# EEZ_DIB_MIO168_r1B2.net
KiCad netlist of a schematic drawn in EAGLE
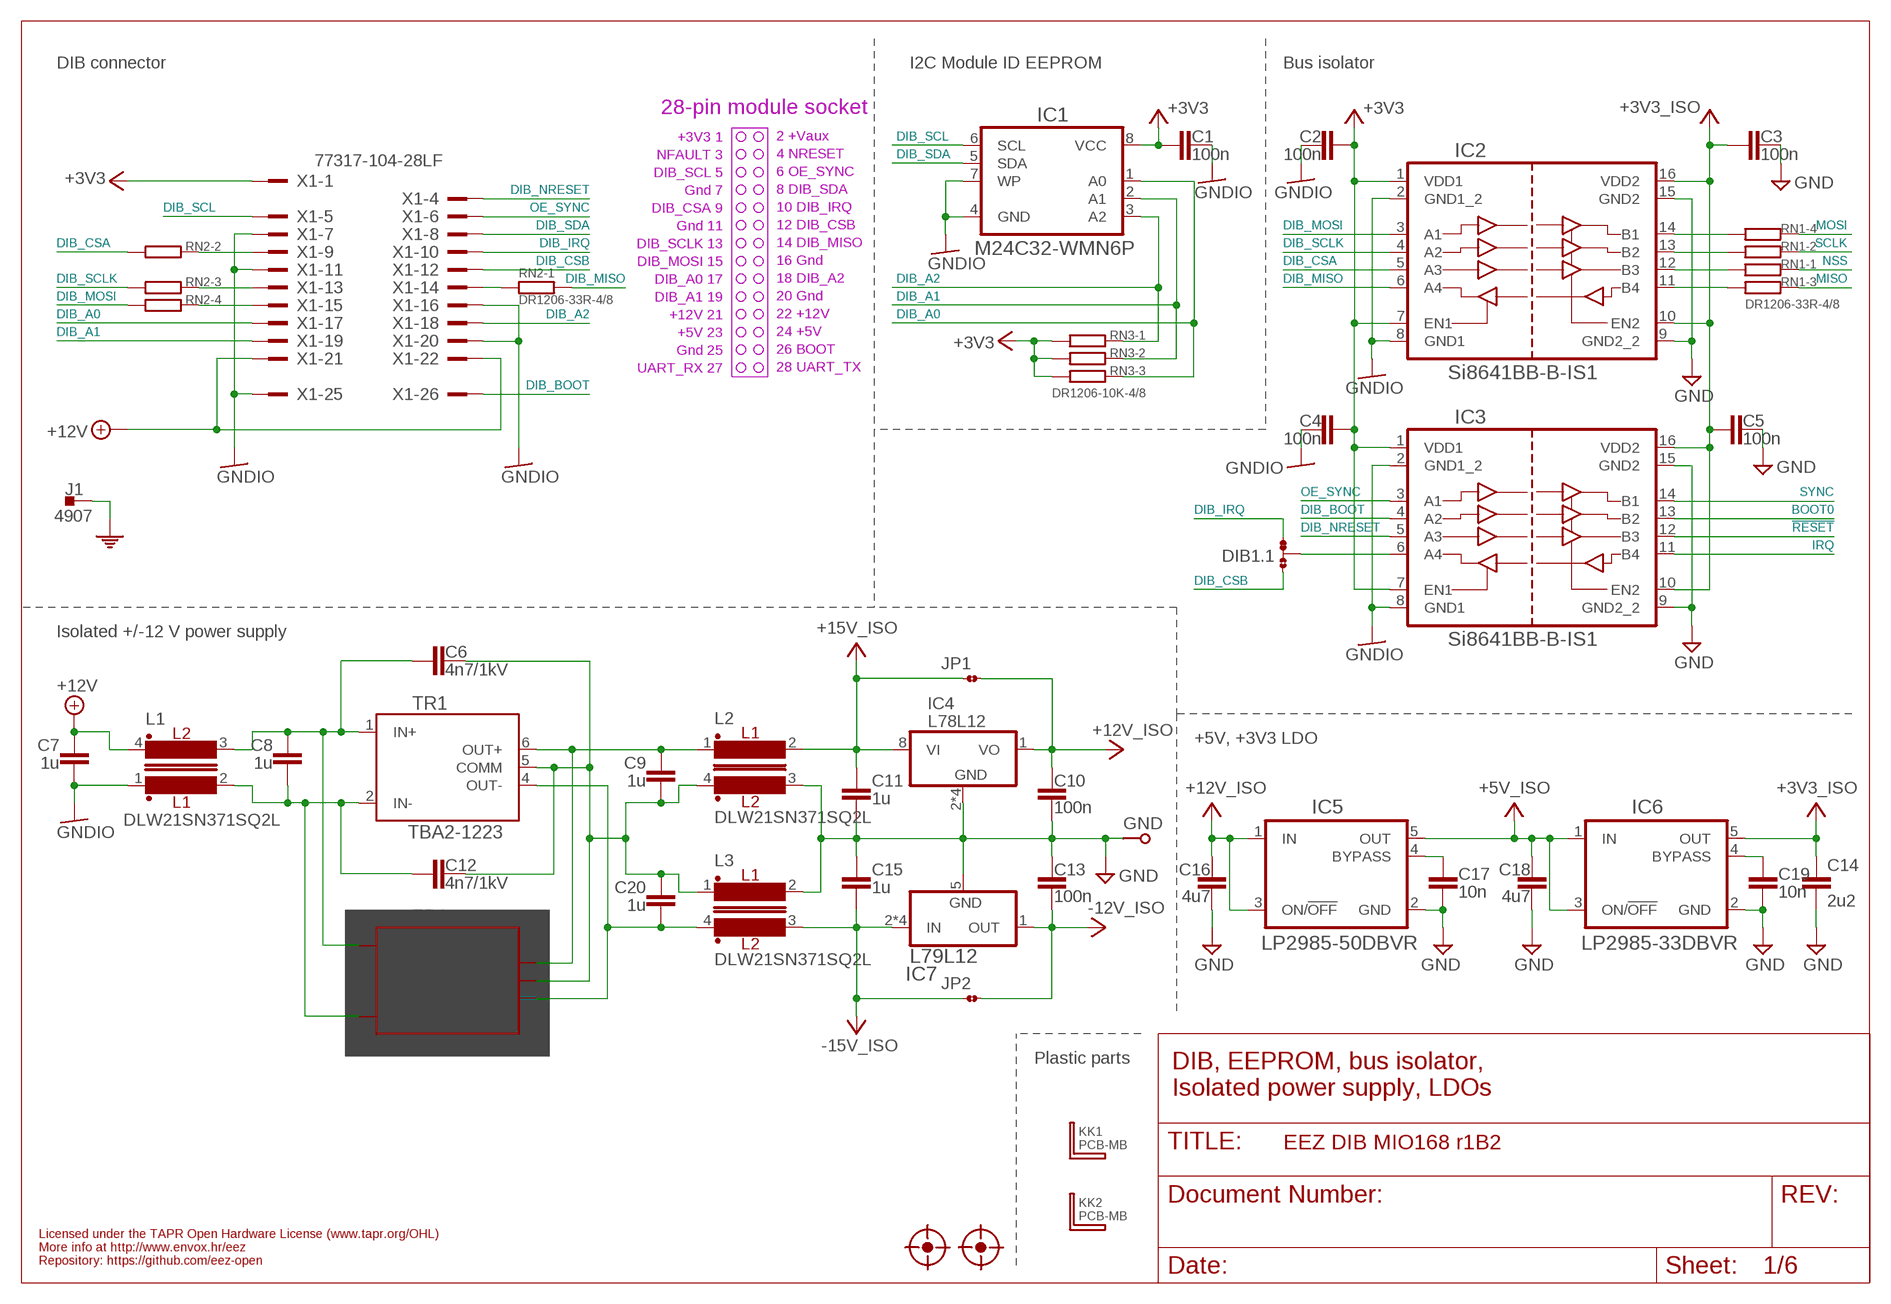
[diagram p0: schematic, sheet 1]
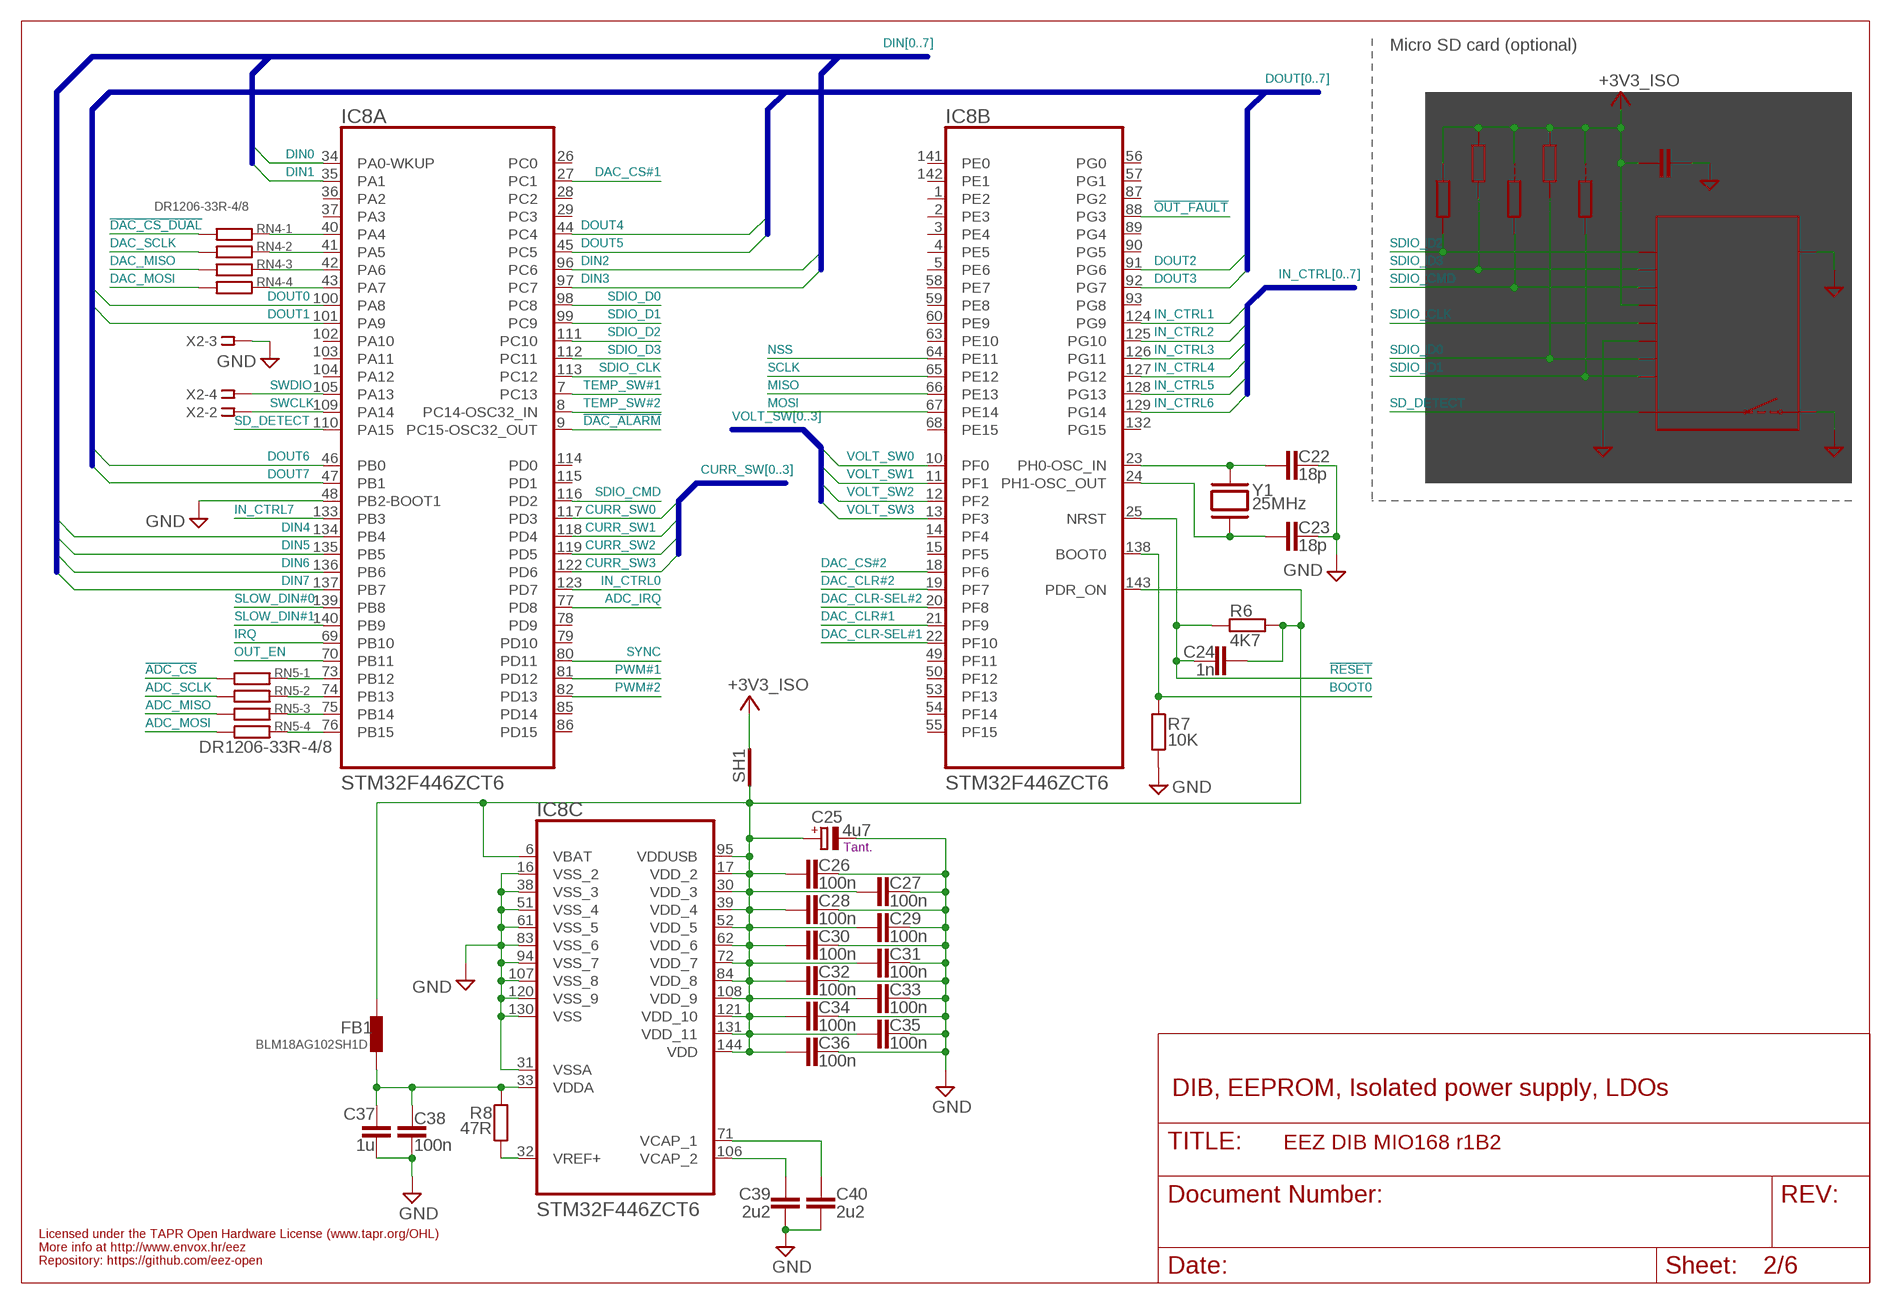
[diagram p1: schematic, sheet 2]
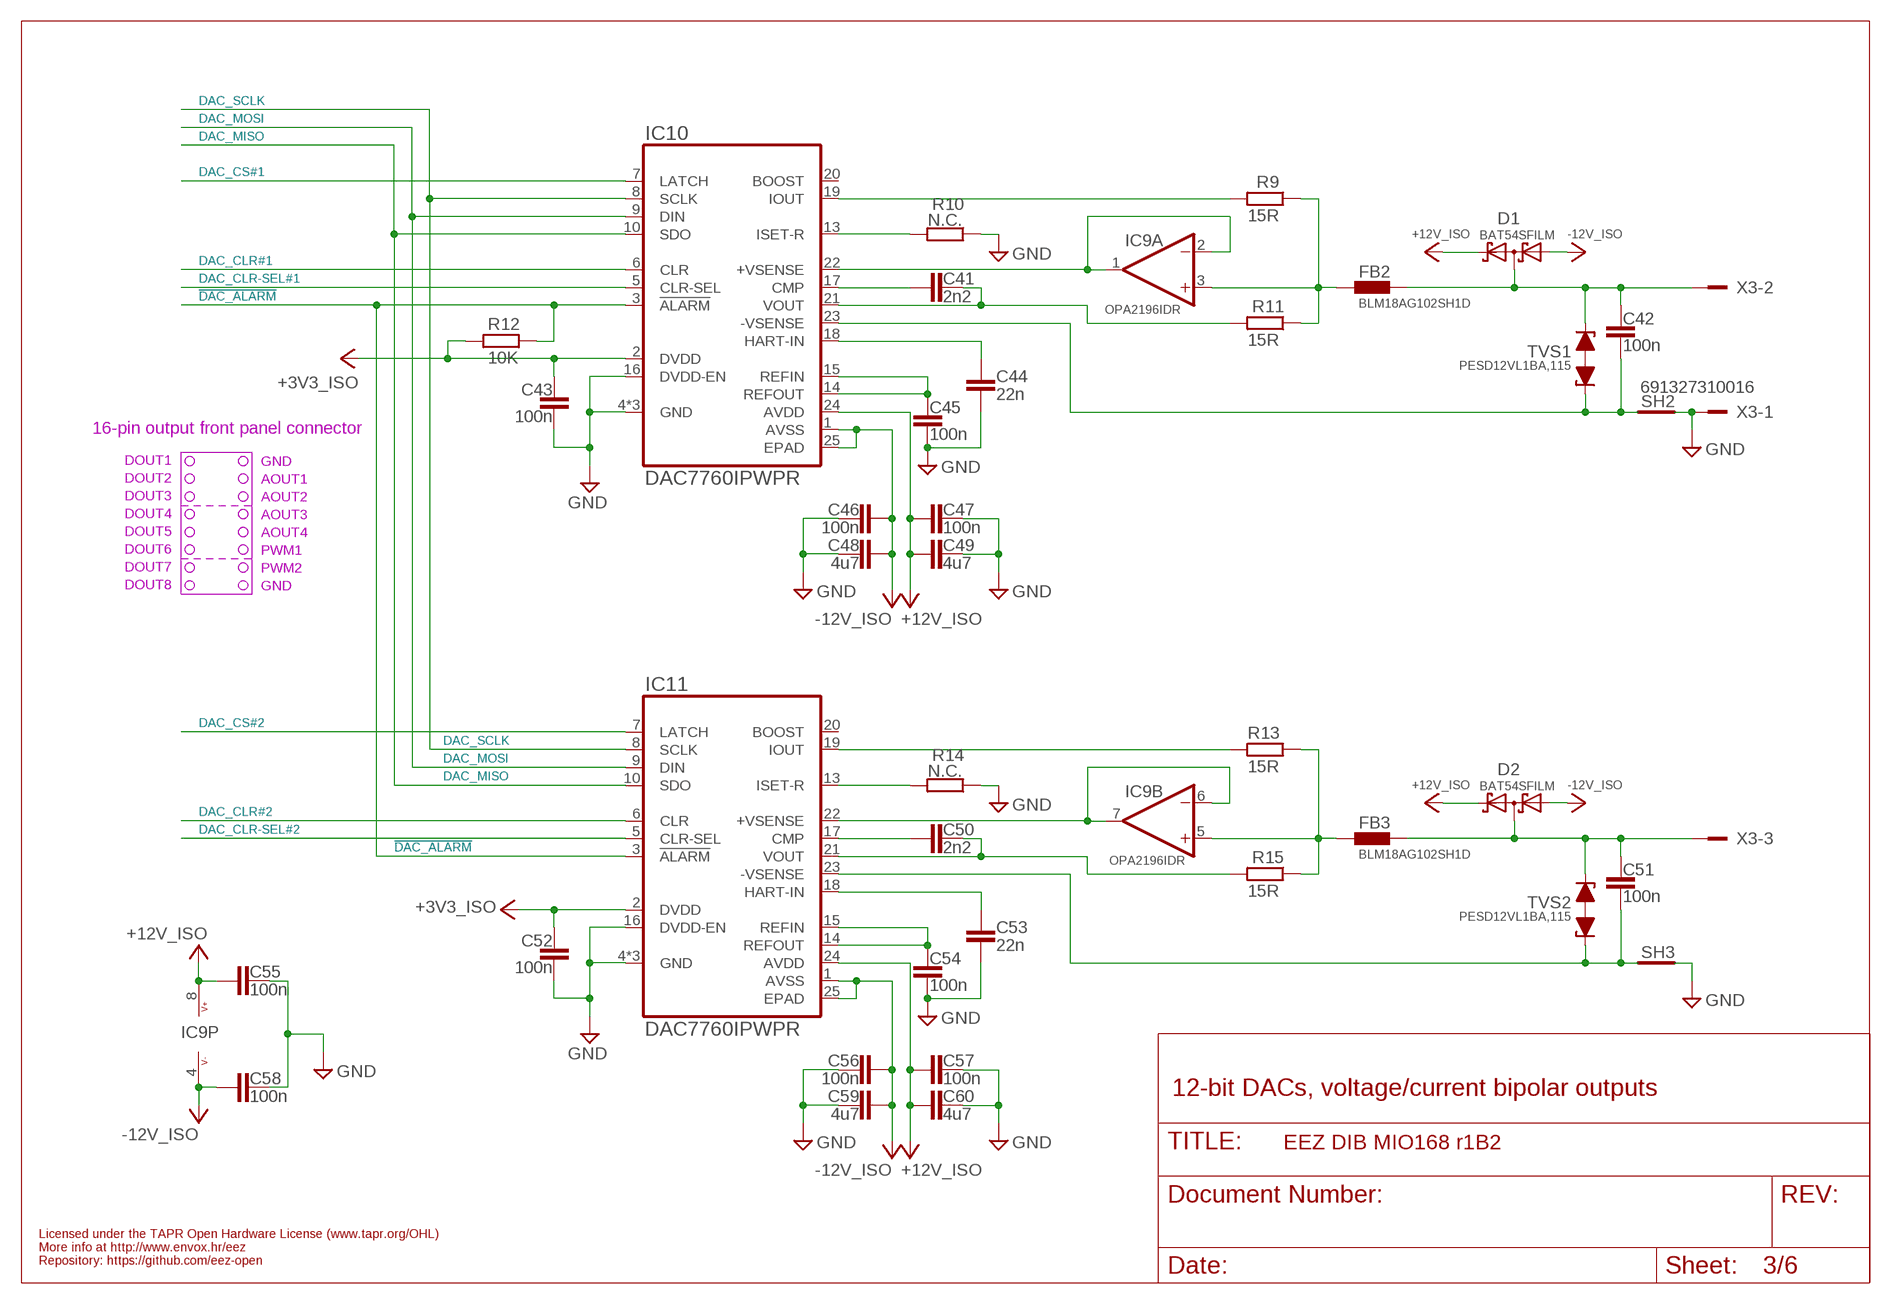
[diagram p2: schematic, sheet 3]
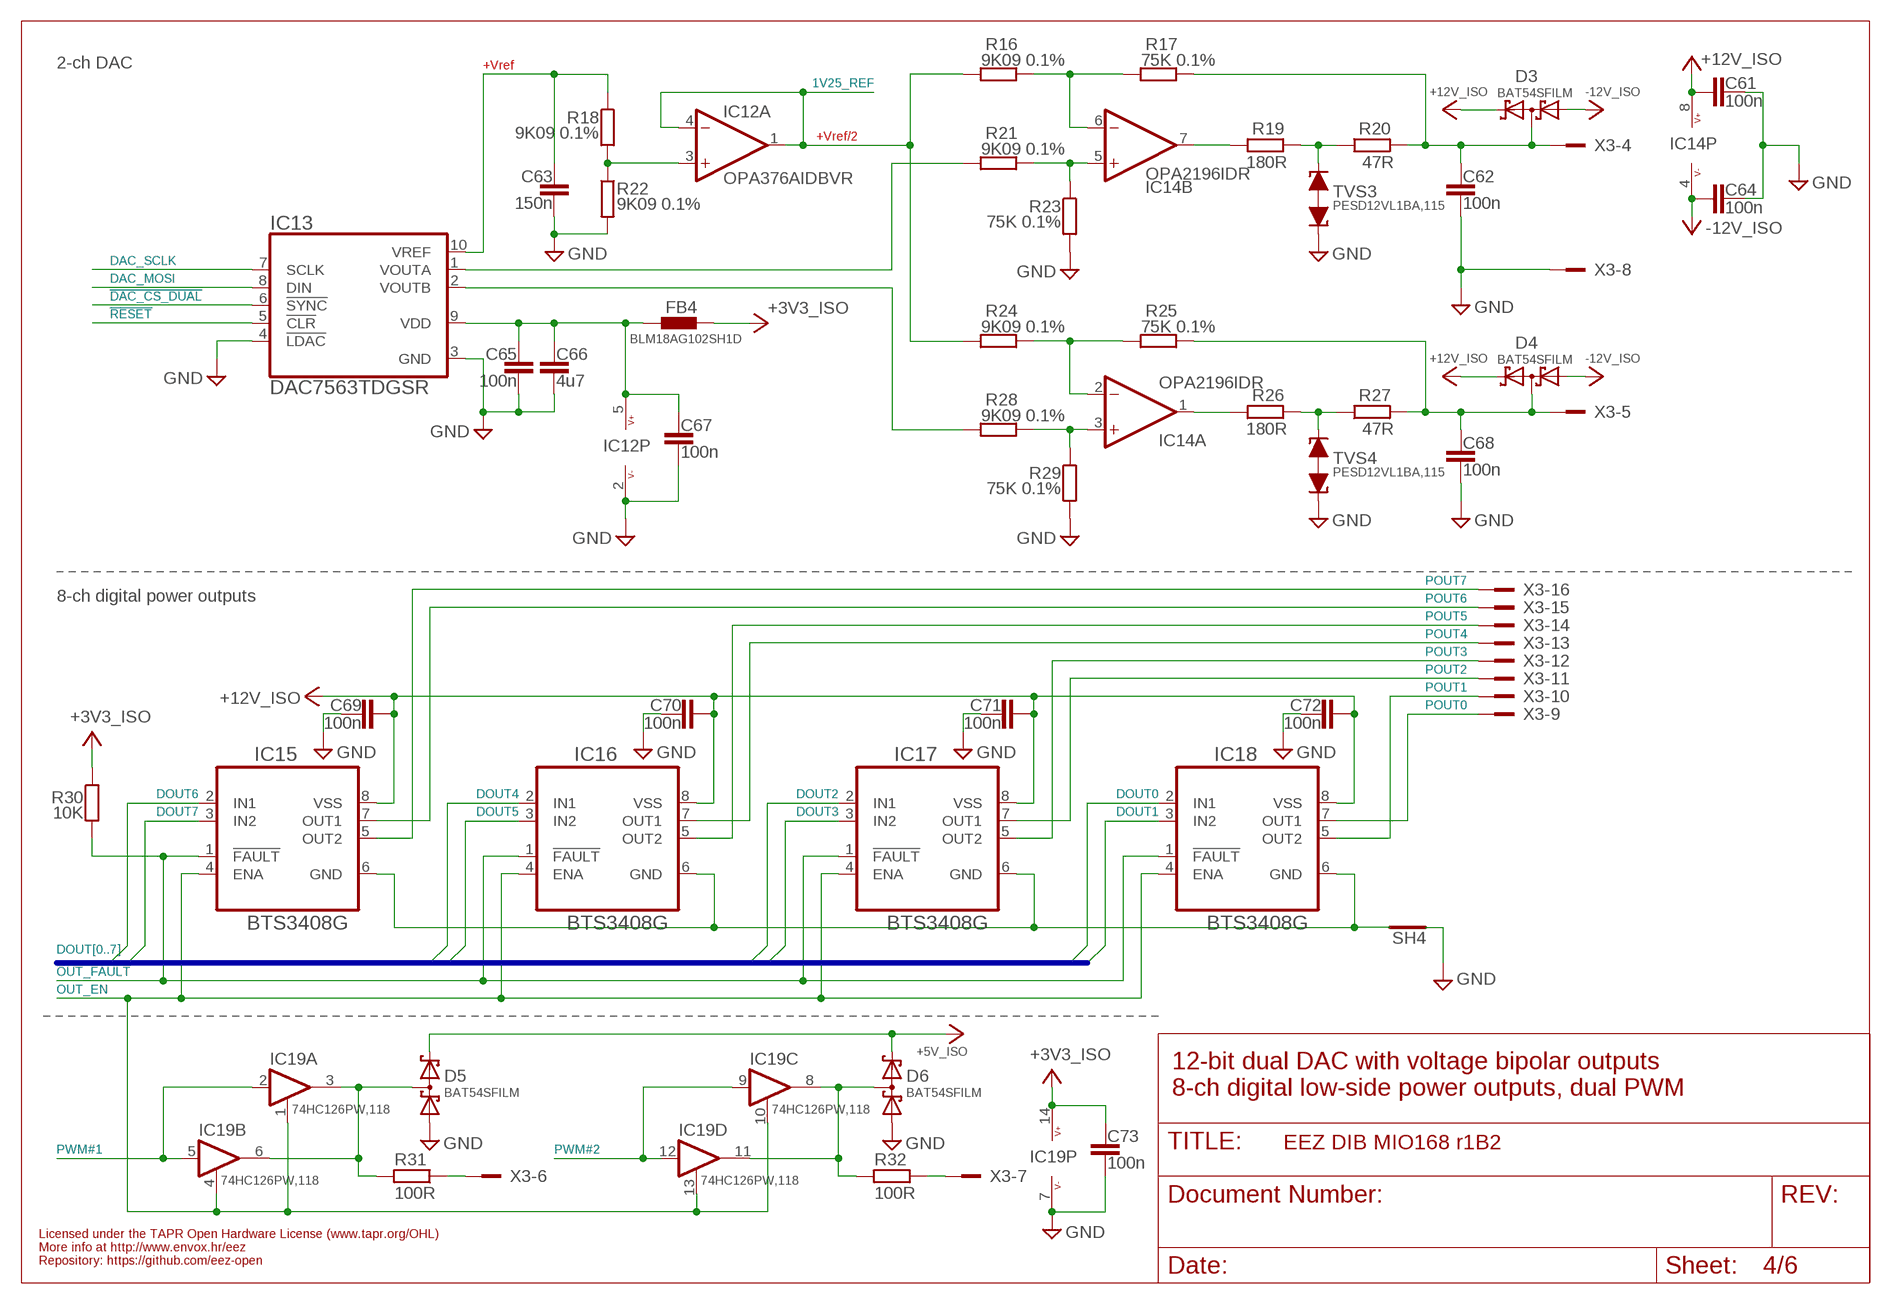
[diagram p3: schematic, sheet 4]
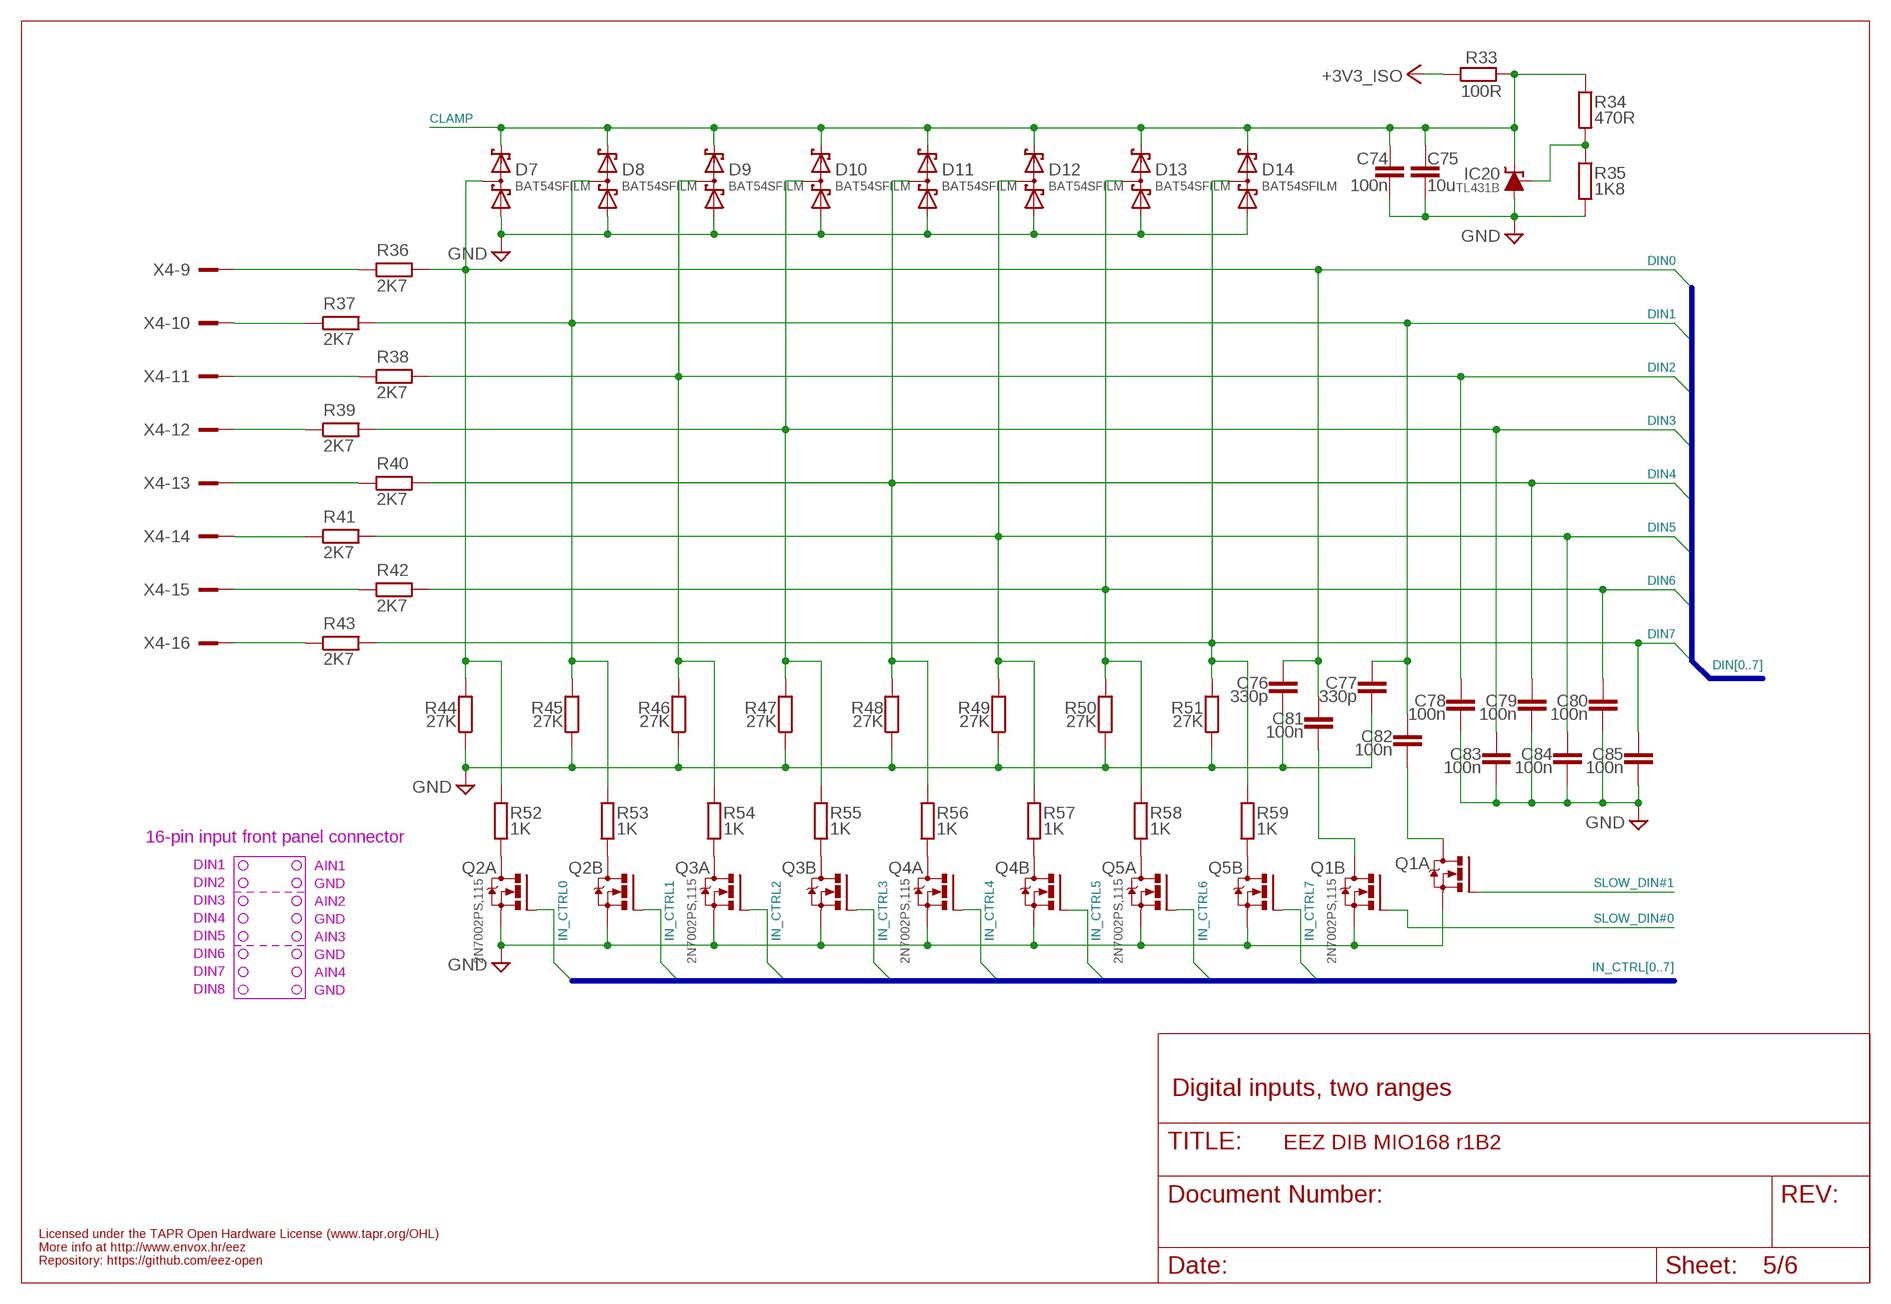
[diagram p4: schematic, sheet 5]
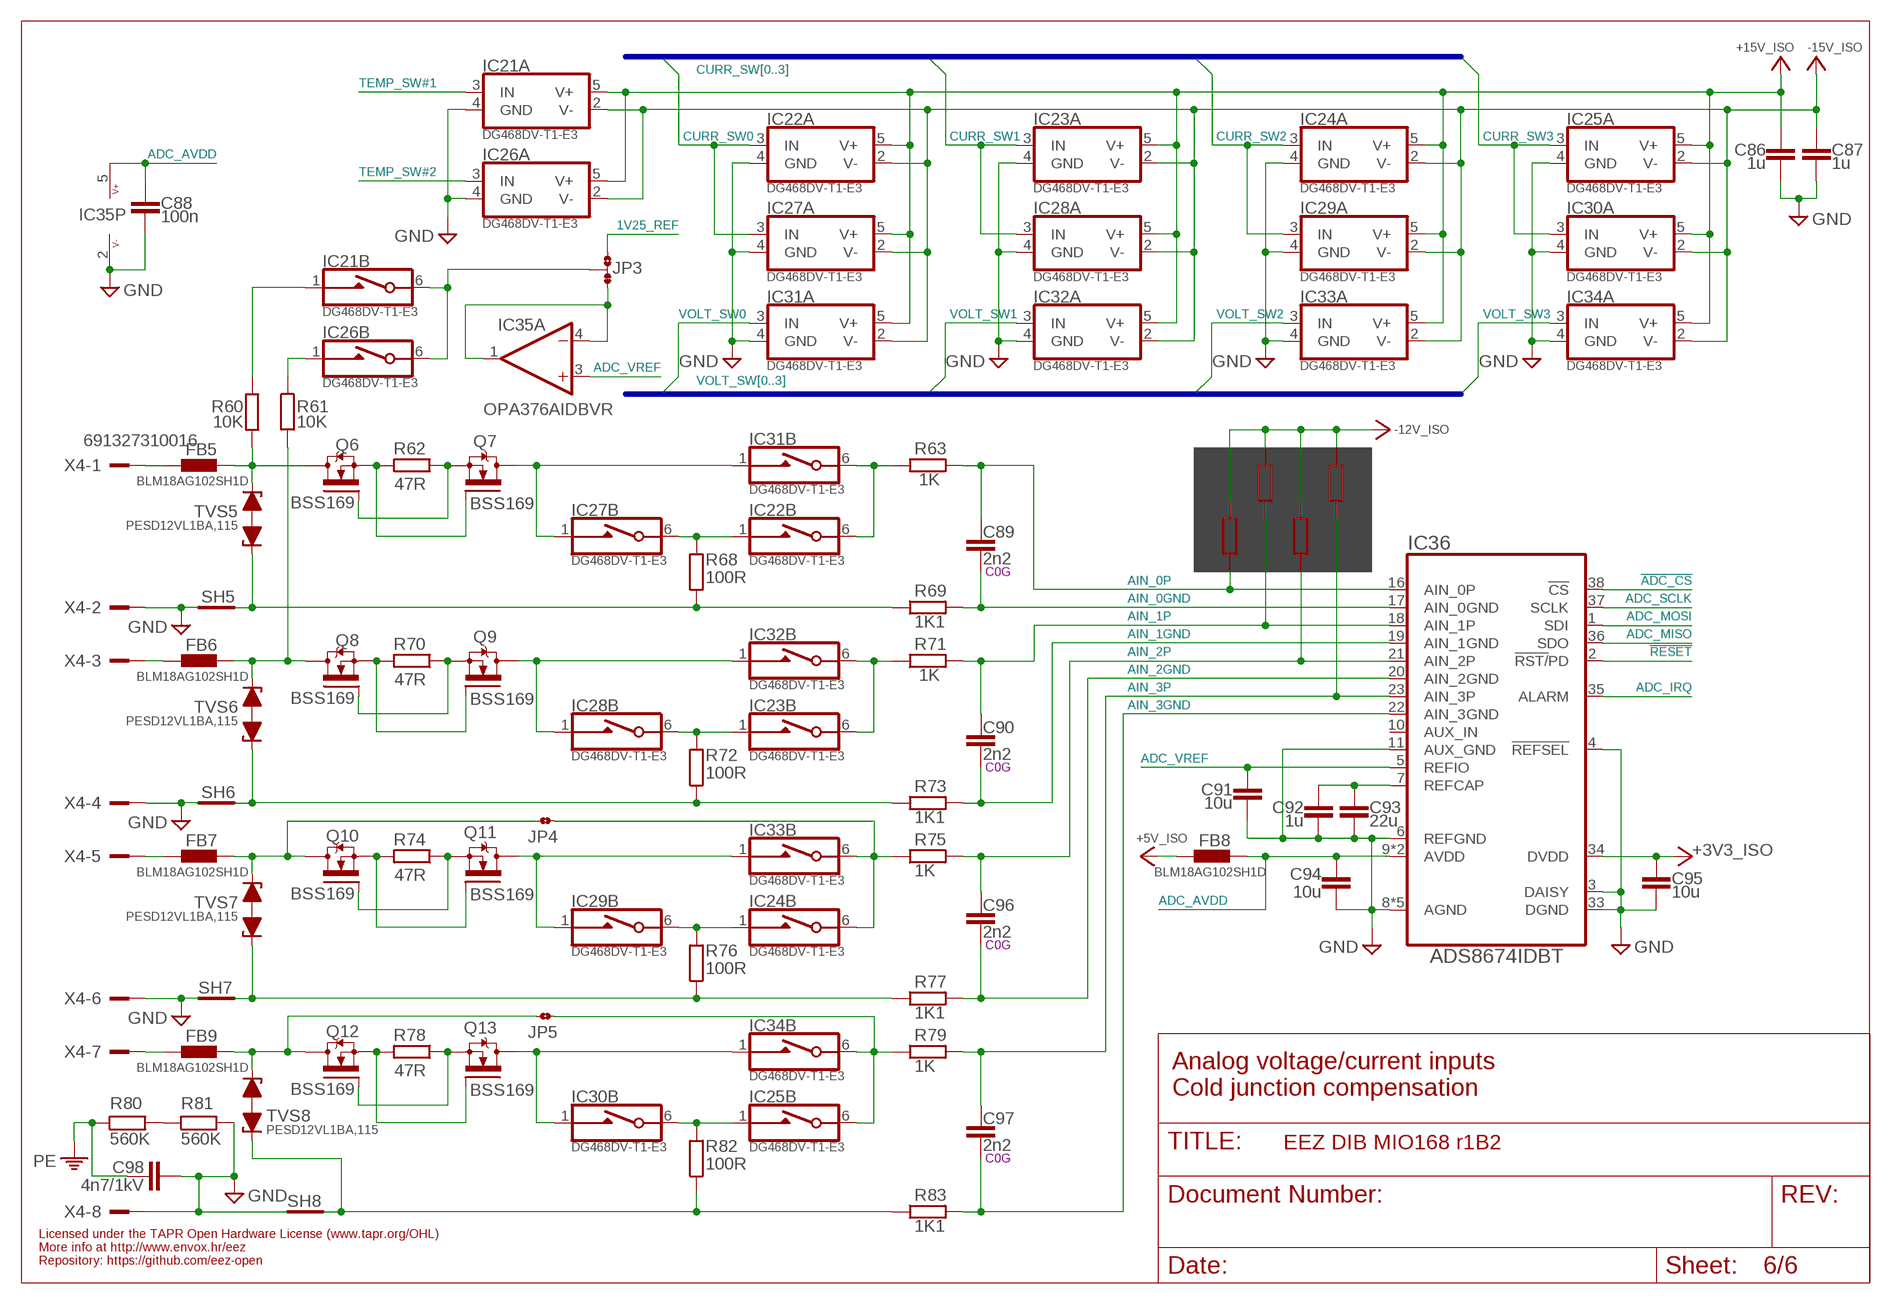
[diagram p5: schematic, sheet 6]

(export (version "E")
  (design (tool "Eeschema 10.0.6"))
  (components
    (comp (ref "C86")
      (value "1u")
      (footprint "eagle-import:C0805")
      (libsource (lib "eagle-import") (part "C-EUC0805"))
    )
    (comp (ref "C87")
      (value "1u")
      (footprint "eagle-import:C0805")
      (libsource (lib "eagle-import") (part "C-EUC0805"))
    )
    (comp (ref "C88")
      (value "100n")
      (footprint "eagle-import:C0603")
      (libsource (lib "eagle-import") (part "C-EUC0603"))
    )
    (comp (ref "C89")
      (value "2n2")
      (footprint "eagle-import:C0805")
      (libsource (lib "eagle-import") (part "C-EUC0805"))
    )
    (comp (ref "C90")
      (value "2n2")
      (footprint "eagle-import:C0805")
      (libsource (lib "eagle-import") (part "C-EUC0805"))
    )
    (comp (ref "C91")
      (value "10u")
      (footprint "eagle-import:C1206")
      (libsource (lib "eagle-import") (part "C-EUC1206"))
    )
    (comp (ref "C92")
      (value "1u")
      (footprint "eagle-import:C0805")
      (libsource (lib "eagle-import") (part "C-EUC0805"))
    )
    (comp (ref "C93")
      (value "22u")
      (footprint "eagle-import:C1206")
      (libsource (lib "eagle-import") (part "C-EUC1206"))
    )
    (comp (ref "C94")
      (value "10u")
      (footprint "eagle-import:C1206")
      (libsource (lib "eagle-import") (part "C-EUC1206"))
    )
    (comp (ref "C95")
      (value "10u")
      (footprint "eagle-import:C1206")
      (libsource (lib "eagle-import") (part "C-EUC1206"))
    )
    (comp (ref "C96")
      (value "2n2")
      (footprint "eagle-import:C0805")
      (libsource (lib "eagle-import") (part "C-EUC0805"))
    )
    (comp (ref "C97")
      (value "2n2")
      (footprint "eagle-import:C0805")
      (libsource (lib "eagle-import") (part "C-EUC0805"))
    )
    (comp (ref "C98")
      (value "4n7/1kV")
      (footprint "eagle-import:C1812")
      (libsource (lib "eagle-import") (part "C-EUC1812"))
    )
    (comp (ref "FB5")
      (value "BLM18AG102SH1D")
      (footprint "eagle-import:BEAD0603")
      (libsource (lib "eagle-import") (part "FERRITE_BEAD0603"))
    )
    (comp (ref "FB6")
      (value "BLM18AG102SH1D")
      (footprint "eagle-import:BEAD0603")
      (libsource (lib "eagle-import") (part "FERRITE_BEAD0603"))
    )
    (comp (ref "FB7")
      (value "BLM18AG102SH1D")
      (footprint "eagle-import:BEAD0603")
      (libsource (lib "eagle-import") (part "FERRITE_BEAD0603"))
    )
    (comp (ref "FB8")
      (value "BLM18AG102SH1D")
      (footprint "eagle-import:BEAD0603")
      (libsource (lib "eagle-import") (part "FERRITE_BEAD0603"))
    )
    (comp (ref "FB9")
      (value "BLM18AG102SH1D")
      (footprint "eagle-import:BEAD0603")
      (libsource (lib "eagle-import") (part "FERRITE_BEAD0603"))
    )
    (comp (ref "IC21")
      (value "DG468DV-T1-E3")
      (footprint "eagle-import:DG6_TSOP6")
      (libsource (lib "eagle-import") (part "DG468DV-T1-E3"))
    )
    (comp (ref "IC22")
      (value "DG468DV-T1-E3")
      (footprint "eagle-import:DG6_TSOP6")
      (libsource (lib "eagle-import") (part "DG468DV-T1-E3"))
    )
    (comp (ref "IC23")
      (value "DG468DV-T1-E3")
      (footprint "eagle-import:DG6_TSOP6")
      (libsource (lib "eagle-import") (part "DG468DV-T1-E3"))
    )
    (comp (ref "IC24")
      (value "DG468DV-T1-E3")
      (footprint "eagle-import:DG6_TSOP6")
      (libsource (lib "eagle-import") (part "DG468DV-T1-E3"))
    )
    (comp (ref "IC25")
      (value "DG468DV-T1-E3")
      (footprint "eagle-import:DG6_TSOP6")
      (libsource (lib "eagle-import") (part "DG468DV-T1-E3"))
    )
    (comp (ref "IC26")
      (value "DG468DV-T1-E3")
      (footprint "eagle-import:DG6_TSOP6")
      (libsource (lib "eagle-import") (part "DG468DV-T1-E3"))
    )
    (comp (ref "IC27")
      (value "DG468DV-T1-E3")
      (footprint "eagle-import:DG6_TSOP6")
      (libsource (lib "eagle-import") (part "DG468DV-T1-E3"))
    )
    (comp (ref "IC28")
      (value "DG468DV-T1-E3")
      (footprint "eagle-import:DG6_TSOP6")
      (libsource (lib "eagle-import") (part "DG468DV-T1-E3"))
    )
    (comp (ref "IC29")
      (value "DG468DV-T1-E3")
      (footprint "eagle-import:DG6_TSOP6")
      (libsource (lib "eagle-import") (part "DG468DV-T1-E3"))
    )
    (comp (ref "IC30")
      (value "DG468DV-T1-E3")
      (footprint "eagle-import:DG6_TSOP6")
      (libsource (lib "eagle-import") (part "DG468DV-T1-E3"))
    )
    (comp (ref "IC31")
      (value "DG468DV-T1-E3")
      (footprint "eagle-import:DG6_TSOP6")
      (libsource (lib "eagle-import") (part "DG468DV-T1-E3"))
    )
    (comp (ref "IC32")
      (value "DG468DV-T1-E3")
      (footprint "eagle-import:DG6_TSOP6")
      (libsource (lib "eagle-import") (part "DG468DV-T1-E3"))
    )
    (comp (ref "IC33")
      (value "DG468DV-T1-E3")
      (footprint "eagle-import:DG6_TSOP6")
      (libsource (lib "eagle-import") (part "DG468DV-T1-E3"))
    )
    (comp (ref "IC34")
      (value "DG468DV-T1-E3")
      (footprint "eagle-import:DG6_TSOP6")
      (libsource (lib "eagle-import") (part "DG468DV-T1-E3"))
    )
    (comp (ref "IC35")
      (value "OPA376AIDBVR")
      (footprint "eagle-import:DBV5")
      (libsource (lib "eagle-import") (part "OPA376AIDBVR"))
    )
    (comp (ref "IC36")
      (value "ADS8674IDBT")
      (footprint "eagle-import:DBT38")
      (libsource (lib "eagle-import") (part "ADS8674IDBT"))
    )
    (comp (ref "JP3")
      (value "JP3-CUT")
      (footprint "eagle-import:JP3-CUT")
      (libsource (lib "eagle-import") (part "JP3-CUT"))
    )
    (comp (ref "JP4")
      (value "JP2-CUT-0805")
      (footprint "eagle-import:R_0805")
      (libsource (lib "eagle-import") (part "JP2-CUT-0805"))
    )
    (comp (ref "JP5")
      (value "JP2-CUT-0805")
      (footprint "eagle-import:R_0805")
      (libsource (lib "eagle-import") (part "JP2-CUT-0805"))
    )
    (comp (ref "Q6")
      (value "BSS169")
      (footprint "eagle-import:SOT103P240X110-3N")
      (libsource (lib "eagle-import") (part "BSS169"))
    )
    (comp (ref "Q7")
      (value "BSS169")
      (footprint "eagle-import:SOT103P240X110-3N")
      (libsource (lib "eagle-import") (part "BSS169"))
    )
    (comp (ref "Q8")
      (value "BSS169")
      (footprint "eagle-import:SOT103P240X110-3N")
      (libsource (lib "eagle-import") (part "BSS169"))
    )
    (comp (ref "Q9")
      (value "BSS169")
      (footprint "eagle-import:SOT103P240X110-3N")
      (libsource (lib "eagle-import") (part "BSS169"))
    )
    (comp (ref "Q10")
      (value "BSS169")
      (footprint "eagle-import:SOT103P240X110-3N")
      (libsource (lib "eagle-import") (part "BSS169"))
    )
    (comp (ref "Q11")
      (value "BSS169")
      (footprint "eagle-import:SOT103P240X110-3N")
      (libsource (lib "eagle-import") (part "BSS169"))
    )
    (comp (ref "Q12")
      (value "BSS169")
      (footprint "eagle-import:SOT103P240X110-3N")
      (libsource (lib "eagle-import") (part "BSS169"))
    )
    (comp (ref "Q13")
      (value "BSS169")
      (footprint "eagle-import:SOT103P240X110-3N")
      (libsource (lib "eagle-import") (part "BSS169"))
    )
    (comp (ref "R60")
      (value "10K")
      (footprint "eagle-import:R0805")
      (libsource (lib "eagle-import") (part "R-EU_R0805"))
    )
    (comp (ref "R61")
      (value "10K")
      (footprint "eagle-import:R0805")
      (libsource (lib "eagle-import") (part "R-EU_R0805"))
    )
    (comp (ref "R62")
      (value "47R")
      (footprint "eagle-import:R0805")
      (libsource (lib "eagle-import") (part "R-EU_R0805"))
    )
    (comp (ref "R63")
      (value "1K")
      (footprint "eagle-import:R0805")
      (libsource (lib "eagle-import") (part "R-EU_R0805"))
    )
    (comp (ref "R64")
      (value "N.C.")
      (footprint "eagle-import:R0805")
      (libsource (lib "eagle-import") (part "R-EU_R0805"))
    )
    (comp (ref "R65")
      (value "N.C.")
      (footprint "eagle-import:R0805")
      (libsource (lib "eagle-import") (part "R-EU_R0805"))
    )
    (comp (ref "R66")
      (value "N.C.")
      (footprint "eagle-import:R0805")
      (libsource (lib "eagle-import") (part "R-EU_R0805"))
    )
    (comp (ref "R67")
      (value "N.C.")
      (footprint "eagle-import:R0805")
      (libsource (lib "eagle-import") (part "R-EU_R0805"))
    )
    (comp (ref "R68")
      (value "100R")
      (footprint "eagle-import:R0805")
      (libsource (lib "eagle-import") (part "R-EU_R0805"))
    )
    (comp (ref "R69")
      (value "1K1")
      (footprint "eagle-import:R0805")
      (libsource (lib "eagle-import") (part "R-EU_R0805"))
    )
    (comp (ref "R70")
      (value "47R")
      (footprint "eagle-import:R0805")
      (libsource (lib "eagle-import") (part "R-EU_R0805"))
    )
    (comp (ref "R71")
      (value "1K")
      (footprint "eagle-import:R0805")
      (libsource (lib "eagle-import") (part "R-EU_R0805"))
    )
    (comp (ref "R72")
      (value "100R")
      (footprint "eagle-import:R0805")
      (libsource (lib "eagle-import") (part "R-EU_R0805"))
    )
    (comp (ref "R73")
      (value "1K1")
      (footprint "eagle-import:R0805")
      (libsource (lib "eagle-import") (part "R-EU_R0805"))
    )
    (comp (ref "R74")
      (value "47R")
      (footprint "eagle-import:R0805")
      (libsource (lib "eagle-import") (part "R-EU_R0805"))
    )
    (comp (ref "R75")
      (value "1K")
      (footprint "eagle-import:R0805")
      (libsource (lib "eagle-import") (part "R-EU_R0805"))
    )
    (comp (ref "R76")
      (value "100R")
      (footprint "eagle-import:R0805")
      (libsource (lib "eagle-import") (part "R-EU_R0805"))
    )
    (comp (ref "R77")
      (value "1K1")
      (footprint "eagle-import:R0805")
      (libsource (lib "eagle-import") (part "R-EU_R0805"))
    )
    (comp (ref "R78")
      (value "47R")
      (footprint "eagle-import:R0805")
      (libsource (lib "eagle-import") (part "R-EU_R0805"))
    )
    (comp (ref "R79")
      (value "1K")
      (footprint "eagle-import:R0805")
      (libsource (lib "eagle-import") (part "R-EU_R0805"))
    )
    (comp (ref "R80")
      (value "560K")
      (footprint "eagle-import:R1206")
      (libsource (lib "eagle-import") (part "R-EU_R1206"))
    )
    (comp (ref "R81")
      (value "560K")
      (footprint "eagle-import:R1206")
      (libsource (lib "eagle-import") (part "R-EU_R1206"))
    )
    (comp (ref "R82")
      (value "100R")
      (footprint "eagle-import:R0805")
      (libsource (lib "eagle-import") (part "R-EU_R0805"))
    )
    (comp (ref "R83")
      (value "1K1")
      (footprint "eagle-import:R0805")
      (libsource (lib "eagle-import") (part "R-EU_R0805"))
    )
    (comp (ref "SH5")
      (value "SHORTNOHOLE")
      (footprint "eagle-import:SHORT_NOHOLE")
      (libsource (lib "eagle-import") (part "SHORTNOHOLE"))
    )
    (comp (ref "SH6")
      (value "SHORTNOHOLE")
      (footprint "eagle-import:SHORT_NOHOLE")
      (libsource (lib "eagle-import") (part "SHORTNOHOLE"))
    )
    (comp (ref "SH7")
      (value "SHORTNOHOLE")
      (footprint "eagle-import:SHORT_NOHOLE")
      (libsource (lib "eagle-import") (part "SHORTNOHOLE"))
    )
    (comp (ref "SH8")
      (value "SHORTNOHOLE")
      (footprint "eagle-import:SHORT_NOHOLE")
      (libsource (lib "eagle-import") (part "SHORTNOHOLE"))
    )
    (comp (ref "TVS5")
      (value "PESD12VL1BA,115")
      (footprint "eagle-import:SOD323-BIDIR")
      (libsource (lib "eagle-import") (part "PESDXL1BA"))
    )
    (comp (ref "TVS6")
      (value "PESD12VL1BA,115")
      (footprint "eagle-import:SOD323-BIDIR")
      (libsource (lib "eagle-import") (part "PESDXL1BA"))
    )
    (comp (ref "TVS7")
      (value "PESD12VL1BA,115")
      (footprint "eagle-import:SOD323-BIDIR")
      (libsource (lib "eagle-import") (part "PESDXL1BA"))
    )
    (comp (ref "TVS8")
      (value "PESD12VL1BA,115")
      (footprint "eagle-import:SOD323-BIDIR")
      (libsource (lib "eagle-import") (part "PESDXL1BA"))
    )
    (comp (ref "X4")
      (value "691327310016")
      (footprint "eagle-import:691327310016")
      (libsource (lib "eagle-import") (part "691327310016"))
    )
    (comp (ref "C21")
      (value "N.C.")
      (footprint "eagle-import:C0805")
      (libsource (lib "eagle-import") (part "C-EUC0805"))
    )
    (comp (ref "C22")
      (value "18p")
      (footprint "eagle-import:C0603")
      (libsource (lib "eagle-import") (part "C-EUC0603"))
    )
    (comp (ref "C23")
      (value "18p")
      (footprint "eagle-import:C0603")
      (libsource (lib "eagle-import") (part "C-EUC0603"))
    )
    (comp (ref "C24")
      (value "1n")
      (footprint "eagle-import:C0805")
      (libsource (lib "eagle-import") (part "C-EUC0805"))
    )
    (comp (ref "C25")
      (value "4u7")
      (footprint "eagle-import:EC1206")
      (libsource (lib "eagle-import") (part "ECAP1206"))
    )
    (comp (ref "C26")
      (value "100n")
      (footprint "eagle-import:C0603")
      (libsource (lib "eagle-import") (part "C-EUC0603"))
    )
    (comp (ref "C27")
      (value "100n")
      (footprint "eagle-import:C0603")
      (libsource (lib "eagle-import") (part "C-EUC0603"))
    )
    (comp (ref "C28")
      (value "100n")
      (footprint "eagle-import:C0603")
      (libsource (lib "eagle-import") (part "C-EUC0603"))
    )
    (comp (ref "C29")
      (value "100n")
      (footprint "eagle-import:C0603")
      (libsource (lib "eagle-import") (part "C-EUC0603"))
    )
    (comp (ref "C30")
      (value "100n")
      (footprint "eagle-import:C0603")
      (libsource (lib "eagle-import") (part "C-EUC0603"))
    )
    (comp (ref "C31")
      (value "100n")
      (footprint "eagle-import:C0603")
      (libsource (lib "eagle-import") (part "C-EUC0603"))
    )
    (comp (ref "C32")
      (value "100n")
      (footprint "eagle-import:C0603")
      (libsource (lib "eagle-import") (part "C-EUC0603"))
    )
    (comp (ref "C33")
      (value "100n")
      (footprint "eagle-import:C0603")
      (libsource (lib "eagle-import") (part "C-EUC0603"))
    )
    (comp (ref "C34")
      (value "100n")
      (footprint "eagle-import:C0603")
      (libsource (lib "eagle-import") (part "C-EUC0603"))
    )
    (comp (ref "C35")
      (value "100n")
      (footprint "eagle-import:C0603")
      (libsource (lib "eagle-import") (part "C-EUC0603"))
    )
    (comp (ref "C36")
      (value "100n")
      (footprint "eagle-import:C0603")
      (libsource (lib "eagle-import") (part "C-EUC0603"))
    )
    (comp (ref "C37")
      (value "1u")
      (footprint "eagle-import:C0805")
      (libsource (lib "eagle-import") (part "C-EUC0805"))
    )
    (comp (ref "C38")
      (value "100n")
      (footprint "eagle-import:C0603")
      (libsource (lib "eagle-import") (part "C-EUC0603"))
    )
    (comp (ref "C39")
      (value "2u2")
      (footprint "eagle-import:C0805")
      (libsource (lib "eagle-import") (part "C-EUC0805"))
    )
    (comp (ref "C40")
      (value "2u2")
      (footprint "eagle-import:C0805")
      (libsource (lib "eagle-import") (part "C-EUC0805"))
    )
    (comp (ref "FB1")
      (value "BLM18AG102SH1D")
      (footprint "eagle-import:BEAD0603")
      (libsource (lib "eagle-import") (part "FERRITE_BEAD0603"))
    )
    (comp (ref "IC8")
      (value "STM32F446ZCT6")
      (footprint "eagle-import:LQFP-144")
      (libsource (lib "eagle-import") (part "STM32F446ZCT6"))
    )
    (comp (ref "J2")
      (value "N.C.")
      (footprint "eagle-import:5033981892")
      (libsource (lib "eagle-import") (part "5033981892"))
    )
    (comp (ref "R1")
      (value "N.C.")
      (footprint "eagle-import:R0805")
      (libsource (lib "eagle-import") (part "R-EU_R0805"))
    )
    (comp (ref "R2")
      (value "N.C.")
      (footprint "eagle-import:R0805")
      (libsource (lib "eagle-import") (part "R-EU_R0805"))
    )
    (comp (ref "R3")
      (value "N.C.")
      (footprint "eagle-import:R0805")
      (libsource (lib "eagle-import") (part "R-EU_R0805"))
    )
    (comp (ref "R4")
      (value "N.C.")
      (footprint "eagle-import:R0805")
      (libsource (lib "eagle-import") (part "R-EU_R0805"))
    )
    (comp (ref "R5")
      (value "N.C.")
      (footprint "eagle-import:R0805")
      (libsource (lib "eagle-import") (part "R-EU_R0805"))
    )
    (comp (ref "R6")
      (value "4K7")
      (footprint "eagle-import:R0805")
      (libsource (lib "eagle-import") (part "R-EU_R0805"))
    )
    (comp (ref "R7")
      (value "10K")
      (footprint "eagle-import:R0805")
      (libsource (lib "eagle-import") (part "R-EU_R0805"))
    )
    (comp (ref "R8")
      (value "47R")
      (footprint "eagle-import:R0805")
      (libsource (lib "eagle-import") (part "R-EU_R0805"))
    )
    (comp (ref "RN4")
      (value "DR1206-33R-4/8")
      (footprint "eagle-import:CAY16")
      (libsource (lib "eagle-import") (part "R_ARRAY4"))
    )
    (comp (ref "RN5")
      (value "DR1206-33R-4/8")
      (footprint "eagle-import:CAY16")
      (libsource (lib "eagle-import") (part "R_ARRAY4"))
    )
    (comp (ref "SH1")
      (value "SHORTNOHOLE")
      (footprint "eagle-import:SHORT_NOHOLE")
      (libsource (lib "eagle-import") (part "SHORTNOHOLE"))
    )
    (comp (ref "X2")
      (value "SSW-106-02-S-S")
      (footprint "eagle-import:SSW-106-02-S-S")
      (libsource (lib "eagle-import") (part "SSW-106-02-S-S"))
    )
    (comp (ref "Y1")
      (value "25MHz")
      (footprint "eagle-import:HC-49_4H")
      (libsource (lib "eagle-import") (part "XTALSMD"))
    )
    (comp (ref "C1")
      (value "100n")
      (footprint "eagle-import:C0603")
      (libsource (lib "eagle-import") (part "C-EUC0603"))
    )
    (comp (ref "C2")
      (value "100n")
      (footprint "eagle-import:C0603")
      (libsource (lib "eagle-import") (part "C-EUC0603"))
    )
    (comp (ref "C3")
      (value "100n")
      (footprint "eagle-import:C0603")
      (libsource (lib "eagle-import") (part "C-EUC0603"))
    )
    (comp (ref "C4")
      (value "100n")
      (footprint "eagle-import:C0603")
      (libsource (lib "eagle-import") (part "C-EUC0603"))
    )
    (comp (ref "C5")
      (value "100n")
      (footprint "eagle-import:C0603")
      (libsource (lib "eagle-import") (part "C-EUC0603"))
    )
    (comp (ref "C6")
      (value "4n7/1kV")
      (footprint "eagle-import:C1812")
      (libsource (lib "eagle-import") (part "C-EUC1812"))
    )
    (comp (ref "C7")
      (value "1u")
      (footprint "eagle-import:C0805")
      (libsource (lib "eagle-import") (part "C-EUC0805"))
    )
    (comp (ref "C8")
      (value "1u")
      (footprint "eagle-import:C0805")
      (libsource (lib "eagle-import") (part "C-EUC0805"))
    )
    (comp (ref "C9")
      (value "1u")
      (footprint "eagle-import:C0805")
      (libsource (lib "eagle-import") (part "C-EUC0805"))
    )
    (comp (ref "C10")
      (value "100n")
      (footprint "eagle-import:C0603")
      (libsource (lib "eagle-import") (part "C-EUC0603"))
    )
    (comp (ref "C11")
      (value "1u")
      (footprint "eagle-import:C0805")
      (libsource (lib "eagle-import") (part "C-EUC0805"))
    )
    (comp (ref "C12")
      (value "4n7/1kV")
      (footprint "eagle-import:C1812")
      (libsource (lib "eagle-import") (part "C-EUC1812"))
    )
    (comp (ref "C13")
      (value "100n")
      (footprint "eagle-import:C0603")
      (libsource (lib "eagle-import") (part "C-EUC0603"))
    )
    (comp (ref "C14")
      (value "2u2")
      (footprint "eagle-import:C0805")
      (libsource (lib "eagle-import") (part "C-EUC0805"))
    )
    (comp (ref "C15")
      (value "1u")
      (footprint "eagle-import:C0805")
      (libsource (lib "eagle-import") (part "C-EUC0805"))
    )
    (comp (ref "C16")
      (value "4u7")
      (footprint "eagle-import:C0805")
      (libsource (lib "eagle-import") (part "C-EUC0805"))
    )
    (comp (ref "C17")
      (value "10n")
      (footprint "eagle-import:C0805")
      (libsource (lib "eagle-import") (part "C-EUC0805"))
    )
    (comp (ref "C18")
      (value "4u7")
      (footprint "eagle-import:C0805")
      (libsource (lib "eagle-import") (part "C-EUC0805"))
    )
    (comp (ref "C19")
      (value "10n")
      (footprint "eagle-import:C0805")
      (libsource (lib "eagle-import") (part "C-EUC0805"))
    )
    (comp (ref "C20")
      (value "1u")
      (footprint "eagle-import:C0805")
      (libsource (lib "eagle-import") (part "C-EUC0805"))
    )
    (comp (ref "DIB1.1")
      (value "JP3-CUT-0805-ROTATED")
      (footprint "eagle-import:JP3-0805-CUT2")
      (libsource (lib "eagle-import") (part "JP3-CUT-0805-ROTATED"))
    )
    (comp (ref "FM1")
      (value "FIDUCIAL_2")
      (footprint "eagle-import:FIDUCIAL_DUAL")
      (libsource (lib "eagle-import") (part "FIDUCIAL_2"))
    )
    (comp (ref "FM2")
      (value "FIDUCIAL_2")
      (footprint "eagle-import:FIDUCIAL_DUAL")
      (libsource (lib "eagle-import") (part "FIDUCIAL_2"))
    )
    (comp (ref "GND")
      (value "PCB_TEST_TABSHIELD")
      (footprint "eagle-import:PCB_SHIELD_TAB")
      (libsource (lib "eagle-import") (part "PCB_TEST_TABSHIELD"))
    )
    (comp (ref "IC1")
      (value "M24C32-WMN6P")
      (footprint "eagle-import:SOIC127P600X173-8N")
      (libsource (lib "eagle-import") (part "AT24CXXSOIC8"))
    )
    (comp (ref "IC2")
      (value "Si8641BB-B-IS1")
      (footprint "eagle-import:SOIC-16")
      (libsource (lib "eagle-import") (part "SI8641NSOIC-16"))
    )
    (comp (ref "IC3")
      (value "Si8641BB-B-IS1")
      (footprint "eagle-import:SOIC-16")
      (libsource (lib "eagle-import") (part "SI8641NSOIC-16"))
    )
    (comp (ref "IC4")
      (value "L78L12")
      (footprint "eagle-import:SOIC127P600X173-8N")
      (libsource (lib "eagle-import") (part "MC78LXXSOIC8"))
    )
    (comp (ref "IC5")
      (value "LP2985-50DBVR")
      (footprint "eagle-import:SOT95P270X145-5N")
      (libsource (lib "eagle-import") (part "LP2985"))
    )
    (comp (ref "IC6")
      (value "LP2985-33DBVR")
      (footprint "eagle-import:SOT95P270X145-5N")
      (libsource (lib "eagle-import") (part "LP2985"))
    )
    (comp (ref "IC7")
      (value "L79L12")
      (footprint "eagle-import:SOIC127P600X173-8N")
      (libsource (lib "eagle-import") (part "MC79LXXSOIC"))
    )
    (comp (ref "J1")
      (value "4907")
      (footprint "eagle-import:PCB_TAB-4907")
      (libsource (lib "eagle-import") (part "PCB_TAB-4907"))
    )
    (comp (ref "JP1")
      (value "JP2-CUT-0805")
      (footprint "eagle-import:R_0805")
      (libsource (lib "eagle-import") (part "JP2-CUT-0805"))
    )
    (comp (ref "JP2")
      (value "JP2-CUT-0805")
      (footprint "eagle-import:R_0805")
      (libsource (lib "eagle-import") (part "JP2-CUT-0805"))
    )
    (comp (ref "KK1")
      (value "PCB-MB")
      (footprint "eagle-import:PCB-MB")
      (libsource (lib "eagle-import") (part "PCB-MB"))
    )
    (comp (ref "KK2")
      (value "PCB-MB")
      (footprint "eagle-import:PCB-MB")
      (libsource (lib "eagle-import") (part "PCB-MB"))
    )
    (comp (ref "L1")
      (value "DLW21SN371SQ2L")
      (footprint "eagle-import:MURATA_DLW21S")
      (libsource (lib "eagle-import") (part "DLW21S"))
    )
    (comp (ref "L2")
      (value "DLW21SN371SQ2L")
      (footprint "eagle-import:MURATA_DLW21S")
      (libsource (lib "eagle-import") (part "DLW21S"))
    )
    (comp (ref "L3")
      (value "DLW21SN371SQ2L")
      (footprint "eagle-import:MURATA_DLW21S")
      (libsource (lib "eagle-import") (part "DLW21S"))
    )
    (comp (ref "RN1")
      (value "DR1206-33R-4/8")
      (footprint "eagle-import:CAY16")
      (libsource (lib "eagle-import") (part "R_ARRAY4"))
    )
    (comp (ref "RN2")
      (value "DR1206-33R-4/8")
      (footprint "eagle-import:CAY16")
      (libsource (lib "eagle-import") (part "R_ARRAY4"))
    )
    (comp (ref "RN3")
      (value "DR1206-10K-4/8")
      (footprint "eagle-import:CAY16")
      (libsource (lib "eagle-import") (part "R_ARRAY4"))
    )
    (comp (ref "TR1")
      (value "TBA2-1223")
      (footprint "eagle-import:TBA2")
      (libsource (lib "eagle-import") (part "TBA-DUAL-2W"))
    )
    (comp (ref "TR2")
      (value "MDD02M-15")
      (footprint "eagle-import:MDD02")
      (libsource (lib "eagle-import") (part "MDD02"))
    )
    (comp (ref "X1")
      (value "77317-104-28LF")
      (footprint "eagle-import:77317-104-28LF")
      (libsource (lib "eagle-import") (part "77317-104-28LF"))
    )
    (comp (ref "C74")
      (value "100n")
      (footprint "eagle-import:C0603")
      (libsource (lib "eagle-import") (part "C-EUC0603"))
    )
    (comp (ref "C75")
      (value "10u")
      (footprint "eagle-import:C1206")
      (libsource (lib "eagle-import") (part "C-EUC1206"))
    )
    (comp (ref "C76")
      (value "330p")
      (footprint "eagle-import:C0805")
      (libsource (lib "eagle-import") (part "C-EUC0805"))
    )
    (comp (ref "C77")
      (value "330p")
      (footprint "eagle-import:C0805")
      (libsource (lib "eagle-import") (part "C-EUC0805"))
    )
    (comp (ref "C78")
      (value "100n")
      (footprint "eagle-import:C0603")
      (libsource (lib "eagle-import") (part "C-EUC0603"))
    )
    (comp (ref "C79")
      (value "100n")
      (footprint "eagle-import:C0603")
      (libsource (lib "eagle-import") (part "C-EUC0603"))
    )
    (comp (ref "C80")
      (value "100n")
      (footprint "eagle-import:C0603")
      (libsource (lib "eagle-import") (part "C-EUC0603"))
    )
    (comp (ref "C81")
      (value "100n")
      (footprint "eagle-import:C0603")
      (libsource (lib "eagle-import") (part "C-EUC0603"))
    )
    (comp (ref "C82")
      (value "100n")
      (footprint "eagle-import:C0603")
      (libsource (lib "eagle-import") (part "C-EUC0603"))
    )
    (comp (ref "C83")
      (value "100n")
      (footprint "eagle-import:C0603")
      (libsource (lib "eagle-import") (part "C-EUC0603"))
    )
    (comp (ref "C84")
      (value "100n")
      (footprint "eagle-import:C0603")
      (libsource (lib "eagle-import") (part "C-EUC0603"))
    )
    (comp (ref "C85")
      (value "100n")
      (footprint "eagle-import:C0603")
      (libsource (lib "eagle-import") (part "C-EUC0603"))
    )
    (comp (ref "D7")
      (value "BAT54SFILM")
      (footprint "eagle-import:SOT23")
      (libsource (lib "eagle-import") (part "BAT54S"))
    )
    (comp (ref "D8")
      (value "BAT54SFILM")
      (footprint "eagle-import:SOT23")
      (libsource (lib "eagle-import") (part "BAT54S"))
    )
    (comp (ref "D9")
      (value "BAT54SFILM")
      (footprint "eagle-import:SOT23")
      (libsource (lib "eagle-import") (part "BAT54S"))
    )
    (comp (ref "D10")
      (value "BAT54SFILM")
      (footprint "eagle-import:SOT23")
      (libsource (lib "eagle-import") (part "BAT54S"))
    )
    (comp (ref "D11")
      (value "BAT54SFILM")
      (footprint "eagle-import:SOT23")
      (libsource (lib "eagle-import") (part "BAT54S"))
    )
    (comp (ref "D12")
      (value "BAT54SFILM")
      (footprint "eagle-import:SOT23")
      (libsource (lib "eagle-import") (part "BAT54S"))
    )
    (comp (ref "D13")
      (value "BAT54SFILM")
      (footprint "eagle-import:SOT23")
      (libsource (lib "eagle-import") (part "BAT54S"))
    )
    (comp (ref "D14")
      (value "BAT54SFILM")
      (footprint "eagle-import:SOT23")
      (libsource (lib "eagle-import") (part "BAT54S"))
    )
    (comp (ref "IC20")
      (value "TL431B")
      (footprint "eagle-import:SOT103P240X110-3N")
      (libsource (lib "eagle-import") (part "TL431"))
    )
    (comp (ref "Q1")
      (value "2N7002PS,115")
      (footprint "eagle-import:SC88")
      (libsource (lib "eagle-import") (part "2N7002PS,115"))
    )
    (comp (ref "Q2")
      (value "2N7002PS,115")
      (footprint "eagle-import:SC88")
      (libsource (lib "eagle-import") (part "2N7002PS,115"))
    )
    (comp (ref "Q3")
      (value "2N7002PS,115")
      (footprint "eagle-import:SC88")
      (libsource (lib "eagle-import") (part "2N7002PS,115"))
    )
    (comp (ref "Q4")
      (value "2N7002PS,115")
      (footprint "eagle-import:SC88")
      (libsource (lib "eagle-import") (part "2N7002PS,115"))
    )
    (comp (ref "Q5")
      (value "2N7002PS,115")
      (footprint "eagle-import:SC88")
      (libsource (lib "eagle-import") (part "2N7002PS,115"))
    )
    (comp (ref "R33")
      (value "100R")
      (footprint "eagle-import:R0805")
      (libsource (lib "eagle-import") (part "R-EU_R0805"))
    )
    (comp (ref "R34")
      (value "470R")
      (footprint "eagle-import:R0805")
      (libsource (lib "eagle-import") (part "R-EU_R0805"))
    )
    (comp (ref "R35")
      (value "1K8")
      (footprint "eagle-import:R0805")
      (libsource (lib "eagle-import") (part "R-EU_R0805"))
    )
    (comp (ref "R36")
      (value "2K7")
      (footprint "eagle-import:R1206")
      (libsource (lib "eagle-import") (part "R-EU_R1206"))
    )
    (comp (ref "R37")
      (value "2K7")
      (footprint "eagle-import:R1206")
      (libsource (lib "eagle-import") (part "R-EU_R1206"))
    )
    (comp (ref "R38")
      (value "2K7")
      (footprint "eagle-import:R1206")
      (libsource (lib "eagle-import") (part "R-EU_R1206"))
    )
    (comp (ref "R39")
      (value "2K7")
      (footprint "eagle-import:R1206")
      (libsource (lib "eagle-import") (part "R-EU_R1206"))
    )
    (comp (ref "R40")
      (value "2K7")
      (footprint "eagle-import:R1206")
      (libsource (lib "eagle-import") (part "R-EU_R1206"))
    )
    (comp (ref "R41")
      (value "2K7")
      (footprint "eagle-import:R1206")
      (libsource (lib "eagle-import") (part "R-EU_R1206"))
    )
    (comp (ref "R42")
      (value "2K7")
      (footprint "eagle-import:R1206")
      (libsource (lib "eagle-import") (part "R-EU_R1206"))
    )
    (comp (ref "R43")
      (value "2K7")
      (footprint "eagle-import:R1206")
      (libsource (lib "eagle-import") (part "R-EU_R1206"))
    )
    (comp (ref "R44")
      (value "27K")
      (footprint "eagle-import:R0805")
      (libsource (lib "eagle-import") (part "R-EU_R0805"))
    )
    (comp (ref "R45")
      (value "27K")
      (footprint "eagle-import:R0805")
      (libsource (lib "eagle-import") (part "R-EU_R0805"))
    )
    (comp (ref "R46")
      (value "27K")
      (footprint "eagle-import:R0805")
      (libsource (lib "eagle-import") (part "R-EU_R0805"))
    )
    (comp (ref "R47")
      (value "27K")
      (footprint "eagle-import:R0805")
      (libsource (lib "eagle-import") (part "R-EU_R0805"))
    )
    (comp (ref "R48")
      (value "27K")
      (footprint "eagle-import:R0805")
      (libsource (lib "eagle-import") (part "R-EU_R0805"))
    )
    (comp (ref "R49")
      (value "27K")
      (footprint "eagle-import:R0805")
      (libsource (lib "eagle-import") (part "R-EU_R0805"))
    )
    (comp (ref "R50")
      (value "27K")
      (footprint "eagle-import:R0805")
      (libsource (lib "eagle-import") (part "R-EU_R0805"))
    )
    (comp (ref "R51")
      (value "27K")
      (footprint "eagle-import:R0805")
      (libsource (lib "eagle-import") (part "R-EU_R0805"))
    )
    (comp (ref "R52")
      (value "1K")
      (footprint "eagle-import:R0805")
      (libsource (lib "eagle-import") (part "R-EU_R0805"))
    )
    (comp (ref "R53")
      (value "1K")
      (footprint "eagle-import:R0805")
      (libsource (lib "eagle-import") (part "R-EU_R0805"))
    )
    (comp (ref "R54")
      (value "1K")
      (footprint "eagle-import:R0805")
      (libsource (lib "eagle-import") (part "R-EU_R0805"))
    )
    (comp (ref "R55")
      (value "1K")
      (footprint "eagle-import:R0805")
      (libsource (lib "eagle-import") (part "R-EU_R0805"))
    )
    (comp (ref "R56")
      (value "1K")
      (footprint "eagle-import:R0805")
      (libsource (lib "eagle-import") (part "R-EU_R0805"))
    )
    (comp (ref "R57")
      (value "1K")
      (footprint "eagle-import:R0805")
      (libsource (lib "eagle-import") (part "R-EU_R0805"))
    )
    (comp (ref "R58")
      (value "1K")
      (footprint "eagle-import:R0805")
      (libsource (lib "eagle-import") (part "R-EU_R0805"))
    )
    (comp (ref "R59")
      (value "1K")
      (footprint "eagle-import:R0805")
      (libsource (lib "eagle-import") (part "R-EU_R0805"))
    )
    (comp (ref "C61")
      (value "100n")
      (footprint "eagle-import:C0603")
      (libsource (lib "eagle-import") (part "C-EUC0603"))
    )
    (comp (ref "C62")
      (value "100n")
      (footprint "eagle-import:C0603")
      (libsource (lib "eagle-import") (part "C-EUC0603"))
    )
    (comp (ref "C63")
      (value "150n")
      (footprint "eagle-import:C0805")
      (libsource (lib "eagle-import") (part "C-EUC0805"))
    )
    (comp (ref "C64")
      (value "100n")
      (footprint "eagle-import:C0603")
      (libsource (lib "eagle-import") (part "C-EUC0603"))
    )
    (comp (ref "C65")
      (value "100n")
      (footprint "eagle-import:C0603")
      (libsource (lib "eagle-import") (part "C-EUC0603"))
    )
    (comp (ref "C66")
      (value "4u7")
      (footprint "eagle-import:C0805")
      (libsource (lib "eagle-import") (part "C-EUC0805"))
    )
    (comp (ref "C67")
      (value "100n")
      (footprint "eagle-import:C0603")
      (libsource (lib "eagle-import") (part "C-EUC0603"))
    )
    (comp (ref "C68")
      (value "100n")
      (footprint "eagle-import:C0603")
      (libsource (lib "eagle-import") (part "C-EUC0603"))
    )
    (comp (ref "C69")
      (value "100n")
      (footprint "eagle-import:C0603")
      (libsource (lib "eagle-import") (part "C-EUC0603"))
    )
    (comp (ref "C70")
      (value "100n")
      (footprint "eagle-import:C0603")
      (libsource (lib "eagle-import") (part "C-EUC0603"))
    )
    (comp (ref "C71")
      (value "100n")
      (footprint "eagle-import:C0603")
      (libsource (lib "eagle-import") (part "C-EUC0603"))
    )
    (comp (ref "C72")
      (value "100n")
      (footprint "eagle-import:C0603")
      (libsource (lib "eagle-import") (part "C-EUC0603"))
    )
    (comp (ref "C73")
      (value "100n")
      (footprint "eagle-import:C0603")
      (libsource (lib "eagle-import") (part "C-EUC0603"))
    )
    (comp (ref "D3")
      (value "BAT54SFILM")
      (footprint "eagle-import:SOT23")
      (libsource (lib "eagle-import") (part "BAT54S"))
    )
    (comp (ref "D4")
      (value "BAT54SFILM")
      (footprint "eagle-import:SOT23")
      (libsource (lib "eagle-import") (part "BAT54S"))
    )
    (comp (ref "D5")
      (value "BAT54SFILM")
      (footprint "eagle-import:SOT23")
      (libsource (lib "eagle-import") (part "BAT54S"))
    )
    (comp (ref "D6")
      (value "BAT54SFILM")
      (footprint "eagle-import:SOT23")
      (libsource (lib "eagle-import") (part "BAT54S"))
    )
    (comp (ref "FB4")
      (value "BLM18AG102SH1D")
      (footprint "eagle-import:BEAD0603")
      (libsource (lib "eagle-import") (part "FERRITE_BEAD0603"))
    )
    (comp (ref "IC12")
      (value "OPA376AIDBVR")
      (footprint "eagle-import:DBV5")
      (libsource (lib "eagle-import") (part "OPA376AIDBVR"))
    )
    (comp (ref "IC13")
      (value "DAC7563TDGSR")
      (footprint "eagle-import:DGS10")
      (libsource (lib "eagle-import") (part "DAC7563TDGSR"))
    )
    (comp (ref "IC14")
      (value "OPA2196IDR")
      (footprint "eagle-import:SOIC127P600X173-8N")
      (libsource (lib "eagle-import") (part "TL072SOIC8"))
    )
    (comp (ref "IC15")
      (value "BTS3408G")
      (footprint "eagle-import:SOIC127P600X173-8N")
      (libsource (lib "eagle-import") (part "BTS3408G"))
    )
    (comp (ref "IC16")
      (value "BTS3408G")
      (footprint "eagle-import:SOIC127P600X173-8N")
      (libsource (lib "eagle-import") (part "BTS3408G"))
    )
    (comp (ref "IC17")
      (value "BTS3408G")
      (footprint "eagle-import:SOIC127P600X173-8N")
      (libsource (lib "eagle-import") (part "BTS3408G"))
    )
    (comp (ref "IC18")
      (value "BTS3408G")
      (footprint "eagle-import:SOIC127P600X173-8N")
      (libsource (lib "eagle-import") (part "BTS3408G"))
    )
    (comp (ref "IC19")
      (value "74HC126PW,118")
      (footprint "eagle-import:PW14")
      (libsource (lib "eagle-import") (part "74HC126PW,118"))
    )
    (comp (ref "R16")
      (value "9K09 0.1%")
      (footprint "eagle-import:R0805")
      (libsource (lib "eagle-import") (part "R-EU_R0805"))
    )
    (comp (ref "R17")
      (value "75K 0.1%")
      (footprint "eagle-import:R0805")
      (libsource (lib "eagle-import") (part "R-EU_R0805"))
    )
    (comp (ref "R18")
      (value "9K09 0.1%")
      (footprint "eagle-import:R0805")
      (libsource (lib "eagle-import") (part "R-EU_R0805"))
    )
    (comp (ref "R19")
      (value "180R")
      (footprint "eagle-import:R0805")
      (libsource (lib "eagle-import") (part "R-EU_R0805"))
    )
    (comp (ref "R20")
      (value "47R")
      (footprint "eagle-import:R0805")
      (libsource (lib "eagle-import") (part "R-EU_R0805"))
    )
    (comp (ref "R21")
      (value "9K09 0.1%")
      (footprint "eagle-import:R0805")
      (libsource (lib "eagle-import") (part "R-EU_R0805"))
    )
    (comp (ref "R22")
      (value "9K09 0.1%")
      (footprint "eagle-import:R0805")
      (libsource (lib "eagle-import") (part "R-EU_R0805"))
    )
    (comp (ref "R23")
      (value "75K 0.1%")
      (footprint "eagle-import:R0805")
      (libsource (lib "eagle-import") (part "R-EU_R0805"))
    )
    (comp (ref "R24")
      (value "9K09 0.1%")
      (footprint "eagle-import:R0805")
      (libsource (lib "eagle-import") (part "R-EU_R0805"))
    )
    (comp (ref "R25")
      (value "75K 0.1%")
      (footprint "eagle-import:R0805")
      (libsource (lib "eagle-import") (part "R-EU_R0805"))
    )
    (comp (ref "R26")
      (value "180R")
      (footprint "eagle-import:R0805")
      (libsource (lib "eagle-import") (part "R-EU_R0805"))
    )
    (comp (ref "R27")
      (value "47R")
      (footprint "eagle-import:R0805")
      (libsource (lib "eagle-import") (part "R-EU_R0805"))
    )
    (comp (ref "R28")
      (value "9K09 0.1%")
      (footprint "eagle-import:R0805")
      (libsource (lib "eagle-import") (part "R-EU_R0805"))
    )
    (comp (ref "R29")
      (value "75K 0.1%")
      (footprint "eagle-import:R0805")
      (libsource (lib "eagle-import") (part "R-EU_R0805"))
    )
    (comp (ref "R30")
      (value "10K")
      (footprint "eagle-import:R0805")
      (libsource (lib "eagle-import") (part "R-EU_R0805"))
    )
    (comp (ref "R31")
      (value "100R")
      (footprint "eagle-import:R0805")
      (libsource (lib "eagle-import") (part "R-EU_R0805"))
    )
    (comp (ref "R32")
      (value "100R")
      (footprint "eagle-import:R0805")
      (libsource (lib "eagle-import") (part "R-EU_R0805"))
    )
    (comp (ref "SH4")
      (value "SHORTNOHOLE")
      (footprint "eagle-import:SHORT_NOHOLE")
      (libsource (lib "eagle-import") (part "SHORTNOHOLE"))
    )
    (comp (ref "TVS3")
      (value "PESD12VL1BA,115")
      (footprint "eagle-import:SOD323-BIDIR")
      (libsource (lib "eagle-import") (part "PESDXL1BA"))
    )
    (comp (ref "TVS4")
      (value "PESD12VL1BA,115")
      (footprint "eagle-import:SOD323-BIDIR")
      (libsource (lib "eagle-import") (part "PESDXL1BA"))
    )
    (comp (ref "X3")
      (value "691327310016")
      (footprint "eagle-import:691327310016")
      (libsource (lib "eagle-import") (part "691327310016"))
    )
    (comp (ref "C41")
      (value "2n2")
      (footprint "eagle-import:C0805")
      (libsource (lib "eagle-import") (part "C-EUC0805"))
    )
    (comp (ref "C42")
      (value "100n")
      (footprint "eagle-import:C0603")
      (libsource (lib "eagle-import") (part "C-EUC0603"))
    )
    (comp (ref "C43")
      (value "100n")
      (footprint "eagle-import:C0603")
      (libsource (lib "eagle-import") (part "C-EUC0603"))
    )
    (comp (ref "C44")
      (value "22n")
      (footprint "eagle-import:C0805")
      (libsource (lib "eagle-import") (part "C-EUC0805"))
    )
    (comp (ref "C45")
      (value "100n")
      (footprint "eagle-import:C0603")
      (libsource (lib "eagle-import") (part "C-EUC0603"))
    )
    (comp (ref "C46")
      (value "100n")
      (footprint "eagle-import:C0603")
      (libsource (lib "eagle-import") (part "C-EUC0603"))
    )
    (comp (ref "C47")
      (value "100n")
      (footprint "eagle-import:C0603")
      (libsource (lib "eagle-import") (part "C-EUC0603"))
    )
    (comp (ref "C48")
      (value "4u7")
      (footprint "eagle-import:C0805")
      (libsource (lib "eagle-import") (part "C-EUC0805"))
    )
    (comp (ref "C49")
      (value "4u7")
      (footprint "eagle-import:C0805")
      (libsource (lib "eagle-import") (part "C-EUC0805"))
    )
    (comp (ref "C50")
      (value "2n2")
      (footprint "eagle-import:C0805")
      (libsource (lib "eagle-import") (part "C-EUC0805"))
    )
    (comp (ref "C51")
      (value "100n")
      (footprint "eagle-import:C0603")
      (libsource (lib "eagle-import") (part "C-EUC0603"))
    )
    (comp (ref "C52")
      (value "100n")
      (footprint "eagle-import:C0603")
      (libsource (lib "eagle-import") (part "C-EUC0603"))
    )
    (comp (ref "C53")
      (value "22n")
      (footprint "eagle-import:C0805")
      (libsource (lib "eagle-import") (part "C-EUC0805"))
    )
    (comp (ref "C54")
      (value "100n")
      (footprint "eagle-import:C0603")
      (libsource (lib "eagle-import") (part "C-EUC0603"))
    )
    (comp (ref "C55")
      (value "100n")
      (footprint "eagle-import:C0603")
      (libsource (lib "eagle-import") (part "C-EUC0603"))
    )
    (comp (ref "C56")
      (value "100n")
      (footprint "eagle-import:C0603")
      (libsource (lib "eagle-import") (part "C-EUC0603"))
    )
    (comp (ref "C57")
      (value "100n")
      (footprint "eagle-import:C0603")
      (libsource (lib "eagle-import") (part "C-EUC0603"))
    )
    (comp (ref "C58")
      (value "100n")
      (footprint "eagle-import:C0603")
      (libsource (lib "eagle-import") (part "C-EUC0603"))
    )
    (comp (ref "C59")
      (value "4u7")
      (footprint "eagle-import:C0805")
      (libsource (lib "eagle-import") (part "C-EUC0805"))
    )
    (comp (ref "C60")
      (value "4u7")
      (footprint "eagle-import:C0805")
      (libsource (lib "eagle-import") (part "C-EUC0805"))
    )
    (comp (ref "D1")
      (value "BAT54SFILM")
      (footprint "eagle-import:SOT23")
      (libsource (lib "eagle-import") (part "BAT54S"))
    )
    (comp (ref "D2")
      (value "BAT54SFILM")
      (footprint "eagle-import:SOT23")
      (libsource (lib "eagle-import") (part "BAT54S"))
    )
    (comp (ref "FB2")
      (value "BLM18AG102SH1D")
      (footprint "eagle-import:BEAD0603")
      (libsource (lib "eagle-import") (part "FERRITE_BEAD0603"))
    )
    (comp (ref "FB3")
      (value "BLM18AG102SH1D")
      (footprint "eagle-import:BEAD0603")
      (libsource (lib "eagle-import") (part "FERRITE_BEAD0603"))
    )
    (comp (ref "IC9")
      (value "OPA2196IDR")
      (footprint "eagle-import:SOIC127P600X173-8N")
      (libsource (lib "eagle-import") (part "TL072SOIC8"))
    )
    (comp (ref "IC10")
      (value "DAC7760IPWPR")
      (footprint "eagle-import:PWP24")
      (libsource (lib "eagle-import") (part "DAC7760IPWPR"))
    )
    (comp (ref "IC11")
      (value "DAC7760IPWPR")
      (footprint "eagle-import:PWP24")
      (libsource (lib "eagle-import") (part "DAC7760IPWPR"))
    )
    (comp (ref "R9")
      (value "15R")
      (footprint "eagle-import:R0805")
      (libsource (lib "eagle-import") (part "R-EU_R0805"))
    )
    (comp (ref "R10")
      (value "N.C.")
      (footprint "eagle-import:R0805")
      (libsource (lib "eagle-import") (part "R-EU_R0805"))
    )
    (comp (ref "R11")
      (value "15R")
      (footprint "eagle-import:R0805")
      (libsource (lib "eagle-import") (part "R-EU_R0805"))
    )
    (comp (ref "R12")
      (value "10K")
      (footprint "eagle-import:R0805")
      (libsource (lib "eagle-import") (part "R-EU_R0805"))
    )
    (comp (ref "R13")
      (value "15R")
      (footprint "eagle-import:R0805")
      (libsource (lib "eagle-import") (part "R-EU_R0805"))
    )
    (comp (ref "R14")
      (value "N.C.")
      (footprint "eagle-import:R0805")
      (libsource (lib "eagle-import") (part "R-EU_R0805"))
    )
    (comp (ref "R15")
      (value "15R")
      (footprint "eagle-import:R0805")
      (libsource (lib "eagle-import") (part "R-EU_R0805"))
    )
    (comp (ref "SH2")
      (value "SHORTNOHOLE")
      (footprint "eagle-import:SHORT_NOHOLE")
      (libsource (lib "eagle-import") (part "SHORTNOHOLE"))
    )
    (comp (ref "SH3")
      (value "SHORTNOHOLE")
      (footprint "eagle-import:SHORT_NOHOLE")
      (libsource (lib "eagle-import") (part "SHORTNOHOLE"))
    )
    (comp (ref "TVS1")
      (value "PESD12VL1BA,115")
      (footprint "eagle-import:SOD323-BIDIR")
      (libsource (lib "eagle-import") (part "PESDXL1BA"))
    )
    (comp (ref "TVS2")
      (value "PESD12VL1BA,115")
      (footprint "eagle-import:SOD323-BIDIR")
      (libsource (lib "eagle-import") (part "PESDXL1BA"))
    )
  )
  (nets
    (net (code "1") (name "+3V3") (class "Default")
      (node (ref "C1") (pin "2") (pinfunction "2_2") (pintype "passive"))
      (node (ref "C2") (pin "1") (pinfunction "1_1") (pintype "passive"))
      (node (ref "C4") (pin "1") (pinfunction "1_1") (pintype "passive"))
      (node (ref "IC1") (pin "8") (pinfunction "VCC_8") (pintype "power_in"))
      (node (ref "IC2") (pin "1") (pinfunction "VDD1_1") (pintype "passive"))
      (node (ref "IC2") (pin "7") (pinfunction "EN1_7") (pintype "input"))
      (node (ref "IC3") (pin "1") (pinfunction "VDD1_1") (pintype "passive"))
      (node (ref "IC3") (pin "7") (pinfunction "EN1_7") (pintype "input"))
      (node (ref "RN3") (pin "6") (pinfunction "2_6") (pintype "passive"))
      (node (ref "RN3") (pin "7") (pinfunction "2_7") (pintype "passive"))
      (node (ref "RN3") (pin "8") (pinfunction "2_8") (pintype "passive"))
      (node (ref "X1") (pin "1") (pinfunction "1_1") (pintype "passive"))
    )
    (net (code "2") (name "+3V3_ISO") (class "Default")
      (node (ref "C14") (pin "1") (pinfunction "1_1") (pintype "passive"))
      (node (ref "C21") (pin "1") (pinfunction "1_1") (pintype "passive"))
      (node (ref "C3") (pin "2") (pinfunction "2_2") (pintype "passive"))
      (node (ref "C43") (pin "1") (pinfunction "1_1") (pintype "passive"))
      (node (ref "C5") (pin "2") (pinfunction "2_2") (pintype "passive"))
      (node (ref "C52") (pin "1") (pinfunction "1_1") (pintype "passive"))
      (node (ref "C73") (pin "2") (pinfunction "2_2") (pintype "passive"))
      (node (ref "C95") (pin "2") (pinfunction "2_2") (pintype "passive"))
      (node (ref "FB4") (pin "P$2") (pinfunction "2_P$2") (pintype "passive"))
      (node (ref "IC10") (pin "2") (pinfunction "DVDD_2") (pintype "power_in"))
      (node (ref "IC11") (pin "2") (pinfunction "DVDD_2") (pintype "power_in"))
      (node (ref "IC19") (pin "14") (pinfunction "V+_14") (pintype "power_in"))
      (node (ref "IC2") (pin "10") (pinfunction "EN2_10") (pintype "input"))
      (node (ref "IC2") (pin "16") (pinfunction "VDD2_16") (pintype "passive"))
      (node (ref "IC3") (pin "10") (pinfunction "EN2_10") (pintype "input"))
      (node (ref "IC3") (pin "16") (pinfunction "VDD2_16") (pintype "passive"))
      (node (ref "IC36") (pin "34") (pinfunction "DVDD_34") (pintype "power_in"))
      (node (ref "IC6") (pin "5") (pinfunction "OUT_5") (pintype "passive"))
      (node (ref "J2") (pin "4") (pinfunction "VDD_4") (pintype "power_in"))
      (node (ref "R1") (pin "1") (pinfunction "1_1") (pintype "passive"))
      (node (ref "R12") (pin "1") (pinfunction "1_1") (pintype "passive"))
      (node (ref "R2") (pin "1") (pinfunction "1_1") (pintype "passive"))
      (node (ref "R3") (pin "1") (pinfunction "1_1") (pintype "passive"))
      (node (ref "R30") (pin "1") (pinfunction "1_1") (pintype "passive"))
      (node (ref "R33") (pin "1") (pinfunction "1_1") (pintype "passive"))
      (node (ref "R4") (pin "1") (pinfunction "1_1") (pintype "passive"))
      (node (ref "R5") (pin "1") (pinfunction "1_1") (pintype "passive"))
      (node (ref "SH1") (pin "2") (pinfunction "GND_B_2") (pintype "bidirectional"))
    )
    (net (code "3") (name "+5V_ISO") (class "Default")
      (node (ref "C18") (pin "2") (pinfunction "2_2") (pintype "passive"))
      (node (ref "D5") (pin "2") (pinfunction "C2_2") (pintype "passive"))
      (node (ref "D6") (pin "2") (pinfunction "C2_2") (pintype "passive"))
      (node (ref "FB8") (pin "P$1") (pinfunction "1_P$1") (pintype "passive"))
      (node (ref "IC5") (pin "5") (pinfunction "OUT_5") (pintype "passive"))
      (node (ref "IC6") (pin "1") (pinfunction "IN_1") (pintype "input"))
      (node (ref "IC6") (pin "3") (pinfunction "ON/~{OFF}_3") (pintype "input"))
    )
    (net (code "4") (name "+12V") (class "Default")
      (node (ref "C7") (pin "2") (pinfunction "2_2") (pintype "passive"))
      (node (ref "L1") (pin "4") (pinfunction "4_4") (pintype "passive"))
      (node (ref "X1") (pin "21") (pinfunction "1_21") (pintype "passive"))
      (node (ref "X1") (pin "22") (pinfunction "1_22") (pintype "passive"))
    )
    (net (code "5") (name "+12V_ISO") (class "Default")
      (node (ref "C10") (pin "1") (pinfunction "1_1") (pintype "passive"))
      (node (ref "C16") (pin "2") (pinfunction "2_2") (pintype "passive"))
      (node (ref "C47") (pin "1") (pinfunction "1_1") (pintype "passive"))
      (node (ref "C49") (pin "2") (pinfunction "2_2") (pintype "passive"))
      (node (ref "C55") (pin "1") (pinfunction "1_1") (pintype "passive"))
      (node (ref "C57") (pin "1") (pinfunction "1_1") (pintype "passive"))
      (node (ref "C60") (pin "2") (pinfunction "2_2") (pintype "passive"))
      (node (ref "C61") (pin "1") (pinfunction "1_1") (pintype "passive"))
      (node (ref "C69") (pin "2") (pinfunction "2_2") (pintype "passive"))
      (node (ref "C70") (pin "2") (pinfunction "2_2") (pintype "passive"))
      (node (ref "C71") (pin "2") (pinfunction "2_2") (pintype "passive"))
      (node (ref "C72") (pin "2") (pinfunction "2_2") (pintype "passive"))
      (node (ref "D1") (pin "2") (pinfunction "C2_2") (pintype "passive"))
      (node (ref "D2") (pin "2") (pinfunction "C2_2") (pintype "passive"))
      (node (ref "D3") (pin "2") (pinfunction "C2_2") (pintype "passive"))
      (node (ref "D4") (pin "2") (pinfunction "C2_2") (pintype "passive"))
      (node (ref "IC10") (pin "24") (pinfunction "AVDD_24") (pintype "power_in"))
      (node (ref "IC11") (pin "24") (pinfunction "AVDD_24") (pintype "power_in"))
      (node (ref "IC14") (pin "8") (pinfunction "V+_8") (pintype "power_in"))
      (node (ref "IC15") (pin "8") (pinfunction "VSS_8") (pintype "passive"))
      (node (ref "IC16") (pin "8") (pinfunction "VSS_8") (pintype "passive"))
      (node (ref "IC17") (pin "8") (pinfunction "VSS_8") (pintype "passive"))
      (node (ref "IC18") (pin "8") (pinfunction "VSS_8") (pintype "passive"))
      (node (ref "IC4") (pin "1") (pinfunction "VO_1") (pintype "passive"))
      (node (ref "IC5") (pin "1") (pinfunction "IN_1") (pintype "input"))
      (node (ref "IC5") (pin "3") (pinfunction "ON/~{OFF}_3") (pintype "input"))
      (node (ref "IC9") (pin "8") (pinfunction "V+_8") (pintype "power_in"))
      (node (ref "JP1") (pin "2") (pinfunction "2_2") (pintype "passive"))
    )
    (net (code "6") (name "+15V_ISO") (class "Default")
      (node (ref "C11") (pin "2") (pinfunction "2_2") (pintype "passive"))
      (node (ref "C86") (pin "1") (pinfunction "1_1") (pintype "passive"))
      (node (ref "IC21") (pin "5") (pinfunction "V+_5") (pintype "passive"))
      (node (ref "IC22") (pin "5") (pinfunction "V+_5") (pintype "passive"))
      (node (ref "IC23") (pin "5") (pinfunction "V+_5") (pintype "passive"))
      (node (ref "IC24") (pin "5") (pinfunction "V+_5") (pintype "passive"))
      (node (ref "IC25") (pin "5") (pinfunction "V+_5") (pintype "passive"))
      (node (ref "IC26") (pin "5") (pinfunction "V+_5") (pintype "passive"))
      (node (ref "IC27") (pin "5") (pinfunction "V+_5") (pintype "passive"))
      (node (ref "IC28") (pin "5") (pinfunction "V+_5") (pintype "passive"))
      (node (ref "IC29") (pin "5") (pinfunction "V+_5") (pintype "passive"))
      (node (ref "IC30") (pin "5") (pinfunction "V+_5") (pintype "passive"))
      (node (ref "IC31") (pin "5") (pinfunction "V+_5") (pintype "passive"))
      (node (ref "IC32") (pin "5") (pinfunction "V+_5") (pintype "passive"))
      (node (ref "IC33") (pin "5") (pinfunction "V+_5") (pintype "passive"))
      (node (ref "IC34") (pin "5") (pinfunction "V+_5") (pintype "passive"))
      (node (ref "IC4") (pin "8") (pinfunction "VI_8") (pintype "input"))
      (node (ref "JP1") (pin "1") (pinfunction "1_1") (pintype "passive"))
      (node (ref "L2") (pin "2") (pinfunction "2_2") (pintype "passive"))
    )
    (net (code "7") (name "-12V_ISO") (class "Default")
      (node (ref "C13") (pin "2") (pinfunction "2_2") (pintype "passive"))
      (node (ref "C46") (pin "1") (pinfunction "1_1") (pintype "passive"))
      (node (ref "C48") (pin "2") (pinfunction "2_2") (pintype "passive"))
      (node (ref "C56") (pin "1") (pinfunction "1_1") (pintype "passive"))
      (node (ref "C58") (pin "1") (pinfunction "1_1") (pintype "passive"))
      (node (ref "C59") (pin "2") (pinfunction "2_2") (pintype "passive"))
      (node (ref "C64") (pin "1") (pinfunction "1_1") (pintype "passive"))
      (node (ref "D1") (pin "1") (pinfunction "A1_1") (pintype "passive"))
      (node (ref "D2") (pin "1") (pinfunction "A1_1") (pintype "passive"))
      (node (ref "D3") (pin "1") (pinfunction "A1_1") (pintype "passive"))
      (node (ref "D4") (pin "1") (pinfunction "A1_1") (pintype "passive"))
      (node (ref "IC10") (pin "1") (pinfunction "AVSS_1") (pintype "power_in"))
      (node (ref "IC10") (pin "25") (pinfunction "EPAD_25") (pintype "passive"))
      (node (ref "IC11") (pin "1") (pinfunction "AVSS_1") (pintype "power_in"))
      (node (ref "IC11") (pin "25") (pinfunction "EPAD_25") (pintype "passive"))
      (node (ref "IC14") (pin "4") (pinfunction "V-_4") (pintype "power_in"))
      (node (ref "IC7") (pin "1") (pinfunction "OUT_1") (pintype "passive"))
      (node (ref "IC9") (pin "4") (pinfunction "V-_4") (pintype "power_in"))
      (node (ref "JP2") (pin "2") (pinfunction "2_2") (pintype "passive"))
      (node (ref "R64") (pin "1") (pinfunction "1_1") (pintype "passive"))
      (node (ref "R65") (pin "1") (pinfunction "1_1") (pintype "passive"))
      (node (ref "R66") (pin "1") (pinfunction "1_1") (pintype "passive"))
      (node (ref "R67") (pin "1") (pinfunction "1_1") (pintype "passive"))
    )
    (net (code "8") (name "-15V_ISO") (class "Default")
      (node (ref "C15") (pin "1") (pinfunction "1_1") (pintype "passive"))
      (node (ref "C87") (pin "1") (pinfunction "1_1") (pintype "passive"))
      (node (ref "IC21") (pin "2") (pinfunction "V-_2") (pintype "passive"))
      (node (ref "IC22") (pin "2") (pinfunction "V-_2") (pintype "passive"))
      (node (ref "IC23") (pin "2") (pinfunction "V-_2") (pintype "passive"))
      (node (ref "IC24") (pin "2") (pinfunction "V-_2") (pintype "passive"))
      (node (ref "IC25") (pin "2") (pinfunction "V-_2") (pintype "passive"))
      (node (ref "IC26") (pin "2") (pinfunction "V-_2") (pintype "passive"))
      (node (ref "IC27") (pin "2") (pinfunction "V-_2") (pintype "passive"))
      (node (ref "IC28") (pin "2") (pinfunction "V-_2") (pintype "passive"))
      (node (ref "IC29") (pin "2") (pinfunction "V-_2") (pintype "passive"))
      (node (ref "IC30") (pin "2") (pinfunction "V-_2") (pintype "passive"))
      (node (ref "IC31") (pin "2") (pinfunction "V-_2") (pintype "passive"))
      (node (ref "IC32") (pin "2") (pinfunction "V-_2") (pintype "passive"))
      (node (ref "IC33") (pin "2") (pinfunction "V-_2") (pintype "passive"))
      (node (ref "IC34") (pin "2") (pinfunction "V-_2") (pintype "passive"))
      (node (ref "IC7") (pin "2") (pinfunction "IN_2") (pintype "input"))
      (node (ref "IC7") (pin "3") (pinfunction "IN_3") (pintype "input"))
      (node (ref "IC7") (pin "6") (pinfunction "IN_6") (pintype "input"))
      (node (ref "IC7") (pin "7") (pinfunction "IN_7") (pintype "input"))
      (node (ref "JP2") (pin "1") (pinfunction "1_1") (pintype "passive"))
      (node (ref "L3") (pin "3") (pinfunction "3_3") (pintype "passive"))
    )
    (net (code "19") (name "1V25_REF") (class "Default")
      (node (ref "IC12") (pin "1") (pinfunction "OUT_1") (pintype "output"))
      (node (ref "IC12") (pin "4") (pinfunction "-IN_4") (pintype "input"))
      (node (ref "JP3") (pin "NO") (pinfunction "NO_NO") (pintype "passive"))
      (node (ref "R16") (pin "2") (pinfunction "2_2") (pintype "passive"))
      (node (ref "R24") (pin "2") (pinfunction "2_2") (pintype "passive"))
    )
    (net (code "20") (name "ADC_AVDD") (class "Default")
      (node (ref "C88") (pin "1") (pinfunction "1_1") (pintype "passive"))
      (node (ref "C94") (pin "2") (pinfunction "2_2") (pintype "passive"))
      (node (ref "FB8") (pin "P$2") (pinfunction "2_P$2") (pintype "passive"))
      (node (ref "IC35") (pin "5") (pinfunction "V+_5") (pintype "power_in"))
      (node (ref "IC36") (pin "30") (pinfunction "AVDD_30") (pintype "power_in"))
      (node (ref "IC36") (pin "9") (pinfunction "AVDD_9") (pintype "power_in"))
    )
    (net (code "21") (name "ADC_IRQ") (class "Default")
      (node (ref "IC36") (pin "35") (pinfunction "ALARM_35") (pintype "output"))
      (node (ref "IC8") (pin "77") (pinfunction "PD8_77") (pintype "bidirectional"))
    )
    (net (code "22") (name "ADC_MISO") (class "Default")
      (node (ref "IC36") (pin "36") (pinfunction "SDO_36") (pintype "output"))
      (node (ref "RN5") (pin "3") (pinfunction "1_3") (pintype "passive"))
    )
    (net (code "23") (name "ADC_MOSI") (class "Default")
      (node (ref "IC36") (pin "1") (pinfunction "SDI_1") (pintype "input"))
      (node (ref "RN5") (pin "4") (pinfunction "1_4") (pintype "passive"))
    )
    (net (code "24") (name "ADC_SCLK") (class "Default")
      (node (ref "IC36") (pin "37") (pinfunction "SCLK_37") (pintype "input"))
      (node (ref "RN5") (pin "2") (pinfunction "1_2") (pintype "passive"))
    )
    (net (code "25") (name "ADC_VREF") (class "Default")
      (node (ref "C91") (pin "2") (pinfunction "2_2") (pintype "passive"))
      (node (ref "IC35") (pin "3") (pinfunction "+IN_3") (pintype "input"))
      (node (ref "IC36") (pin "5") (pinfunction "REFIO_5") (pintype "bidirectional"))
    )
    (net (code "26") (name "AIN_0GND") (class "Default")
      (node (ref "C89") (pin "1") (pinfunction "1_1") (pintype "passive"))
      (node (ref "IC36") (pin "17") (pinfunction "AIN_0GND_17") (pintype "input"))
      (node (ref "R69") (pin "2") (pinfunction "2_2") (pintype "passive"))
    )
    (net (code "27") (name "AIN_0P") (class "Default")
      (node (ref "C89") (pin "2") (pinfunction "2_2") (pintype "passive"))
      (node (ref "IC36") (pin "16") (pinfunction "AIN_0P_16") (pintype "input"))
      (node (ref "R63") (pin "2") (pinfunction "2_2") (pintype "passive"))
      (node (ref "R66") (pin "2") (pinfunction "2_2") (pintype "passive"))
    )
    (net (code "28") (name "AIN_1GND") (class "Default")
      (node (ref "C90") (pin "1") (pinfunction "1_1") (pintype "passive"))
      (node (ref "IC36") (pin "19") (pinfunction "AIN_1GND_19") (pintype "input"))
      (node (ref "R73") (pin "2") (pinfunction "2_2") (pintype "passive"))
    )
    (net (code "29") (name "AIN_1P") (class "Default")
      (node (ref "C90") (pin "2") (pinfunction "2_2") (pintype "passive"))
      (node (ref "IC36") (pin "18") (pinfunction "AIN_1P_18") (pintype "input"))
      (node (ref "R64") (pin "2") (pinfunction "2_2") (pintype "passive"))
      (node (ref "R71") (pin "2") (pinfunction "2_2") (pintype "passive"))
    )
    (net (code "30") (name "AIN_2GND") (class "Default")
      (node (ref "C96") (pin "1") (pinfunction "1_1") (pintype "passive"))
      (node (ref "IC36") (pin "20") (pinfunction "AIN_2GND_20") (pintype "input"))
      (node (ref "R77") (pin "2") (pinfunction "2_2") (pintype "passive"))
    )
    (net (code "31") (name "AIN_2P") (class "Default")
      (node (ref "C96") (pin "2") (pinfunction "2_2") (pintype "passive"))
      (node (ref "IC36") (pin "21") (pinfunction "AIN_2P_21") (pintype "input"))
      (node (ref "R67") (pin "2") (pinfunction "2_2") (pintype "passive"))
      (node (ref "R75") (pin "2") (pinfunction "2_2") (pintype "passive"))
    )
    (net (code "32") (name "AIN_3GND") (class "Default")
      (node (ref "C97") (pin "1") (pinfunction "1_1") (pintype "passive"))
      (node (ref "IC36") (pin "22") (pinfunction "AIN_3GND_22") (pintype "input"))
      (node (ref "R83") (pin "2") (pinfunction "2_2") (pintype "passive"))
    )
    (net (code "33") (name "AIN_3P") (class "Default")
      (node (ref "C97") (pin "2") (pinfunction "2_2") (pintype "passive"))
      (node (ref "IC36") (pin "23") (pinfunction "AIN_3P_23") (pintype "input"))
      (node (ref "R65") (pin "2") (pinfunction "2_2") (pintype "passive"))
      (node (ref "R79") (pin "2") (pinfunction "2_2") (pintype "passive"))
    )
    (net (code "34") (name "BOOT0") (class "Default")
      (node (ref "IC3") (pin "13") (pinfunction "B2_13") (pintype "output"))
      (node (ref "IC8") (pin "138") (pinfunction "BOOT0_138") (pintype "input"))
      (node (ref "R7") (pin "2") (pinfunction "2_2") (pintype "passive"))
    )
    (net (code "35") (name "CLAMP") (class "Default")
      (node (ref "C74") (pin "1") (pinfunction "1_1") (pintype "passive"))
      (node (ref "C75") (pin "1") (pinfunction "1_1") (pintype "passive"))
      (node (ref "D10") (pin "2") (pinfunction "C2_2") (pintype "passive"))
      (node (ref "D11") (pin "2") (pinfunction "C2_2") (pintype "passive"))
      (node (ref "D12") (pin "2") (pinfunction "C2_2") (pintype "passive"))
      (node (ref "D13") (pin "2") (pinfunction "C2_2") (pintype "passive"))
      (node (ref "D14") (pin "2") (pinfunction "C2_2") (pintype "passive"))
      (node (ref "D7") (pin "2") (pinfunction "C2_2") (pintype "passive"))
      (node (ref "D8") (pin "2") (pinfunction "C2_2") (pintype "passive"))
      (node (ref "D9") (pin "2") (pinfunction "C2_2") (pintype "passive"))
      (node (ref "IC20") (pin "1") (pinfunction "C_1") (pintype "passive"))
      (node (ref "R33") (pin "2") (pinfunction "2_2") (pintype "passive"))
      (node (ref "R34") (pin "1") (pinfunction "1_1") (pintype "passive"))
    )
    (net (code "36") (name "CURR_SW0") (class "Default")
      (node (ref "IC22") (pin "3") (pinfunction "IN_3") (pintype "input"))
      (node (ref "IC27") (pin "3") (pinfunction "IN_3") (pintype "input"))
      (node (ref "IC8") (pin "117") (pinfunction "PD3_117") (pintype "bidirectional"))
    )
    (net (code "37") (name "CURR_SW1") (class "Default")
      (node (ref "IC23") (pin "3") (pinfunction "IN_3") (pintype "input"))
      (node (ref "IC28") (pin "3") (pinfunction "IN_3") (pintype "input"))
      (node (ref "IC8") (pin "118") (pinfunction "PD4_118") (pintype "bidirectional"))
    )
    (net (code "38") (name "CURR_SW2") (class "Default")
      (node (ref "IC24") (pin "3") (pinfunction "IN_3") (pintype "input"))
      (node (ref "IC29") (pin "3") (pinfunction "IN_3") (pintype "input"))
      (node (ref "IC8") (pin "119") (pinfunction "PD5_119") (pintype "bidirectional"))
    )
    (net (code "39") (name "CURR_SW3") (class "Default")
      (node (ref "IC25") (pin "3") (pinfunction "IN_3") (pintype "input"))
      (node (ref "IC30") (pin "3") (pinfunction "IN_3") (pintype "input"))
      (node (ref "IC8") (pin "122") (pinfunction "PD6_122") (pintype "bidirectional"))
    )
    (net (code "40") (name "DAC_CLR#1") (class "Default")
      (node (ref "IC10") (pin "6") (pinfunction "CLR_6") (pintype "input"))
      (node (ref "IC8") (pin "21") (pinfunction "PF9_21") (pintype "bidirectional"))
    )
    (net (code "41") (name "DAC_CLR#2") (class "Default")
      (node (ref "IC11") (pin "6") (pinfunction "CLR_6") (pintype "input"))
      (node (ref "IC8") (pin "19") (pinfunction "PF7_19") (pintype "bidirectional"))
    )
    (net (code "42") (name "DAC_CLR-SEL#1") (class "Default")
      (node (ref "IC10") (pin "5") (pinfunction "CLR-SEL_5") (pintype "input"))
      (node (ref "IC8") (pin "22") (pinfunction "PF10_22") (pintype "bidirectional"))
    )
    (net (code "43") (name "DAC_CLR-SEL#2") (class "Default")
      (node (ref "IC11") (pin "5") (pinfunction "CLR-SEL_5") (pintype "input"))
      (node (ref "IC8") (pin "20") (pinfunction "PF8_20") (pintype "bidirectional"))
    )
    (net (code "44") (name "DAC_CS#1") (class "Default")
      (node (ref "IC10") (pin "7") (pinfunction "LATCH_7") (pintype "input"))
      (node (ref "IC8") (pin "27") (pinfunction "PC1_27") (pintype "bidirectional"))
    )
    (net (code "45") (name "DAC_CS#2") (class "Default")
      (node (ref "IC11") (pin "7") (pinfunction "LATCH_7") (pintype "input"))
      (node (ref "IC8") (pin "18") (pinfunction "PF6_18") (pintype "bidirectional"))
    )
    (net (code "46") (name "DAC_MISO") (class "Default")
      (node (ref "IC10") (pin "10") (pinfunction "SDO_10") (pintype "output"))
      (node (ref "IC11") (pin "10") (pinfunction "SDO_10") (pintype "output"))
      (node (ref "RN4") (pin "3") (pinfunction "1_3") (pintype "passive"))
    )
    (net (code "47") (name "DAC_MOSI") (class "Default")
      (node (ref "IC10") (pin "9") (pinfunction "DIN_9") (pintype "input"))
      (node (ref "IC11") (pin "9") (pinfunction "DIN_9") (pintype "input"))
      (node (ref "IC13") (pin "8") (pinfunction "DIN_8") (pintype "input"))
      (node (ref "RN4") (pin "4") (pinfunction "1_4") (pintype "passive"))
    )
    (net (code "48") (name "DAC_SCLK") (class "Default")
      (node (ref "IC10") (pin "8") (pinfunction "SCLK_8") (pintype "input"))
      (node (ref "IC11") (pin "8") (pinfunction "SCLK_8") (pintype "input"))
      (node (ref "IC13") (pin "7") (pinfunction "SCLK_7") (pintype "input"))
      (node (ref "RN4") (pin "2") (pinfunction "1_2") (pintype "passive"))
    )
    (net (code "49") (name "DIB_A0") (class "Default")
      (node (ref "IC1") (pin "1") (pinfunction "A0_1") (pintype "input"))
      (node (ref "RN3") (pin "3") (pinfunction "1_3") (pintype "passive"))
      (node (ref "X1") (pin "17") (pinfunction "1_17") (pintype "passive"))
    )
    (net (code "50") (name "DIB_A1") (class "Default")
      (node (ref "IC1") (pin "2") (pinfunction "A1_2") (pintype "input"))
      (node (ref "RN3") (pin "2") (pinfunction "1_2") (pintype "passive"))
      (node (ref "X1") (pin "19") (pinfunction "1_19") (pintype "passive"))
    )
    (net (code "51") (name "DIB_A2") (class "Default")
      (node (ref "IC1") (pin "3") (pinfunction "A2_3") (pintype "input"))
      (node (ref "RN3") (pin "1") (pinfunction "1_1") (pintype "passive"))
      (node (ref "X1") (pin "18") (pinfunction "1_18") (pintype "passive"))
    )
    (net (code "52") (name "DIB_BOOT") (class "Default")
      (node (ref "IC3") (pin "4") (pinfunction "A2_4") (pintype "input"))
      (node (ref "X1") (pin "26") (pinfunction "1_26") (pintype "passive"))
    )
    (net (code "53") (name "DIB_CSA") (class "Default")
      (node (ref "IC2") (pin "5") (pinfunction "A3_5") (pintype "input"))
      (node (ref "RN2") (pin "2") (pinfunction "1_2") (pintype "passive"))
    )
    (net (code "54") (name "DIB_CSB") (class "Default")
      (node (ref "DIB1.1") (pin "NO") (pinfunction "NO_NO") (pintype "passive"))
      (node (ref "X1") (pin "12") (pinfunction "1_12") (pintype "passive"))
    )
    (net (code "55") (name "DIB_IRQ") (class "Default")
      (node (ref "DIB1.1") (pin "NC") (pinfunction "NC_NC") (pintype "passive"))
      (node (ref "X1") (pin "10") (pinfunction "1_10") (pintype "passive"))
    )
    (net (code "56") (name "DIB_MISO") (class "Default")
      (node (ref "IC2") (pin "6") (pinfunction "A4_6") (pintype "output"))
      (node (ref "RN2") (pin "1") (pinfunction "1_1") (pintype "passive"))
    )
    (net (code "57") (name "DIB_MOSI") (class "Default")
      (node (ref "IC2") (pin "3") (pinfunction "A1_3") (pintype "input"))
      (node (ref "RN2") (pin "4") (pinfunction "1_4") (pintype "passive"))
    )
    (net (code "58") (name "DIB_NRESET") (class "Default")
      (node (ref "IC3") (pin "5") (pinfunction "A3_5") (pintype "input"))
      (node (ref "X1") (pin "4") (pinfunction "1_4") (pintype "passive"))
    )
    (net (code "59") (name "DIB_SCL") (class "Default")
      (node (ref "IC1") (pin "6") (pinfunction "SCL_6") (pintype "bidirectional"))
      (node (ref "X1") (pin "5") (pinfunction "1_5") (pintype "passive"))
    )
    (net (code "60") (name "DIB_SCLK") (class "Default")
      (node (ref "IC2") (pin "4") (pinfunction "A2_4") (pintype "input"))
      (node (ref "RN2") (pin "3") (pinfunction "1_3") (pintype "passive"))
    )
    (net (code "61") (name "DIB_SDA") (class "Default")
      (node (ref "IC1") (pin "5") (pinfunction "SDA_5") (pintype "bidirectional"))
      (node (ref "X1") (pin "8") (pinfunction "1_8") (pintype "passive"))
    )
    (net (code "62") (name "DIN0") (class "Default")
      (node (ref "C76") (pin "1") (pinfunction "1_1") (pintype "passive"))
      (node (ref "C81") (pin "1") (pinfunction "1_1") (pintype "passive"))
      (node (ref "D7") (pin "3") (pinfunction "C1A2_3") (pintype "passive"))
      (node (ref "IC8") (pin "34") (pinfunction "PA0-WKUP_34") (pintype "bidirectional"))
      (node (ref "R36") (pin "2") (pinfunction "2_2") (pintype "passive"))
      (node (ref "R44") (pin "2") (pinfunction "2_2") (pintype "passive"))
      (node (ref "R52") (pin "1") (pinfunction "1_1") (pintype "passive"))
    )
    (net (code "63") (name "DIN1") (class "Default")
      (node (ref "C77") (pin "1") (pinfunction "1_1") (pintype "passive"))
      (node (ref "C82") (pin "1") (pinfunction "1_1") (pintype "passive"))
      (node (ref "D8") (pin "3") (pinfunction "C1A2_3") (pintype "passive"))
      (node (ref "IC8") (pin "35") (pinfunction "PA1_35") (pintype "bidirectional"))
      (node (ref "R37") (pin "2") (pinfunction "2_2") (pintype "passive"))
      (node (ref "R45") (pin "2") (pinfunction "2_2") (pintype "passive"))
      (node (ref "R53") (pin "1") (pinfunction "1_1") (pintype "passive"))
    )
    (net (code "64") (name "DIN2") (class "Default")
      (node (ref "C78") (pin "1") (pinfunction "1_1") (pintype "passive"))
      (node (ref "D9") (pin "3") (pinfunction "C1A2_3") (pintype "passive"))
      (node (ref "IC8") (pin "96") (pinfunction "PC6_96") (pintype "bidirectional"))
      (node (ref "R38") (pin "2") (pinfunction "2_2") (pintype "passive"))
      (node (ref "R46") (pin "2") (pinfunction "2_2") (pintype "passive"))
      (node (ref "R54") (pin "1") (pinfunction "1_1") (pintype "passive"))
    )
    (net (code "65") (name "DIN3") (class "Default")
      (node (ref "C83") (pin "1") (pinfunction "1_1") (pintype "passive"))
      (node (ref "D10") (pin "3") (pinfunction "C1A2_3") (pintype "passive"))
      (node (ref "IC8") (pin "97") (pinfunction "PC7_97") (pintype "bidirectional"))
      (node (ref "R39") (pin "2") (pinfunction "2_2") (pintype "passive"))
      (node (ref "R47") (pin "2") (pinfunction "2_2") (pintype "passive"))
      (node (ref "R55") (pin "1") (pinfunction "1_1") (pintype "passive"))
    )
    (net (code "66") (name "DIN4") (class "Default")
      (node (ref "C79") (pin "1") (pinfunction "1_1") (pintype "passive"))
      (node (ref "D11") (pin "3") (pinfunction "C1A2_3") (pintype "passive"))
      (node (ref "IC8") (pin "134") (pinfunction "PB4_134") (pintype "bidirectional"))
      (node (ref "R40") (pin "2") (pinfunction "2_2") (pintype "passive"))
      (node (ref "R48") (pin "2") (pinfunction "2_2") (pintype "passive"))
      (node (ref "R56") (pin "1") (pinfunction "1_1") (pintype "passive"))
    )
    (net (code "67") (name "DIN5") (class "Default")
      (node (ref "C84") (pin "1") (pinfunction "1_1") (pintype "passive"))
      (node (ref "D12") (pin "3") (pinfunction "C1A2_3") (pintype "passive"))
      (node (ref "IC8") (pin "135") (pinfunction "PB5_135") (pintype "bidirectional"))
      (node (ref "R41") (pin "2") (pinfunction "2_2") (pintype "passive"))
      (node (ref "R49") (pin "2") (pinfunction "2_2") (pintype "passive"))
      (node (ref "R57") (pin "1") (pinfunction "1_1") (pintype "passive"))
    )
    (net (code "68") (name "DIN6") (class "Default")
      (node (ref "C80") (pin "1") (pinfunction "1_1") (pintype "passive"))
      (node (ref "D13") (pin "3") (pinfunction "C1A2_3") (pintype "passive"))
      (node (ref "IC8") (pin "136") (pinfunction "PB6_136") (pintype "bidirectional"))
      (node (ref "R42") (pin "2") (pinfunction "2_2") (pintype "passive"))
      (node (ref "R50") (pin "2") (pinfunction "2_2") (pintype "passive"))
      (node (ref "R58") (pin "1") (pinfunction "1_1") (pintype "passive"))
    )
    (net (code "69") (name "DIN7") (class "Default")
      (node (ref "C85") (pin "1") (pinfunction "1_1") (pintype "passive"))
      (node (ref "D14") (pin "3") (pinfunction "C1A2_3") (pintype "passive"))
      (node (ref "IC8") (pin "137") (pinfunction "PB7_137") (pintype "bidirectional"))
      (node (ref "R43") (pin "2") (pinfunction "2_2") (pintype "passive"))
      (node (ref "R51") (pin "2") (pinfunction "2_2") (pintype "passive"))
      (node (ref "R59") (pin "1") (pinfunction "1_1") (pintype "passive"))
    )
    (net (code "70") (name "DOUT0") (class "Default")
      (node (ref "IC18") (pin "2") (pinfunction "IN1_2") (pintype "input"))
      (node (ref "IC8") (pin "100") (pinfunction "PA8_100") (pintype "bidirectional"))
    )
    (net (code "71") (name "DOUT1") (class "Default")
      (node (ref "IC18") (pin "3") (pinfunction "IN2_3") (pintype "input"))
      (node (ref "IC8") (pin "101") (pinfunction "PA9_101") (pintype "bidirectional"))
    )
    (net (code "72") (name "DOUT2") (class "Default")
      (node (ref "IC17") (pin "2") (pinfunction "IN1_2") (pintype "input"))
      (node (ref "IC8") (pin "91") (pinfunction "PG6_91") (pintype "bidirectional"))
    )
    (net (code "73") (name "DOUT3") (class "Default")
      (node (ref "IC17") (pin "3") (pinfunction "IN2_3") (pintype "input"))
      (node (ref "IC8") (pin "92") (pinfunction "PG7_92") (pintype "bidirectional"))
    )
    (net (code "74") (name "DOUT4") (class "Default")
      (node (ref "IC16") (pin "2") (pinfunction "IN1_2") (pintype "input"))
      (node (ref "IC8") (pin "44") (pinfunction "PC4_44") (pintype "bidirectional"))
    )
    (net (code "75") (name "DOUT5") (class "Default")
      (node (ref "IC16") (pin "3") (pinfunction "IN2_3") (pintype "input"))
      (node (ref "IC8") (pin "45") (pinfunction "PC5_45") (pintype "bidirectional"))
    )
    (net (code "76") (name "DOUT6") (class "Default")
      (node (ref "IC15") (pin "2") (pinfunction "IN1_2") (pintype "input"))
      (node (ref "IC8") (pin "46") (pinfunction "PB0_46") (pintype "bidirectional"))
    )
    (net (code "77") (name "DOUT7") (class "Default")
      (node (ref "IC15") (pin "3") (pinfunction "IN2_3") (pintype "input"))
      (node (ref "IC8") (pin "47") (pinfunction "PB1_47") (pintype "bidirectional"))
    )
    (net (code "78") (name "GND") (class "Default")
      (node (ref "C10") (pin "2") (pinfunction "2_2") (pintype "passive"))
      (node (ref "C11") (pin "1") (pinfunction "1_1") (pintype "passive"))
      (node (ref "C13") (pin "1") (pinfunction "1_1") (pintype "passive"))
      (node (ref "C14") (pin "2") (pinfunction "2_2") (pintype "passive"))
      (node (ref "C15") (pin "2") (pinfunction "2_2") (pintype "passive"))
      (node (ref "C16") (pin "1") (pinfunction "1_1") (pintype "passive"))
      (node (ref "C17") (pin "1") (pinfunction "1_1") (pintype "passive"))
      (node (ref "C18") (pin "1") (pinfunction "1_1") (pintype "passive"))
      (node (ref "C19") (pin "1") (pinfunction "1_1") (pintype "passive"))
      (node (ref "C21") (pin "2") (pinfunction "2_2") (pintype "passive"))
      (node (ref "C22") (pin "1") (pinfunction "1_1") (pintype "passive"))
      (node (ref "C23") (pin "1") (pinfunction "1_1") (pintype "passive"))
      (node (ref "C25") (pin "-") (pinfunction "-_-") (pintype "passive"))
      (node (ref "C26") (pin "2") (pinfunction "2_2") (pintype "passive"))
      (node (ref "C27") (pin "2") (pinfunction "2_2") (pintype "passive"))
      (node (ref "C28") (pin "2") (pinfunction "2_2") (pintype "passive"))
      (node (ref "C29") (pin "2") (pinfunction "2_2") (pintype "passive"))
      (node (ref "C3") (pin "1") (pinfunction "1_1") (pintype "passive"))
      (node (ref "C30") (pin "2") (pinfunction "2_2") (pintype "passive"))
      (node (ref "C31") (pin "2") (pinfunction "2_2") (pintype "passive"))
      (node (ref "C32") (pin "2") (pinfunction "2_2") (pintype "passive"))
      (node (ref "C33") (pin "2") (pinfunction "2_2") (pintype "passive"))
      (node (ref "C34") (pin "2") (pinfunction "2_2") (pintype "passive"))
      (node (ref "C35") (pin "2") (pinfunction "2_2") (pintype "passive"))
      (node (ref "C36") (pin "2") (pinfunction "2_2") (pintype "passive"))
      (node (ref "C37") (pin "2") (pinfunction "2_2") (pintype "passive"))
      (node (ref "C38") (pin "2") (pinfunction "2_2") (pintype "passive"))
      (node (ref "C39") (pin "1") (pinfunction "1_1") (pintype "passive"))
      (node (ref "C40") (pin "1") (pinfunction "1_1") (pintype "passive"))
      (node (ref "C43") (pin "2") (pinfunction "2_2") (pintype "passive"))
      (node (ref "C44") (pin "1") (pinfunction "1_1") (pintype "passive"))
      (node (ref "C45") (pin "2") (pinfunction "2_2") (pintype "passive"))
      (node (ref "C46") (pin "2") (pinfunction "2_2") (pintype "passive"))
      (node (ref "C47") (pin "2") (pinfunction "2_2") (pintype "passive"))
      (node (ref "C48") (pin "1") (pinfunction "1_1") (pintype "passive"))
      (node (ref "C49") (pin "1") (pinfunction "1_1") (pintype "passive"))
      (node (ref "C5") (pin "1") (pinfunction "1_1") (pintype "passive"))
      (node (ref "C52") (pin "2") (pinfunction "2_2") (pintype "passive"))
      (node (ref "C53") (pin "1") (pinfunction "1_1") (pintype "passive"))
      (node (ref "C54") (pin "2") (pinfunction "2_2") (pintype "passive"))
      (node (ref "C55") (pin "2") (pinfunction "2_2") (pintype "passive"))
      (node (ref "C56") (pin "2") (pinfunction "2_2") (pintype "passive"))
      (node (ref "C57") (pin "2") (pinfunction "2_2") (pintype "passive"))
      (node (ref "C58") (pin "2") (pinfunction "2_2") (pintype "passive"))
      (node (ref "C59") (pin "1") (pinfunction "1_1") (pintype "passive"))
      (node (ref "C60") (pin "1") (pinfunction "1_1") (pintype "passive"))
      (node (ref "C61") (pin "2") (pinfunction "2_2") (pintype "passive"))
      (node (ref "C62") (pin "2") (pinfunction "2_2") (pintype "passive"))
      (node (ref "C63") (pin "1") (pinfunction "1_1") (pintype "passive"))
      (node (ref "C64") (pin "2") (pinfunction "2_2") (pintype "passive"))
      (node (ref "C65") (pin "2") (pinfunction "2_2") (pintype "passive"))
      (node (ref "C66") (pin "1") (pinfunction "1_1") (pintype "passive"))
      (node (ref "C67") (pin "2") (pinfunction "2_2") (pintype "passive"))
      (node (ref "C68") (pin "2") (pinfunction "2_2") (pintype "passive"))
      (node (ref "C69") (pin "1") (pinfunction "1_1") (pintype "passive"))
      (node (ref "C70") (pin "1") (pinfunction "1_1") (pintype "passive"))
      (node (ref "C71") (pin "1") (pinfunction "1_1") (pintype "passive"))
      (node (ref "C72") (pin "1") (pinfunction "1_1") (pintype "passive"))
      (node (ref "C73") (pin "1") (pinfunction "1_1") (pintype "passive"))
      (node (ref "C74") (pin "2") (pinfunction "2_2") (pintype "passive"))
      (node (ref "C75") (pin "2") (pinfunction "2_2") (pintype "passive"))
      (node (ref "C76") (pin "2") (pinfunction "2_2") (pintype "passive"))
      (node (ref "C77") (pin "2") (pinfunction "2_2") (pintype "passive"))
      (node (ref "C78") (pin "2") (pinfunction "2_2") (pintype "passive"))
      (node (ref "C79") (pin "2") (pinfunction "2_2") (pintype "passive"))
      (node (ref "C80") (pin "2") (pinfunction "2_2") (pintype "passive"))
      (node (ref "C83") (pin "2") (pinfunction "2_2") (pintype "passive"))
      (node (ref "C84") (pin "2") (pinfunction "2_2") (pintype "passive"))
      (node (ref "C85") (pin "2") (pinfunction "2_2") (pintype "passive"))
      (node (ref "C86") (pin "2") (pinfunction "2_2") (pintype "passive"))
      (node (ref "C87") (pin "2") (pinfunction "2_2") (pintype "passive"))
      (node (ref "C88") (pin "2") (pinfunction "2_2") (pintype "passive"))
      (node (ref "C91") (pin "1") (pinfunction "1_1") (pintype "passive"))
      (node (ref "C92") (pin "1") (pinfunction "1_1") (pintype "passive"))
      (node (ref "C93") (pin "1") (pinfunction "1_1") (pintype "passive"))
      (node (ref "C94") (pin "1") (pinfunction "1_1") (pintype "passive"))
      (node (ref "C95") (pin "1") (pinfunction "1_1") (pintype "passive"))
      (node (ref "C98") (pin "2") (pinfunction "2_2") (pintype "passive"))
      (node (ref "D10") (pin "1") (pinfunction "A1_1") (pintype "passive"))
      (node (ref "D11") (pin "1") (pinfunction "A1_1") (pintype "passive"))
      (node (ref "D12") (pin "1") (pinfunction "A1_1") (pintype "passive"))
      (node (ref "D13") (pin "1") (pinfunction "A1_1") (pintype "passive"))
      (node (ref "D14") (pin "1") (pinfunction "A1_1") (pintype "passive"))
      (node (ref "D5") (pin "1") (pinfunction "A1_1") (pintype "passive"))
      (node (ref "D6") (pin "1") (pinfunction "A1_1") (pintype "passive"))
      (node (ref "D7") (pin "1") (pinfunction "A1_1") (pintype "passive"))
      (node (ref "D8") (pin "1") (pinfunction "A1_1") (pintype "passive"))
      (node (ref "D9") (pin "1") (pinfunction "A1_1") (pintype "passive"))
      (node (ref "GND") (pin "1") (pinfunction "P$1_1") (pintype "bidirectional"))
      (node (ref "IC10") (pin "11") (pinfunction "GND_11") (pintype "power_in"))
      (node (ref "IC10") (pin "12") (pinfunction "GND_12") (pintype "power_in"))
      (node (ref "IC10") (pin "16") (pinfunction "DVDD-EN_16") (pintype "power_in"))
      (node (ref "IC10") (pin "4") (pinfunction "GND_4") (pintype "power_in"))
      (node (ref "IC11") (pin "11") (pinfunction "GND_11") (pintype "power_in"))
      (node (ref "IC11") (pin "12") (pinfunction "GND_12") (pintype "power_in"))
      (node (ref "IC11") (pin "16") (pinfunction "DVDD-EN_16") (pintype "power_in"))
      (node (ref "IC11") (pin "4") (pinfunction "GND_4") (pintype "power_in"))
      (node (ref "IC12") (pin "2") (pinfunction "V-_2") (pintype "power_in"))
      (node (ref "IC13") (pin "3") (pinfunction "GND_3") (pintype "power_in"))
      (node (ref "IC13") (pin "4") (pinfunction "~{LDAC}_4") (pintype "input"))
      (node (ref "IC19") (pin "7") (pinfunction "V-_7") (pintype "power_in"))
      (node (ref "IC2") (pin "15") (pinfunction "GND2_15") (pintype "passive"))
      (node (ref "IC2") (pin "9") (pinfunction "GND2_2_9") (pintype "passive"))
      (node (ref "IC20") (pin "3") (pinfunction "A_3") (pintype "passive"))
      (node (ref "IC21") (pin "4") (pinfunction "GND_4") (pintype "passive"))
      (node (ref "IC22") (pin "4") (pinfunction "GND_4") (pintype "passive"))
      (node (ref "IC23") (pin "4") (pinfunction "GND_4") (pintype "passive"))
      (node (ref "IC24") (pin "4") (pinfunction "GND_4") (pintype "passive"))
      (node (ref "IC25") (pin "4") (pinfunction "GND_4") (pintype "passive"))
      (node (ref "IC26") (pin "4") (pinfunction "GND_4") (pintype "passive"))
      (node (ref "IC27") (pin "4") (pinfunction "GND_4") (pintype "passive"))
      (node (ref "IC28") (pin "4") (pinfunction "GND_4") (pintype "passive"))
      (node (ref "IC29") (pin "4") (pinfunction "GND_4") (pintype "passive"))
      (node (ref "IC3") (pin "15") (pinfunction "GND2_15") (pintype "passive"))
      (node (ref "IC3") (pin "9") (pinfunction "GND2_2_9") (pintype "passive"))
      (node (ref "IC30") (pin "4") (pinfunction "GND_4") (pintype "passive"))
      (node (ref "IC31") (pin "4") (pinfunction "GND_4") (pintype "passive"))
      (node (ref "IC32") (pin "4") (pinfunction "GND_4") (pintype "passive"))
      (node (ref "IC33") (pin "4") (pinfunction "GND_4") (pintype "passive"))
      (node (ref "IC34") (pin "4") (pinfunction "GND_4") (pintype "passive"))
      (node (ref "IC35") (pin "2") (pinfunction "V-_2") (pintype "power_in"))
      (node (ref "IC36") (pin "11") (pinfunction "AUX_GND_11") (pintype "power_in"))
      (node (ref "IC36") (pin "28") (pinfunction "AGND_28") (pintype "power_in"))
      (node (ref "IC36") (pin "29") (pinfunction "AGND_29") (pintype "power_in"))
      (node (ref "IC36") (pin "3") (pinfunction "DAISY_3") (pintype "input"))
      (node (ref "IC36") (pin "31") (pinfunction "AGND_31") (pintype "power_in"))
      (node (ref "IC36") (pin "32") (pinfunction "AGND_32") (pintype "power_in"))
      (node (ref "IC36") (pin "33") (pinfunction "DGND_33") (pintype "power_in"))
      (node (ref "IC36") (pin "4") (pinfunction "~{REFSEL}_4") (pintype "input"))
      (node (ref "IC36") (pin "6") (pinfunction "REFGND_6") (pintype "power_in"))
      (node (ref "IC36") (pin "8") (pinfunction "AGND_8") (pintype "power_in"))
      (node (ref "IC4") (pin "2") (pinfunction "GND_2") (pintype "passive"))
      (node (ref "IC4") (pin "3") (pinfunction "GND_3") (pintype "passive"))
      (node (ref "IC4") (pin "6") (pinfunction "GND_6") (pintype "passive"))
      (node (ref "IC4") (pin "7") (pinfunction "GND_7") (pintype "passive"))
      (node (ref "IC5") (pin "2") (pinfunction "GND_2") (pintype "passive"))
      (node (ref "IC6") (pin "2") (pinfunction "GND_2") (pintype "passive"))
      (node (ref "IC7") (pin "5") (pinfunction "GND_5") (pintype "passive"))
      (node (ref "IC8") (pin "107") (pinfunction "VSS_8_107") (pintype "power_in"))
      (node (ref "IC8") (pin "120") (pinfunction "VSS_9_120") (pintype "power_in"))
      (node (ref "IC8") (pin "130") (pinfunction "VSS_130") (pintype "power_in"))
      (node (ref "IC8") (pin "16") (pinfunction "VSS_2_16") (pintype "bidirectional"))
      (node (ref "IC8") (pin "31") (pinfunction "VSSA_31") (pintype "power_in"))
      (node (ref "IC8") (pin "38") (pinfunction "VSS_3_38") (pintype "power_in"))
      (node (ref "IC8") (pin "48") (pinfunction "PB2-BOOT1_48") (pintype "bidirectional"))
      (node (ref "IC8") (pin "51") (pinfunction "VSS_4_51") (pintype "power_in"))
      (node (ref "IC8") (pin "61") (pinfunction "VSS_5_61") (pintype "power_in"))
      (node (ref "IC8") (pin "83") (pinfunction "VSS_6_83") (pintype "power_in"))
      (node (ref "IC8") (pin "94") (pinfunction "VSS_7_94") (pintype "power_in"))
      (node (ref "J2") (pin "6") (pinfunction "VSS_6") (pintype "power_in"))
      (node (ref "J2") (pin "S") (pinfunction "SH_S") (pintype "passive"))
      (node (ref "J2") (pin "S1") (pinfunction "SH_S1") (pintype "passive"))
      (node (ref "J2") (pin "S2") (pinfunction "SH_S2") (pintype "passive"))
      (node (ref "J2") (pin "SW2") (pinfunction "SW2_SW2") (pintype "passive"))
      (node (ref "L2") (pin "3") (pinfunction "3_3") (pintype "passive"))
      (node (ref "L3") (pin "2") (pinfunction "2_2") (pintype "passive"))
      (node (ref "Q1") (pin "1") (pinfunction "S_1") (pintype "passive"))
      (node (ref "Q1") (pin "4") (pinfunction "S_4") (pintype "passive"))
      (node (ref "Q2") (pin "1") (pinfunction "S_1") (pintype "passive"))
      (node (ref "Q2") (pin "4") (pinfunction "S_4") (pintype "passive"))
      (node (ref "Q3") (pin "1") (pinfunction "S_1") (pintype "passive"))
      (node (ref "Q3") (pin "4") (pinfunction "S_4") (pintype "passive"))
      (node (ref "Q4") (pin "1") (pinfunction "S_1") (pintype "passive"))
      (node (ref "Q4") (pin "4") (pinfunction "S_4") (pintype "passive"))
      (node (ref "Q5") (pin "1") (pinfunction "S_1") (pintype "passive"))
      (node (ref "Q5") (pin "4") (pinfunction "S_4") (pintype "passive"))
      (node (ref "R10") (pin "1") (pinfunction "1_1") (pintype "passive"))
      (node (ref "R14") (pin "1") (pinfunction "1_1") (pintype "passive"))
      (node (ref "R22") (pin "2") (pinfunction "2_2") (pintype "passive"))
      (node (ref "R23") (pin "2") (pinfunction "2_2") (pintype "passive"))
      (node (ref "R29") (pin "2") (pinfunction "2_2") (pintype "passive"))
      (node (ref "R35") (pin "2") (pinfunction "2_2") (pintype "passive"))
      (node (ref "R44") (pin "1") (pinfunction "1_1") (pintype "passive"))
      (node (ref "R45") (pin "1") (pinfunction "1_1") (pintype "passive"))
      (node (ref "R46") (pin "1") (pinfunction "1_1") (pintype "passive"))
      (node (ref "R47") (pin "1") (pinfunction "1_1") (pintype "passive"))
      (node (ref "R48") (pin "1") (pinfunction "1_1") (pintype "passive"))
      (node (ref "R49") (pin "1") (pinfunction "1_1") (pintype "passive"))
      (node (ref "R50") (pin "1") (pinfunction "1_1") (pintype "passive"))
      (node (ref "R51") (pin "1") (pinfunction "1_1") (pintype "passive"))
      (node (ref "R7") (pin "1") (pinfunction "1_1") (pintype "passive"))
      (node (ref "R81") (pin "2") (pinfunction "2_2") (pintype "passive"))
      (node (ref "SH2") (pin "1") (pinfunction "GND_A_1") (pintype "bidirectional"))
      (node (ref "SH3") (pin "1") (pinfunction "GND_A_1") (pintype "bidirectional"))
      (node (ref "SH4") (pin "1") (pinfunction "GND_A_1") (pintype "bidirectional"))
      (node (ref "SH5") (pin "1") (pinfunction "GND_A_1") (pintype "bidirectional"))
      (node (ref "SH6") (pin "1") (pinfunction "GND_A_1") (pintype "bidirectional"))
      (node (ref "SH7") (pin "1") (pinfunction "GND_A_1") (pintype "bidirectional"))
      (node (ref "SH8") (pin "1") (pinfunction "GND_A_1") (pintype "bidirectional"))
      (node (ref "TVS3") (pin "C1") (pinfunction "1_C1") (pintype "passive"))
      (node (ref "TVS4") (pin "C1") (pinfunction "1_C1") (pintype "passive"))
      (node (ref "X2") (pin "3") (pinfunction "1_3") (pintype "passive"))
      (node (ref "X3") (pin "1") (pinfunction "1_1") (pintype "passive"))
      (node (ref "X3") (pin "8") (pinfunction "1_8") (pintype "passive"))
      (node (ref "X4") (pin "2") (pinfunction "1_2") (pintype "passive"))
      (node (ref "X4") (pin "4") (pinfunction "1_4") (pintype "passive"))
      (node (ref "X4") (pin "6") (pinfunction "1_6") (pintype "passive"))
      (node (ref "X4") (pin "8") (pinfunction "1_8") (pintype "passive"))
    )
    (net (code "79") (name "GNDIO") (class "Default")
      (node (ref "C1") (pin "1") (pinfunction "1_1") (pintype "passive"))
      (node (ref "C2") (pin "2") (pinfunction "2_2") (pintype "passive"))
      (node (ref "C4") (pin "2") (pinfunction "2_2") (pintype "passive"))
      (node (ref "C7") (pin "1") (pinfunction "1_1") (pintype "passive"))
      (node (ref "IC1") (pin "4") (pinfunction "GND_4") (pintype "passive"))
      (node (ref "IC1") (pin "7") (pinfunction "WP_7") (pintype "input"))
      (node (ref "IC2") (pin "2") (pinfunction "GND1_2_2") (pintype "passive"))
      (node (ref "IC2") (pin "8") (pinfunction "GND1_8") (pintype "passive"))
      (node (ref "IC3") (pin "2") (pinfunction "GND1_2_2") (pintype "passive"))
      (node (ref "IC3") (pin "8") (pinfunction "GND1_8") (pintype "passive"))
      (node (ref "L1") (pin "1") (pinfunction "1_1") (pintype "passive"))
      (node (ref "X1") (pin "11") (pinfunction "1_11") (pintype "passive"))
      (node (ref "X1") (pin "16") (pinfunction "1_16") (pintype "passive"))
      (node (ref "X1") (pin "20") (pinfunction "1_20") (pintype "passive"))
      (node (ref "X1") (pin "25") (pinfunction "1_25") (pintype "passive"))
      (node (ref "X1") (pin "7") (pinfunction "1_7") (pintype "passive"))
    )
    (net (code "80") (name "IN_CTRL0") (class "Default")
      (node (ref "IC8") (pin "123") (pinfunction "PD7_123") (pintype "bidirectional"))
      (node (ref "Q2") (pin "2") (pinfunction "G_2") (pintype "passive"))
    )
    (net (code "81") (name "IN_CTRL1") (class "Default")
      (node (ref "IC8") (pin "124") (pinfunction "PG9_124") (pintype "bidirectional"))
      (node (ref "Q2") (pin "5") (pinfunction "G_5") (pintype "passive"))
    )
    (net (code "82") (name "IN_CTRL2") (class "Default")
      (node (ref "IC8") (pin "125") (pinfunction "PG10_125") (pintype "bidirectional"))
      (node (ref "Q3") (pin "2") (pinfunction "G_2") (pintype "passive"))
    )
    (net (code "83") (name "IN_CTRL3") (class "Default")
      (node (ref "IC8") (pin "126") (pinfunction "PG11_126") (pintype "bidirectional"))
      (node (ref "Q3") (pin "5") (pinfunction "G_5") (pintype "passive"))
    )
    (net (code "84") (name "IN_CTRL4") (class "Default")
      (node (ref "IC8") (pin "127") (pinfunction "PG12_127") (pintype "bidirectional"))
      (node (ref "Q4") (pin "2") (pinfunction "G_2") (pintype "passive"))
    )
    (net (code "85") (name "IN_CTRL5") (class "Default")
      (node (ref "IC8") (pin "128") (pinfunction "PG13_128") (pintype "bidirectional"))
      (node (ref "Q4") (pin "5") (pinfunction "G_5") (pintype "passive"))
    )
    (net (code "86") (name "IN_CTRL6") (class "Default")
      (node (ref "IC8") (pin "129") (pinfunction "PG14_129") (pintype "bidirectional"))
      (node (ref "Q5") (pin "2") (pinfunction "G_2") (pintype "passive"))
    )
    (net (code "87") (name "IN_CTRL7") (class "Default")
      (node (ref "IC8") (pin "133") (pinfunction "PB3_133") (pintype "bidirectional"))
      (node (ref "Q5") (pin "5") (pinfunction "G_5") (pintype "passive"))
    )
    (net (code "88") (name "IRQ") (class "Default")
      (node (ref "IC3") (pin "11") (pinfunction "B4_11") (pintype "input"))
      (node (ref "IC8") (pin "69") (pinfunction "PB10_69") (pintype "bidirectional"))
    )
    (net (code "89") (name "MISO") (class "Default")
      (node (ref "IC8") (pin "66") (pinfunction "PE13_66") (pintype "bidirectional"))
      (node (ref "RN1") (pin "6") (pinfunction "2_6") (pintype "passive"))
    )
    (net (code "90") (name "MOSI") (class "Default")
      (node (ref "IC8") (pin "67") (pinfunction "PE14_67") (pintype "bidirectional"))
      (node (ref "RN1") (pin "5") (pinfunction "2_5") (pintype "passive"))
    )
    (net (code "91") (name "NSS") (class "Default")
      (node (ref "IC8") (pin "64") (pinfunction "PE11_64") (pintype "bidirectional"))
      (node (ref "RN1") (pin "8") (pinfunction "2_8") (pintype "passive"))
    )
    (net (code "92") (name "Net-(D1-C1A2)") (class "Default")
      (node (ref "C42") (pin "1") (pinfunction "1_1") (pintype "passive"))
      (node (ref "D1") (pin "3") (pinfunction "C1A2_3") (pintype "passive"))
      (node (ref "FB2") (pin "P$2") (pinfunction "2_P$2") (pintype "passive"))
      (node (ref "TVS1") (pin "C2") (pinfunction "2_C2") (pintype "passive"))
      (node (ref "X3") (pin "2") (pinfunction "1_2") (pintype "passive"))
    )
    (net (code "93") (name "Net-(D2-C1A2)") (class "Default")
      (node (ref "C51") (pin "1") (pinfunction "1_1") (pintype "passive"))
      (node (ref "D2") (pin "3") (pinfunction "C1A2_3") (pintype "passive"))
      (node (ref "FB3") (pin "P$2") (pinfunction "2_P$2") (pintype "passive"))
      (node (ref "TVS2") (pin "C2") (pinfunction "2_C2") (pintype "passive"))
      (node (ref "X3") (pin "3") (pinfunction "1_3") (pintype "passive"))
    )
    (net (code "94") (name "Net-(D3-C1A2)") (class "Default")
      (node (ref "C62") (pin "1") (pinfunction "1_1") (pintype "passive"))
      (node (ref "D3") (pin "3") (pinfunction "C1A2_3") (pintype "passive"))
      (node (ref "R17") (pin "1") (pinfunction "1_1") (pintype "passive"))
      (node (ref "R20") (pin "2") (pinfunction "2_2") (pintype "passive"))
      (node (ref "X3") (pin "4") (pinfunction "1_4") (pintype "passive"))
    )
    (net (code "95") (name "Net-(D4-C1A2)") (class "Default")
      (node (ref "C68") (pin "1") (pinfunction "1_1") (pintype "passive"))
      (node (ref "D4") (pin "3") (pinfunction "C1A2_3") (pintype "passive"))
      (node (ref "R25") (pin "1") (pinfunction "1_1") (pintype "passive"))
      (node (ref "R27") (pin "2") (pinfunction "2_2") (pintype "passive"))
      (node (ref "X3") (pin "5") (pinfunction "1_5") (pintype "passive"))
    )
    (net (code "96") (name "Net-(D5-C1A2)") (class "Default")
      (node (ref "D5") (pin "3") (pinfunction "C1A2_3") (pintype "passive"))
      (node (ref "IC19") (pin "3") (pinfunction "O_3") (pintype "output"))
      (node (ref "IC19") (pin "6") (pinfunction "O_6") (pintype "output"))
      (node (ref "R31") (pin "2") (pinfunction "2_2") (pintype "passive"))
    )
    (net (code "97") (name "Net-(D6-C1A2)") (class "Default")
      (node (ref "D6") (pin "3") (pinfunction "C1A2_3") (pintype "passive"))
      (node (ref "IC19") (pin "11") (pinfunction "O_11") (pintype "output"))
      (node (ref "IC19") (pin "8") (pinfunction "O_8") (pintype "output"))
      (node (ref "R32") (pin "2") (pinfunction "2_2") (pintype "passive"))
    )
    (net (code "98") (name "Net-(FB1-1)") (class "Default")
      (node (ref "C24") (pin "2") (pinfunction "2_2") (pintype "passive"))
      (node (ref "C25") (pin "+") (pinfunction "+_+") (pintype "passive"))
      (node (ref "C26") (pin "1") (pinfunction "1_1") (pintype "passive"))
      (node (ref "C27") (pin "1") (pinfunction "1_1") (pintype "passive"))
      (node (ref "C28") (pin "1") (pinfunction "1_1") (pintype "passive"))
      (node (ref "C29") (pin "1") (pinfunction "1_1") (pintype "passive"))
      (node (ref "C30") (pin "1") (pinfunction "1_1") (pintype "passive"))
      (node (ref "C31") (pin "1") (pinfunction "1_1") (pintype "passive"))
      (node (ref "C32") (pin "1") (pinfunction "1_1") (pintype "passive"))
      (node (ref "C33") (pin "1") (pinfunction "1_1") (pintype "passive"))
      (node (ref "C34") (pin "1") (pinfunction "1_1") (pintype "passive"))
      (node (ref "C35") (pin "1") (pinfunction "1_1") (pintype "passive"))
      (node (ref "C36") (pin "1") (pinfunction "1_1") (pintype "passive"))
      (node (ref "FB1") (pin "P$1") (pinfunction "1_P$1") (pintype "passive"))
      (node (ref "IC8") (pin "108") (pinfunction "VDD_9_108") (pintype "power_in"))
      (node (ref "IC8") (pin "121") (pinfunction "VDD_10_121") (pintype "power_in"))
      (node (ref "IC8") (pin "131") (pinfunction "VDD_11_131") (pintype "power_in"))
      (node (ref "IC8") (pin "143") (pinfunction "PDR_ON_143") (pintype "input"))
      (node (ref "IC8") (pin "144") (pinfunction "VDD_144") (pintype "power_in"))
      (node (ref "IC8") (pin "17") (pinfunction "VDD_2_17") (pintype "bidirectional"))
      (node (ref "IC8") (pin "30") (pinfunction "VDD_3_30") (pintype "power_in"))
      (node (ref "IC8") (pin "39") (pinfunction "VDD_4_39") (pintype "power_in"))
      (node (ref "IC8") (pin "52") (pinfunction "VDD_5_52") (pintype "power_in"))
      (node (ref "IC8") (pin "6") (pinfunction "VBAT_6") (pintype "power_in"))
      (node (ref "IC8") (pin "62") (pinfunction "VDD_6_62") (pintype "power_in"))
      (node (ref "IC8") (pin "72") (pinfunction "VDD_7_72") (pintype "power_in"))
      (node (ref "IC8") (pin "84") (pinfunction "VDD_8_84") (pintype "power_in"))
      (node (ref "IC8") (pin "95") (pinfunction "VDDUSB_95") (pintype "power_in"))
      (node (ref "R6") (pin "1") (pinfunction "1_1") (pintype "passive"))
      (node (ref "SH1") (pin "1") (pinfunction "GND_A_1") (pintype "bidirectional"))
    )
    (net (code "99") (name "Net-(FB1-2)") (class "Default")
      (node (ref "C37") (pin "1") (pinfunction "1_1") (pintype "passive"))
      (node (ref "C38") (pin "1") (pinfunction "1_1") (pintype "passive"))
      (node (ref "FB1") (pin "P$2") (pinfunction "2_P$2") (pintype "passive"))
      (node (ref "IC8") (pin "33") (pinfunction "VDDA_33") (pintype "power_in"))
      (node (ref "R8") (pin "1") (pinfunction "1_1") (pintype "passive"))
    )
    (net (code "100") (name "Net-(FB2-1)") (class "Default")
      (node (ref "FB2") (pin "P$1") (pinfunction "1_P$1") (pintype "passive"))
      (node (ref "IC9") (pin "3") (pinfunction "+IN_3") (pintype "input"))
      (node (ref "R11") (pin "1") (pinfunction "1_1") (pintype "passive"))
      (node (ref "R9") (pin "1") (pinfunction "1_1") (pintype "passive"))
    )
    (net (code "101") (name "Net-(FB3-1)") (class "Default")
      (node (ref "FB3") (pin "P$1") (pinfunction "1_P$1") (pintype "passive"))
      (node (ref "IC9") (pin "5") (pinfunction "+IN_5") (pintype "input"))
      (node (ref "R13") (pin "1") (pinfunction "1_1") (pintype "passive"))
      (node (ref "R15") (pin "1") (pinfunction "1_1") (pintype "passive"))
    )
    (net (code "102") (name "Net-(FB4-1)") (class "Default")
      (node (ref "C65") (pin "1") (pinfunction "1_1") (pintype "passive"))
      (node (ref "C66") (pin "2") (pinfunction "2_2") (pintype "passive"))
      (node (ref "C67") (pin "1") (pinfunction "1_1") (pintype "passive"))
      (node (ref "FB4") (pin "P$1") (pinfunction "1_P$1") (pintype "passive"))
      (node (ref "IC12") (pin "5") (pinfunction "V+_5") (pintype "power_in"))
      (node (ref "IC13") (pin "9") (pinfunction "VDD_9") (pintype "power_in"))
    )
    (net (code "103") (name "Net-(FB5-1)") (class "Default")
      (node (ref "FB5") (pin "P$1") (pinfunction "1_P$1") (pintype "passive"))
      (node (ref "X4") (pin "1") (pinfunction "1_1") (pintype "passive"))
    )
    (net (code "104") (name "Net-(FB5-2)") (class "Default")
      (node (ref "FB5") (pin "P$2") (pinfunction "2_P$2") (pintype "passive"))
      (node (ref "Q6") (pin "3") (pinfunction "D_3") (pintype "passive"))
      (node (ref "R60") (pin "2") (pinfunction "2_2") (pintype "passive"))
      (node (ref "TVS5") (pin "C2") (pinfunction "2_C2") (pintype "passive"))
    )
    (net (code "105") (name "Net-(FB6-1)") (class "Default")
      (node (ref "FB6") (pin "P$1") (pinfunction "1_P$1") (pintype "passive"))
      (node (ref "X4") (pin "3") (pinfunction "1_3") (pintype "passive"))
    )
    (net (code "106") (name "Net-(FB6-2)") (class "Default")
      (node (ref "FB6") (pin "P$2") (pinfunction "2_P$2") (pintype "passive"))
      (node (ref "Q8") (pin "3") (pinfunction "D_3") (pintype "passive"))
      (node (ref "R61") (pin "2") (pinfunction "2_2") (pintype "passive"))
      (node (ref "TVS6") (pin "C2") (pinfunction "2_C2") (pintype "passive"))
    )
    (net (code "107") (name "Net-(FB7-1)") (class "Default")
      (node (ref "FB7") (pin "P$1") (pinfunction "1_P$1") (pintype "passive"))
      (node (ref "X4") (pin "5") (pinfunction "1_5") (pintype "passive"))
    )
    (net (code "108") (name "Net-(FB7-2)") (class "Default")
      (node (ref "FB7") (pin "P$2") (pinfunction "2_P$2") (pintype "passive"))
      (node (ref "JP4") (pin "1") (pinfunction "1_1") (pintype "passive"))
      (node (ref "Q10") (pin "3") (pinfunction "D_3") (pintype "passive"))
      (node (ref "TVS7") (pin "C2") (pinfunction "2_C2") (pintype "passive"))
    )
    (net (code "109") (name "Net-(FB9-1)") (class "Default")
      (node (ref "FB9") (pin "P$1") (pinfunction "1_P$1") (pintype "passive"))
      (node (ref "X4") (pin "7") (pinfunction "1_7") (pintype "passive"))
    )
    (net (code "110") (name "Net-(FB9-2)") (class "Default")
      (node (ref "FB9") (pin "P$2") (pinfunction "2_P$2") (pintype "passive"))
      (node (ref "JP5") (pin "1") (pinfunction "1_1") (pintype "passive"))
      (node (ref "Q12") (pin "3") (pinfunction "D_3") (pintype "passive"))
      (node (ref "TVS8") (pin "C2") (pinfunction "2_C2") (pintype "passive"))
    )
    (net (code "111") (name "Net-(IC2-B1)") (class "Default")
      (node (ref "IC2") (pin "14") (pinfunction "B1_14") (pintype "output"))
      (node (ref "RN1") (pin "4") (pinfunction "1_4") (pintype "passive"))
    )
    (net (code "112") (name "Net-(IC2-B2)") (class "Default")
      (node (ref "IC2") (pin "13") (pinfunction "B2_13") (pintype "output"))
      (node (ref "RN1") (pin "2") (pinfunction "1_2") (pintype "passive"))
    )
    (net (code "113") (name "Net-(IC2-B3)") (class "Default")
      (node (ref "IC2") (pin "12") (pinfunction "B3_12") (pintype "output"))
      (node (ref "RN1") (pin "1") (pinfunction "1_1") (pintype "passive"))
    )
    (net (code "114") (name "Net-(IC2-B4)") (class "Default")
      (node (ref "IC2") (pin "11") (pinfunction "B4_11") (pintype "input"))
      (node (ref "RN1") (pin "3") (pinfunction "1_3") (pintype "passive"))
    )
    (net (code "115") (name "Net-(IC3-A4)") (class "Default")
      (node (ref "DIB1.1") (pin "COM") (pinfunction "COM_COM") (pintype "passive"))
      (node (ref "IC3") (pin "6") (pinfunction "A4_6") (pintype "output"))
    )
    (net (code "116") (name "Net-(IC5-BYPASS)") (class "Default")
      (node (ref "C17") (pin "2") (pinfunction "2_2") (pintype "passive"))
      (node (ref "IC5") (pin "4") (pinfunction "BYPASS_4") (pintype "passive"))
    )
    (net (code "117") (name "Net-(IC6-BYPASS)") (class "Default")
      (node (ref "C19") (pin "2") (pinfunction "2_2") (pintype "passive"))
      (node (ref "IC6") (pin "4") (pinfunction "BYPASS_4") (pintype "passive"))
    )
    (net (code "118") (name "Net-(IC8A-PA4)") (class "Default")
      (node (ref "IC8") (pin "40") (pinfunction "PA4_40") (pintype "bidirectional"))
      (node (ref "RN4") (pin "8") (pinfunction "2_8") (pintype "passive"))
    )
    (net (code "119") (name "Net-(IC8A-PA5)") (class "Default")
      (node (ref "IC8") (pin "41") (pinfunction "PA5_41") (pintype "bidirectional"))
      (node (ref "RN4") (pin "7") (pinfunction "2_7") (pintype "passive"))
    )
    (net (code "120") (name "Net-(IC8A-PA6)") (class "Default")
      (node (ref "IC8") (pin "42") (pinfunction "PA6_42") (pintype "bidirectional"))
      (node (ref "RN4") (pin "6") (pinfunction "2_6") (pintype "passive"))
    )
    (net (code "121") (name "Net-(IC8A-PA7)") (class "Default")
      (node (ref "IC8") (pin "43") (pinfunction "PA7_43") (pintype "bidirectional"))
      (node (ref "RN4") (pin "5") (pinfunction "2_5") (pintype "passive"))
    )
    (net (code "122") (name "Net-(IC8A-PB12)") (class "Default")
      (node (ref "IC8") (pin "73") (pinfunction "PB12_73") (pintype "bidirectional"))
      (node (ref "RN5") (pin "8") (pinfunction "2_8") (pintype "passive"))
    )
    (net (code "123") (name "Net-(IC8A-PB13)") (class "Default")
      (node (ref "IC8") (pin "74") (pinfunction "PB13_74") (pintype "bidirectional"))
      (node (ref "RN5") (pin "7") (pinfunction "2_7") (pintype "passive"))
    )
    (net (code "124") (name "Net-(IC8A-PB14)") (class "Default")
      (node (ref "IC8") (pin "75") (pinfunction "PB14_75") (pintype "bidirectional"))
      (node (ref "RN5") (pin "6") (pinfunction "2_6") (pintype "passive"))
    )
    (net (code "125") (name "Net-(IC8A-PB15)") (class "Default")
      (node (ref "IC8") (pin "76") (pinfunction "PB15_76") (pintype "bidirectional"))
      (node (ref "RN5") (pin "5") (pinfunction "2_5") (pintype "passive"))
    )
    (net (code "126") (name "Net-(IC8B-PH0-OSC_IN)") (class "Default")
      (node (ref "C22") (pin "2") (pinfunction "2_2") (pintype "passive"))
      (node (ref "IC8") (pin "23") (pinfunction "PH0-OSC_IN_23") (pintype "bidirectional"))
      (node (ref "Y1") (pin "2") (pinfunction "2_2") (pintype "passive"))
    )
    (net (code "127") (name "Net-(IC8B-PH1-OSC_OUT)") (class "Default")
      (node (ref "C23") (pin "2") (pinfunction "2_2") (pintype "passive"))
      (node (ref "IC8") (pin "24") (pinfunction "PH1-OSC_OUT_24") (pintype "bidirectional"))
      (node (ref "Y1") (pin "1") (pinfunction "1_1") (pintype "passive"))
    )
    (net (code "128") (name "Net-(IC8C-VCAP_1)") (class "Default")
      (node (ref "C40") (pin "2") (pinfunction "2_2") (pintype "passive"))
      (node (ref "IC8") (pin "71") (pinfunction "VCAP_1_71") (pintype "power_in"))
    )
    (net (code "129") (name "Net-(IC8C-VCAP_2)") (class "Default")
      (node (ref "C39") (pin "2") (pinfunction "2_2") (pintype "passive"))
      (node (ref "IC8") (pin "106") (pinfunction "VCAP_2_106") (pintype "power_in"))
    )
    (net (code "130") (name "Net-(IC8C-VREF+)") (class "Default")
      (node (ref "IC8") (pin "32") (pinfunction "VREF+_32") (pintype "power_in"))
      (node (ref "R8") (pin "2") (pinfunction "2_2") (pintype "passive"))
    )
    (net (code "131") (name "Net-(IC10-+VSENSE)") (class "Default")
      (node (ref "IC10") (pin "22") (pinfunction "+VSENSE_22") (pintype "input"))
      (node (ref "IC9") (pin "1") (pinfunction "OUT_1") (pintype "output"))
      (node (ref "IC9") (pin "2") (pinfunction "-IN_2") (pintype "input"))
    )
    (net (code "132") (name "Net-(IC10--VSENSE)") (class "Default")
      (node (ref "C42") (pin "2") (pinfunction "2_2") (pintype "passive"))
      (node (ref "IC10") (pin "23") (pinfunction "-VSENSE_23") (pintype "input"))
      (node (ref "SH2") (pin "2") (pinfunction "GND_B_2") (pintype "bidirectional"))
      (node (ref "TVS1") (pin "C1") (pinfunction "1_C1") (pintype "passive"))
    )
    (net (code "133") (name "Net-(IC10-CMP)") (class "Default")
      (node (ref "C41") (pin "2") (pinfunction "2_2") (pintype "passive"))
      (node (ref "IC10") (pin "17") (pinfunction "CMP_17") (pintype "output"))
    )
    (net (code "134") (name "Net-(IC10-HART-IN)") (class "Default")
      (node (ref "C44") (pin "2") (pinfunction "2_2") (pintype "passive"))
      (node (ref "IC10") (pin "18") (pinfunction "HART-IN_18") (pintype "input"))
    )
    (net (code "135") (name "Net-(IC10-IOUT)") (class "Default")
      (node (ref "IC10") (pin "19") (pinfunction "IOUT_19") (pintype "output"))
      (node (ref "R9") (pin "2") (pinfunction "2_2") (pintype "passive"))
    )
    (net (code "136") (name "Net-(IC10-ISET-R)") (class "Default")
      (node (ref "IC10") (pin "13") (pinfunction "ISET-R_13") (pintype "input"))
      (node (ref "R10") (pin "2") (pinfunction "2_2") (pintype "passive"))
    )
    (net (code "137") (name "Net-(IC10-REFIN)") (class "Default")
      (node (ref "C45") (pin "1") (pinfunction "1_1") (pintype "passive"))
      (node (ref "IC10") (pin "14") (pinfunction "REFOUT_14") (pintype "output"))
      (node (ref "IC10") (pin "15") (pinfunction "REFIN_15") (pintype "input"))
    )
    (net (code "138") (name "Net-(IC10-VOUT)") (class "Default")
      (node (ref "C41") (pin "1") (pinfunction "1_1") (pintype "passive"))
      (node (ref "IC10") (pin "21") (pinfunction "VOUT_21") (pintype "output"))
      (node (ref "R11") (pin "2") (pinfunction "2_2") (pintype "passive"))
    )
    (net (code "139") (name "Net-(IC11-+VSENSE)") (class "Default")
      (node (ref "IC11") (pin "22") (pinfunction "+VSENSE_22") (pintype "input"))
      (node (ref "IC9") (pin "6") (pinfunction "-IN_6") (pintype "input"))
      (node (ref "IC9") (pin "7") (pinfunction "OUT_7") (pintype "output"))
    )
    (net (code "140") (name "Net-(IC11--VSENSE)") (class "Default")
      (node (ref "C51") (pin "2") (pinfunction "2_2") (pintype "passive"))
      (node (ref "IC11") (pin "23") (pinfunction "-VSENSE_23") (pintype "input"))
      (node (ref "SH3") (pin "2") (pinfunction "GND_B_2") (pintype "bidirectional"))
      (node (ref "TVS2") (pin "C1") (pinfunction "1_C1") (pintype "passive"))
    )
    (net (code "141") (name "Net-(IC11-CMP)") (class "Default")
      (node (ref "C50") (pin "2") (pinfunction "2_2") (pintype "passive"))
      (node (ref "IC11") (pin "17") (pinfunction "CMP_17") (pintype "output"))
    )
    (net (code "142") (name "Net-(IC11-HART-IN)") (class "Default")
      (node (ref "C53") (pin "2") (pinfunction "2_2") (pintype "passive"))
      (node (ref "IC11") (pin "18") (pinfunction "HART-IN_18") (pintype "input"))
    )
    (net (code "143") (name "Net-(IC11-IOUT)") (class "Default")
      (node (ref "IC11") (pin "19") (pinfunction "IOUT_19") (pintype "output"))
      (node (ref "R13") (pin "2") (pinfunction "2_2") (pintype "passive"))
    )
    (net (code "144") (name "Net-(IC11-ISET-R)") (class "Default")
      (node (ref "IC11") (pin "13") (pinfunction "ISET-R_13") (pintype "input"))
      (node (ref "R14") (pin "2") (pinfunction "2_2") (pintype "passive"))
    )
    (net (code "145") (name "Net-(IC11-REFIN)") (class "Default")
      (node (ref "C54") (pin "1") (pinfunction "1_1") (pintype "passive"))
      (node (ref "IC11") (pin "14") (pinfunction "REFOUT_14") (pintype "output"))
      (node (ref "IC11") (pin "15") (pinfunction "REFIN_15") (pintype "input"))
    )
    (net (code "146") (name "Net-(IC11-VOUT)") (class "Default")
      (node (ref "C50") (pin "1") (pinfunction "1_1") (pintype "passive"))
      (node (ref "IC11") (pin "21") (pinfunction "VOUT_21") (pintype "output"))
      (node (ref "R15") (pin "2") (pinfunction "2_2") (pintype "passive"))
    )
    (net (code "147") (name "Net-(IC12A-+IN)") (class "Default")
      (node (ref "IC12") (pin "3") (pinfunction "+IN_3") (pintype "input"))
      (node (ref "R18") (pin "2") (pinfunction "2_2") (pintype "passive"))
      (node (ref "R22") (pin "1") (pinfunction "1_1") (pintype "passive"))
    )
    (net (code "148") (name "Net-(IC13-VOUTA)") (class "Default")
      (node (ref "IC13") (pin "1") (pinfunction "VOUTA_1") (pintype "output"))
      (node (ref "R21") (pin "2") (pinfunction "2_2") (pintype "passive"))
    )
    (net (code "149") (name "Net-(IC13-VOUTB)") (class "Default")
      (node (ref "IC13") (pin "2") (pinfunction "VOUTB_2") (pintype "output"))
      (node (ref "R28") (pin "2") (pinfunction "2_2") (pintype "passive"))
    )
    (net (code "150") (name "Net-(IC13-VREF)") (class "Default")
      (node (ref "C63") (pin "2") (pinfunction "2_2") (pintype "passive"))
      (node (ref "IC13") (pin "10") (pinfunction "VREF_10") (pintype "bidirectional"))
      (node (ref "R18") (pin "1") (pinfunction "1_1") (pintype "passive"))
    )
    (net (code "151") (name "Net-(IC14A-+IN)") (class "Default")
      (node (ref "IC14") (pin "3") (pinfunction "+IN_3") (pintype "input"))
      (node (ref "R28") (pin "1") (pinfunction "1_1") (pintype "passive"))
      (node (ref "R29") (pin "1") (pinfunction "1_1") (pintype "passive"))
    )
    (net (code "152") (name "Net-(IC14A--IN)") (class "Default")
      (node (ref "IC14") (pin "2") (pinfunction "-IN_2") (pintype "input"))
      (node (ref "R24") (pin "1") (pinfunction "1_1") (pintype "passive"))
      (node (ref "R25") (pin "2") (pinfunction "2_2") (pintype "passive"))
    )
    (net (code "153") (name "Net-(IC14A-OUT)") (class "Default")
      (node (ref "IC14") (pin "1") (pinfunction "OUT_1") (pintype "output"))
      (node (ref "R26") (pin "1") (pinfunction "1_1") (pintype "passive"))
    )
    (net (code "154") (name "Net-(IC14B-+IN)") (class "Default")
      (node (ref "IC14") (pin "5") (pinfunction "+IN_5") (pintype "input"))
      (node (ref "R21") (pin "1") (pinfunction "1_1") (pintype "passive"))
      (node (ref "R23") (pin "1") (pinfunction "1_1") (pintype "passive"))
    )
    (net (code "155") (name "Net-(IC14B--IN)") (class "Default")
      (node (ref "IC14") (pin "6") (pinfunction "-IN_6") (pintype "input"))
      (node (ref "R16") (pin "1") (pinfunction "1_1") (pintype "passive"))
      (node (ref "R17") (pin "2") (pinfunction "2_2") (pintype "passive"))
    )
    (net (code "156") (name "Net-(IC14B-OUT)") (class "Default")
      (node (ref "IC14") (pin "7") (pinfunction "OUT_7") (pintype "output"))
      (node (ref "R19") (pin "1") (pinfunction "1_1") (pintype "passive"))
    )
    (net (code "157") (name "Net-(IC15-GND)") (class "Default")
      (node (ref "IC15") (pin "6") (pinfunction "GND_6") (pintype "passive"))
      (node (ref "IC16") (pin "6") (pinfunction "GND_6") (pintype "passive"))
      (node (ref "IC17") (pin "6") (pinfunction "GND_6") (pintype "passive"))
      (node (ref "IC18") (pin "6") (pinfunction "GND_6") (pintype "passive"))
      (node (ref "SH4") (pin "2") (pinfunction "GND_B_2") (pintype "bidirectional"))
    )
    (net (code "158") (name "Net-(IC20-R)") (class "Default")
      (node (ref "IC20") (pin "2") (pinfunction "R_2") (pintype "passive"))
      (node (ref "R34") (pin "2") (pinfunction "2_2") (pintype "passive"))
      (node (ref "R35") (pin "1") (pinfunction "1_1") (pintype "passive"))
    )
    (net (code "159") (name "Net-(IC21B-COM)") (class "Default")
      (node (ref "IC21") (pin "6") (pinfunction "COM_6") (pintype "bidirectional"))
      (node (ref "IC26") (pin "6") (pinfunction "COM_6") (pintype "bidirectional"))
      (node (ref "JP3") (pin "COM") (pinfunction "COM_COM") (pintype "passive"))
    )
    (net (code "160") (name "Net-(IC21B-NO)") (class "Default")
      (node (ref "IC21") (pin "1") (pinfunction "NO_1") (pintype "bidirectional"))
      (node (ref "R60") (pin "1") (pinfunction "1_1") (pintype "passive"))
    )
    (net (code "161") (name "Net-(IC22B-COM)") (class "Default")
      (node (ref "IC22") (pin "6") (pinfunction "COM_6") (pintype "bidirectional"))
      (node (ref "IC31") (pin "6") (pinfunction "COM_6") (pintype "bidirectional"))
      (node (ref "R63") (pin "1") (pinfunction "1_1") (pintype "passive"))
    )
    (net (code "162") (name "Net-(IC22B-NO)") (class "Default")
      (node (ref "IC22") (pin "1") (pinfunction "NO_1") (pintype "bidirectional"))
      (node (ref "IC27") (pin "6") (pinfunction "COM_6") (pintype "bidirectional"))
      (node (ref "R68") (pin "2") (pinfunction "2_2") (pintype "passive"))
    )
    (net (code "163") (name "Net-(IC23B-COM)") (class "Default")
      (node (ref "IC23") (pin "6") (pinfunction "COM_6") (pintype "bidirectional"))
      (node (ref "IC32") (pin "6") (pinfunction "COM_6") (pintype "bidirectional"))
      (node (ref "R71") (pin "1") (pinfunction "1_1") (pintype "passive"))
    )
    (net (code "164") (name "Net-(IC23B-NO)") (class "Default")
      (node (ref "IC23") (pin "1") (pinfunction "NO_1") (pintype "bidirectional"))
      (node (ref "IC28") (pin "6") (pinfunction "COM_6") (pintype "bidirectional"))
      (node (ref "R72") (pin "2") (pinfunction "2_2") (pintype "passive"))
    )
    (net (code "165") (name "Net-(IC24B-COM)") (class "Default")
      (node (ref "IC24") (pin "6") (pinfunction "COM_6") (pintype "bidirectional"))
      (node (ref "IC33") (pin "6") (pinfunction "COM_6") (pintype "bidirectional"))
      (node (ref "JP4") (pin "2") (pinfunction "2_2") (pintype "passive"))
      (node (ref "R75") (pin "1") (pinfunction "1_1") (pintype "passive"))
    )
    (net (code "166") (name "Net-(IC24B-NO)") (class "Default")
      (node (ref "IC24") (pin "1") (pinfunction "NO_1") (pintype "bidirectional"))
      (node (ref "IC29") (pin "6") (pinfunction "COM_6") (pintype "bidirectional"))
      (node (ref "R76") (pin "2") (pinfunction "2_2") (pintype "passive"))
    )
    (net (code "167") (name "Net-(IC25B-COM)") (class "Default")
      (node (ref "IC25") (pin "6") (pinfunction "COM_6") (pintype "bidirectional"))
      (node (ref "IC34") (pin "6") (pinfunction "COM_6") (pintype "bidirectional"))
      (node (ref "JP5") (pin "2") (pinfunction "2_2") (pintype "passive"))
      (node (ref "R79") (pin "1") (pinfunction "1_1") (pintype "passive"))
    )
    (net (code "168") (name "Net-(IC25B-NO)") (class "Default")
      (node (ref "IC25") (pin "1") (pinfunction "NO_1") (pintype "bidirectional"))
      (node (ref "IC30") (pin "6") (pinfunction "COM_6") (pintype "bidirectional"))
      (node (ref "R82") (pin "2") (pinfunction "2_2") (pintype "passive"))
    )
    (net (code "169") (name "Net-(IC26B-NO)") (class "Default")
      (node (ref "IC26") (pin "1") (pinfunction "NO_1") (pintype "bidirectional"))
      (node (ref "R61") (pin "1") (pinfunction "1_1") (pintype "passive"))
    )
    (net (code "170") (name "Net-(IC27B-NO)") (class "Default")
      (node (ref "IC27") (pin "1") (pinfunction "NO_1") (pintype "bidirectional"))
      (node (ref "IC31") (pin "1") (pinfunction "NO_1") (pintype "bidirectional"))
      (node (ref "Q7") (pin "3") (pinfunction "D_3") (pintype "passive"))
    )
    (net (code "171") (name "Net-(IC28B-NO)") (class "Default")
      (node (ref "IC28") (pin "1") (pinfunction "NO_1") (pintype "bidirectional"))
      (node (ref "IC32") (pin "1") (pinfunction "NO_1") (pintype "bidirectional"))
      (node (ref "Q9") (pin "3") (pinfunction "D_3") (pintype "passive"))
    )
    (net (code "172") (name "Net-(IC29B-NO)") (class "Default")
      (node (ref "IC29") (pin "1") (pinfunction "NO_1") (pintype "bidirectional"))
      (node (ref "IC33") (pin "1") (pinfunction "NO_1") (pintype "bidirectional"))
      (node (ref "Q11") (pin "3") (pinfunction "D_3") (pintype "passive"))
    )
    (net (code "173") (name "Net-(IC30B-NO)") (class "Default")
      (node (ref "IC30") (pin "1") (pinfunction "NO_1") (pintype "bidirectional"))
      (node (ref "IC34") (pin "1") (pinfunction "NO_1") (pintype "bidirectional"))
      (node (ref "Q13") (pin "3") (pinfunction "D_3") (pintype "passive"))
    )
    (net (code "174") (name "Net-(IC35A--IN)") (class "Default")
      (node (ref "IC35") (pin "1") (pinfunction "OUT_1") (pintype "output"))
      (node (ref "IC35") (pin "4") (pinfunction "-IN_4") (pintype "input"))
      (node (ref "JP3") (pin "NC") (pinfunction "NC_NC") (pintype "passive"))
    )
    (net (code "175") (name "Net-(IC36-REFCAP)") (class "Default")
      (node (ref "C92") (pin "2") (pinfunction "2_2") (pintype "passive"))
      (node (ref "C93") (pin "2") (pinfunction "2_2") (pintype "passive"))
      (node (ref "IC36") (pin "7") (pinfunction "REFCAP_7") (pintype "output"))
    )
    (net (code "176") (name "Net-(Q1A-D)") (class "Default")
      (node (ref "C82") (pin "2") (pinfunction "2_2") (pintype "passive"))
      (node (ref "Q1") (pin "6") (pinfunction "D_6") (pintype "passive"))
    )
    (net (code "177") (name "Net-(Q1B-D)") (class "Default")
      (node (ref "C81") (pin "2") (pinfunction "2_2") (pintype "passive"))
      (node (ref "Q1") (pin "3") (pinfunction "D_3") (pintype "passive"))
    )
    (net (code "178") (name "Net-(Q2A-D)") (class "Default")
      (node (ref "Q2") (pin "6") (pinfunction "D_6") (pintype "passive"))
      (node (ref "R52") (pin "2") (pinfunction "2_2") (pintype "passive"))
    )
    (net (code "179") (name "Net-(Q2B-D)") (class "Default")
      (node (ref "Q2") (pin "3") (pinfunction "D_3") (pintype "passive"))
      (node (ref "R53") (pin "2") (pinfunction "2_2") (pintype "passive"))
    )
    (net (code "180") (name "Net-(Q3A-D)") (class "Default")
      (node (ref "Q3") (pin "6") (pinfunction "D_6") (pintype "passive"))
      (node (ref "R54") (pin "2") (pinfunction "2_2") (pintype "passive"))
    )
    (net (code "181") (name "Net-(Q3B-D)") (class "Default")
      (node (ref "Q3") (pin "3") (pinfunction "D_3") (pintype "passive"))
      (node (ref "R55") (pin "2") (pinfunction "2_2") (pintype "passive"))
    )
    (net (code "182") (name "Net-(Q4A-D)") (class "Default")
      (node (ref "Q4") (pin "6") (pinfunction "D_6") (pintype "passive"))
      (node (ref "R56") (pin "2") (pinfunction "2_2") (pintype "passive"))
    )
    (net (code "183") (name "Net-(Q4B-D)") (class "Default")
      (node (ref "Q4") (pin "3") (pinfunction "D_3") (pintype "passive"))
      (node (ref "R57") (pin "2") (pinfunction "2_2") (pintype "passive"))
    )
    (net (code "184") (name "Net-(Q5A-D)") (class "Default")
      (node (ref "Q5") (pin "6") (pinfunction "D_6") (pintype "passive"))
      (node (ref "R58") (pin "2") (pinfunction "2_2") (pintype "passive"))
    )
    (net (code "185") (name "Net-(Q5B-D)") (class "Default")
      (node (ref "Q5") (pin "3") (pinfunction "D_3") (pintype "passive"))
      (node (ref "R59") (pin "2") (pinfunction "2_2") (pintype "passive"))
    )
    (net (code "186") (name "Net-(Q6-G)") (class "Default")
      (node (ref "Q6") (pin "1") (pinfunction "G_1") (pintype "passive"))
      (node (ref "Q7") (pin "2") (pinfunction "S_2") (pintype "passive"))
      (node (ref "R62") (pin "1") (pinfunction "1_1") (pintype "passive"))
    )
    (net (code "187") (name "Net-(Q6-S)") (class "Default")
      (node (ref "Q6") (pin "2") (pinfunction "S_2") (pintype "passive"))
      (node (ref "Q7") (pin "1") (pinfunction "G_1") (pintype "passive"))
      (node (ref "R62") (pin "2") (pinfunction "2_2") (pintype "passive"))
    )
    (net (code "188") (name "Net-(Q8-G)") (class "Default")
      (node (ref "Q8") (pin "1") (pinfunction "G_1") (pintype "passive"))
      (node (ref "Q9") (pin "2") (pinfunction "S_2") (pintype "passive"))
      (node (ref "R70") (pin "1") (pinfunction "1_1") (pintype "passive"))
    )
    (net (code "189") (name "Net-(Q8-S)") (class "Default")
      (node (ref "Q8") (pin "2") (pinfunction "S_2") (pintype "passive"))
      (node (ref "Q9") (pin "1") (pinfunction "G_1") (pintype "passive"))
      (node (ref "R70") (pin "2") (pinfunction "2_2") (pintype "passive"))
    )
    (net (code "190") (name "Net-(Q10-G)") (class "Default")
      (node (ref "Q10") (pin "1") (pinfunction "G_1") (pintype "passive"))
      (node (ref "Q11") (pin "2") (pinfunction "S_2") (pintype "passive"))
      (node (ref "R74") (pin "1") (pinfunction "1_1") (pintype "passive"))
    )
    (net (code "191") (name "Net-(Q10-S)") (class "Default")
      (node (ref "Q10") (pin "2") (pinfunction "S_2") (pintype "passive"))
      (node (ref "Q11") (pin "1") (pinfunction "G_1") (pintype "passive"))
      (node (ref "R74") (pin "2") (pinfunction "2_2") (pintype "passive"))
    )
    (net (code "192") (name "Net-(Q12-G)") (class "Default")
      (node (ref "Q12") (pin "1") (pinfunction "G_1") (pintype "passive"))
      (node (ref "Q13") (pin "2") (pinfunction "S_2") (pintype "passive"))
      (node (ref "R78") (pin "1") (pinfunction "1_1") (pintype "passive"))
    )
    (net (code "193") (name "Net-(Q12-S)") (class "Default")
      (node (ref "Q12") (pin "2") (pinfunction "S_2") (pintype "passive"))
      (node (ref "Q13") (pin "1") (pinfunction "G_1") (pintype "passive"))
      (node (ref "R78") (pin "2") (pinfunction "2_2") (pintype "passive"))
    )
    (net (code "194") (name "Net-(R80-Pad2)") (class "Default")
      (node (ref "R80") (pin "2") (pinfunction "2_2") (pintype "passive"))
      (node (ref "R81") (pin "1") (pinfunction "1_1") (pintype "passive"))
    )
    (net (code "195") (name "Net-(RN2A-2)") (class "Default")
      (node (ref "RN2") (pin "8") (pinfunction "2_8") (pintype "passive"))
      (node (ref "X1") (pin "14") (pinfunction "1_14") (pintype "passive"))
    )
    (net (code "196") (name "Net-(RN2B-2)") (class "Default")
      (node (ref "RN2") (pin "7") (pinfunction "2_7") (pintype "passive"))
      (node (ref "X1") (pin "9") (pinfunction "1_9") (pintype "passive"))
    )
    (net (code "197") (name "Net-(RN2C-2)") (class "Default")
      (node (ref "RN2") (pin "6") (pinfunction "2_6") (pintype "passive"))
      (node (ref "X1") (pin "13") (pinfunction "1_13") (pintype "passive"))
    )
    (net (code "198") (name "Net-(RN2D-2)") (class "Default")
      (node (ref "RN2") (pin "5") (pinfunction "2_5") (pintype "passive"))
      (node (ref "X1") (pin "15") (pinfunction "1_15") (pintype "passive"))
    )
    (net (code "199") (name "Net-(SH5-GND_B)") (class "Default")
      (node (ref "R68") (pin "1") (pinfunction "1_1") (pintype "passive"))
      (node (ref "R69") (pin "1") (pinfunction "1_1") (pintype "passive"))
      (node (ref "SH5") (pin "2") (pinfunction "GND_B_2") (pintype "bidirectional"))
      (node (ref "TVS5") (pin "C1") (pinfunction "1_C1") (pintype "passive"))
    )
    (net (code "200") (name "Net-(SH6-GND_B)") (class "Default")
      (node (ref "R72") (pin "1") (pinfunction "1_1") (pintype "passive"))
      (node (ref "R73") (pin "1") (pinfunction "1_1") (pintype "passive"))
      (node (ref "SH6") (pin "2") (pinfunction "GND_B_2") (pintype "bidirectional"))
      (node (ref "TVS6") (pin "C1") (pinfunction "1_C1") (pintype "passive"))
    )
    (net (code "201") (name "Net-(SH7-GND_B)") (class "Default")
      (node (ref "R76") (pin "1") (pinfunction "1_1") (pintype "passive"))
      (node (ref "R77") (pin "1") (pinfunction "1_1") (pintype "passive"))
      (node (ref "SH7") (pin "2") (pinfunction "GND_B_2") (pintype "bidirectional"))
      (node (ref "TVS7") (pin "C1") (pinfunction "1_C1") (pintype "passive"))
    )
    (net (code "202") (name "Net-(SH8-GND_B)") (class "Default")
      (node (ref "R82") (pin "1") (pinfunction "1_1") (pintype "passive"))
      (node (ref "R83") (pin "1") (pinfunction "1_1") (pintype "passive"))
      (node (ref "SH8") (pin "2") (pinfunction "GND_B_2") (pintype "bidirectional"))
      (node (ref "TVS8") (pin "C1") (pinfunction "1_C1") (pintype "passive"))
    )
    (net (code "203") (name "Net-(TR1-COMM)") (class "Default")
      (node (ref "C12") (pin "2") (pinfunction "2_2") (pintype "passive"))
      (node (ref "C20") (pin "2") (pinfunction "2_2") (pintype "passive"))
      (node (ref "C6") (pin "2") (pinfunction "2_2") (pintype "passive"))
      (node (ref "C9") (pin "1") (pinfunction "1_1") (pintype "passive"))
      (node (ref "L2") (pin "4") (pinfunction "4_4") (pintype "passive"))
      (node (ref "L3") (pin "1") (pinfunction "1_1") (pintype "passive"))
      (node (ref "TR1") (pin "5") (pinfunction "COMM_5") (pintype "passive"))
      (node (ref "TR2") (pin "6") (pinfunction "COMM_6") (pintype "passive"))
    )
    (net (code "204") (name "Net-(TR1-IN+)") (class "Default")
      (node (ref "C6") (pin "1") (pinfunction "1_1") (pintype "passive"))
      (node (ref "C8") (pin "2") (pinfunction "2_2") (pintype "passive"))
      (node (ref "L1") (pin "3") (pinfunction "3_3") (pintype "passive"))
      (node (ref "TR1") (pin "1") (pinfunction "IN+_1") (pintype "input"))
      (node (ref "TR2") (pin "1") (pinfunction "IN+_1") (pintype "input"))
    )
    (net (code "205") (name "Net-(TR1-IN-)") (class "Default")
      (node (ref "C12") (pin "1") (pinfunction "1_1") (pintype "passive"))
      (node (ref "C8") (pin "1") (pinfunction "1_1") (pintype "passive"))
      (node (ref "L1") (pin "2") (pinfunction "2_2") (pintype "passive"))
      (node (ref "TR1") (pin "2") (pinfunction "IN-_2") (pintype "input"))
      (node (ref "TR2") (pin "2") (pinfunction "IN-_2") (pintype "input"))
    )
    (net (code "206") (name "Net-(TR1-OUT+)") (class "Default")
      (node (ref "C9") (pin "2") (pinfunction "2_2") (pintype "passive"))
      (node (ref "L2") (pin "1") (pinfunction "1_1") (pintype "passive"))
      (node (ref "TR1") (pin "6") (pinfunction "OUT+_6") (pintype "passive"))
      (node (ref "TR2") (pin "7") (pinfunction "OUT+_7") (pintype "passive"))
    )
    (net (code "207") (name "Net-(TR1-OUT-)") (class "Default")
      (node (ref "C20") (pin "1") (pinfunction "1_1") (pintype "passive"))
      (node (ref "L3") (pin "4") (pinfunction "4_4") (pintype "passive"))
      (node (ref "TR1") (pin "4") (pinfunction "OUT-_4") (pintype "passive"))
      (node (ref "TR2") (pin "5") (pinfunction "OUT-_5") (pintype "passive"))
    )
    (net (code "208") (name "Net-(TVS3-2)") (class "Default")
      (node (ref "R19") (pin "2") (pinfunction "2_2") (pintype "passive"))
      (node (ref "R20") (pin "1") (pinfunction "1_1") (pintype "passive"))
      (node (ref "TVS3") (pin "C2") (pinfunction "2_C2") (pintype "passive"))
    )
    (net (code "209") (name "Net-(TVS4-2)") (class "Default")
      (node (ref "R26") (pin "2") (pinfunction "2_2") (pintype "passive"))
      (node (ref "R27") (pin "1") (pinfunction "1_1") (pintype "passive"))
      (node (ref "TVS4") (pin "C2") (pinfunction "2_C2") (pintype "passive"))
    )
    (net (code "210") (name "Net-(X3M-1)") (class "Default")
      (node (ref "R31") (pin "1") (pinfunction "1_1") (pintype "passive"))
      (node (ref "X3") (pin "6") (pinfunction "1_6") (pintype "passive"))
    )
    (net (code "211") (name "Net-(X3N-1)") (class "Default")
      (node (ref "R32") (pin "1") (pinfunction "1_1") (pintype "passive"))
      (node (ref "X3") (pin "7") (pinfunction "1_7") (pintype "passive"))
    )
    (net (code "212") (name "Net-(X4B-1)") (class "Default")
      (node (ref "R37") (pin "1") (pinfunction "1_1") (pintype "passive"))
      (node (ref "X4") (pin "10") (pinfunction "1_10") (pintype "passive"))
    )
    (net (code "213") (name "Net-(X4C-1)") (class "Default")
      (node (ref "R38") (pin "1") (pinfunction "1_1") (pintype "passive"))
      (node (ref "X4") (pin "11") (pinfunction "1_11") (pintype "passive"))
    )
    (net (code "214") (name "Net-(X4D-1)") (class "Default")
      (node (ref "R39") (pin "1") (pinfunction "1_1") (pintype "passive"))
      (node (ref "X4") (pin "12") (pinfunction "1_12") (pintype "passive"))
    )
    (net (code "215") (name "Net-(X4E-1)") (class "Default")
      (node (ref "R40") (pin "1") (pinfunction "1_1") (pintype "passive"))
      (node (ref "X4") (pin "13") (pinfunction "1_13") (pintype "passive"))
    )
    (net (code "216") (name "Net-(X4F-1)") (class "Default")
      (node (ref "R41") (pin "1") (pinfunction "1_1") (pintype "passive"))
      (node (ref "X4") (pin "14") (pinfunction "1_14") (pintype "passive"))
    )
    (net (code "217") (name "Net-(X4G-1)") (class "Default")
      (node (ref "R42") (pin "1") (pinfunction "1_1") (pintype "passive"))
      (node (ref "X4") (pin "15") (pinfunction "1_15") (pintype "passive"))
    )
    (net (code "218") (name "Net-(X4H-1)") (class "Default")
      (node (ref "R43") (pin "1") (pinfunction "1_1") (pintype "passive"))
      (node (ref "X4") (pin "16") (pinfunction "1_16") (pintype "passive"))
    )
    (net (code "219") (name "Net-(X4P-1)") (class "Default")
      (node (ref "R36") (pin "1") (pinfunction "1_1") (pintype "passive"))
      (node (ref "X4") (pin "9") (pinfunction "1_9") (pintype "passive"))
    )
    (net (code "220") (name "OE_SYNC") (class "Default")
      (node (ref "IC3") (pin "3") (pinfunction "A1_3") (pintype "input"))
      (node (ref "X1") (pin "6") (pinfunction "1_6") (pintype "passive"))
    )
    (net (code "221") (name "OUT_EN") (class "Default")
      (node (ref "IC15") (pin "4") (pinfunction "ENA_4") (pintype "input"))
      (node (ref "IC16") (pin "4") (pinfunction "ENA_4") (pintype "input"))
      (node (ref "IC17") (pin "4") (pinfunction "ENA_4") (pintype "input"))
      (node (ref "IC18") (pin "4") (pinfunction "ENA_4") (pintype "input"))
      (node (ref "IC19") (pin "1") (pinfunction "EN_1") (pintype "input"))
      (node (ref "IC19") (pin "10") (pinfunction "EN_10") (pintype "input"))
      (node (ref "IC19") (pin "13") (pinfunction "EN_13") (pintype "input"))
      (node (ref "IC19") (pin "4") (pinfunction "EN_4") (pintype "input"))
      (node (ref "IC8") (pin "70") (pinfunction "PB11_70") (pintype "bidirectional"))
    )
    (net (code "222") (name "PE") (class "Default")
      (node (ref "C98") (pin "1") (pinfunction "1_1") (pintype "passive"))
      (node (ref "J1") (pin "1") (pinfunction "P$1_1") (pintype "bidirectional"))
      (node (ref "J1") (pin "2") (pinfunction "P$1_2") (pintype "bidirectional"))
      (node (ref "R80") (pin "1") (pinfunction "1_1") (pintype "passive"))
    )
    (net (code "223") (name "POUT0") (class "Default")
      (node (ref "IC18") (pin "7") (pinfunction "OUT1_7") (pintype "output"))
      (node (ref "X3") (pin "9") (pinfunction "1_9") (pintype "passive"))
    )
    (net (code "224") (name "POUT1") (class "Default")
      (node (ref "IC18") (pin "5") (pinfunction "OUT2_5") (pintype "output"))
      (node (ref "X3") (pin "10") (pinfunction "1_10") (pintype "passive"))
    )
    (net (code "225") (name "POUT2") (class "Default")
      (node (ref "IC17") (pin "7") (pinfunction "OUT1_7") (pintype "output"))
      (node (ref "X3") (pin "11") (pinfunction "1_11") (pintype "passive"))
    )
    (net (code "226") (name "POUT3") (class "Default")
      (node (ref "IC17") (pin "5") (pinfunction "OUT2_5") (pintype "output"))
      (node (ref "X3") (pin "12") (pinfunction "1_12") (pintype "passive"))
    )
    (net (code "227") (name "POUT4") (class "Default")
      (node (ref "IC16") (pin "7") (pinfunction "OUT1_7") (pintype "output"))
      (node (ref "X3") (pin "13") (pinfunction "1_13") (pintype "passive"))
    )
    (net (code "228") (name "POUT5") (class "Default")
      (node (ref "IC16") (pin "5") (pinfunction "OUT2_5") (pintype "output"))
      (node (ref "X3") (pin "14") (pinfunction "1_14") (pintype "passive"))
    )
    (net (code "229") (name "POUT6") (class "Default")
      (node (ref "IC15") (pin "7") (pinfunction "OUT1_7") (pintype "output"))
      (node (ref "X3") (pin "15") (pinfunction "1_15") (pintype "passive"))
    )
    (net (code "230") (name "POUT7") (class "Default")
      (node (ref "IC15") (pin "5") (pinfunction "OUT2_5") (pintype "output"))
      (node (ref "X3") (pin "16") (pinfunction "1_16") (pintype "passive"))
    )
    (net (code "231") (name "PWM#1") (class "Default")
      (node (ref "IC19") (pin "2") (pinfunction "I_2") (pintype "input"))
      (node (ref "IC19") (pin "5") (pinfunction "I_5") (pintype "input"))
      (node (ref "IC8") (pin "81") (pinfunction "PD12_81") (pintype "bidirectional"))
    )
    (net (code "232") (name "PWM#2") (class "Default")
      (node (ref "IC19") (pin "12") (pinfunction "I_12") (pintype "input"))
      (node (ref "IC19") (pin "9") (pinfunction "I_9") (pintype "input"))
      (node (ref "IC8") (pin "82") (pinfunction "PD13_82") (pintype "bidirectional"))
    )
    (net (code "233") (name "SCLK") (class "Default")
      (node (ref "IC8") (pin "65") (pinfunction "PE12_65") (pintype "bidirectional"))
      (node (ref "RN1") (pin "7") (pinfunction "2_7") (pintype "passive"))
    )
    (net (code "234") (name "SDIO_CLK") (class "Default")
      (node (ref "IC8") (pin "113") (pinfunction "PC12_113") (pintype "bidirectional"))
      (node (ref "J2") (pin "5") (pinfunction "CLK_5") (pintype "passive"))
    )
    (net (code "235") (name "SDIO_CMD") (class "Default")
      (node (ref "IC8") (pin "116") (pinfunction "PD2_116") (pintype "bidirectional"))
      (node (ref "J2") (pin "3") (pinfunction "CMD_3") (pintype "passive"))
      (node (ref "R4") (pin "2") (pinfunction "2_2") (pintype "passive"))
    )
    (net (code "236") (name "SDIO_D0") (class "Default")
      (node (ref "IC8") (pin "98") (pinfunction "PC8_98") (pintype "bidirectional"))
      (node (ref "J2") (pin "7") (pinfunction "DAT0_7") (pintype "passive"))
      (node (ref "R2") (pin "2") (pinfunction "2_2") (pintype "passive"))
    )
    (net (code "237") (name "SDIO_D1") (class "Default")
      (node (ref "IC8") (pin "99") (pinfunction "PC9_99") (pintype "bidirectional"))
      (node (ref "J2") (pin "8") (pinfunction "DAT1_8") (pintype "passive"))
      (node (ref "R5") (pin "2") (pinfunction "2_2") (pintype "passive"))
    )
    (net (code "238") (name "SDIO_D2") (class "Default")
      (node (ref "IC8") (pin "111") (pinfunction "PC10_111") (pintype "bidirectional"))
      (node (ref "J2") (pin "1") (pinfunction "DAT2_1") (pintype "passive"))
      (node (ref "R3") (pin "2") (pinfunction "2_2") (pintype "passive"))
    )
    (net (code "239") (name "SDIO_D3") (class "Default")
      (node (ref "IC8") (pin "112") (pinfunction "PC11_112") (pintype "bidirectional"))
      (node (ref "J2") (pin "2") (pinfunction "CD/DAT3_2") (pintype "passive"))
      (node (ref "R1") (pin "2") (pinfunction "2_2") (pintype "passive"))
    )
    (net (code "240") (name "SD_DETECT") (class "Default")
      (node (ref "IC8") (pin "110") (pinfunction "PA15_110") (pintype "bidirectional"))
      (node (ref "J2") (pin "SW1") (pinfunction "SW1_SW1") (pintype "passive"))
    )
    (net (code "241") (name "SLOW_DIN#0") (class "Default")
      (node (ref "IC8") (pin "139") (pinfunction "PB8_139") (pintype "bidirectional"))
      (node (ref "Q1") (pin "5") (pinfunction "G_5") (pintype "passive"))
    )
    (net (code "242") (name "SLOW_DIN#1") (class "Default")
      (node (ref "IC8") (pin "140") (pinfunction "PB9_140") (pintype "bidirectional"))
      (node (ref "Q1") (pin "2") (pinfunction "G_2") (pintype "passive"))
    )
    (net (code "243") (name "SWCLK") (class "Default")
      (node (ref "IC8") (pin "109") (pinfunction "PA14_109") (pintype "bidirectional"))
      (node (ref "X2") (pin "2") (pinfunction "1_2") (pintype "passive"))
    )
    (net (code "244") (name "SWDIO") (class "Default")
      (node (ref "IC8") (pin "105") (pinfunction "PA13_105") (pintype "bidirectional"))
      (node (ref "X2") (pin "4") (pinfunction "1_4") (pintype "passive"))
    )
    (net (code "245") (name "SYNC") (class "Default")
      (node (ref "IC3") (pin "14") (pinfunction "B1_14") (pintype "output"))
      (node (ref "IC8") (pin "80") (pinfunction "PD11_80") (pintype "bidirectional"))
    )
    (net (code "246") (name "TEMP_SW#1") (class "Default")
      (node (ref "IC21") (pin "3") (pinfunction "IN_3") (pintype "input"))
      (node (ref "IC8") (pin "7") (pinfunction "PC13_7") (pintype "bidirectional"))
    )
    (net (code "247") (name "TEMP_SW#2") (class "Default")
      (node (ref "IC26") (pin "3") (pinfunction "IN_3") (pintype "input"))
      (node (ref "IC8") (pin "8") (pinfunction "PC14-OSC32_IN_8") (pintype "bidirectional"))
    )
    (net (code "248") (name "VOLT_SW0") (class "Default")
      (node (ref "IC31") (pin "3") (pinfunction "IN_3") (pintype "input"))
      (node (ref "IC8") (pin "10") (pinfunction "PF0_10") (pintype "bidirectional"))
    )
    (net (code "249") (name "VOLT_SW1") (class "Default")
      (node (ref "IC32") (pin "3") (pinfunction "IN_3") (pintype "input"))
      (node (ref "IC8") (pin "11") (pinfunction "PF1_11") (pintype "bidirectional"))
    )
    (net (code "250") (name "VOLT_SW2") (class "Default")
      (node (ref "IC33") (pin "3") (pinfunction "IN_3") (pintype "input"))
      (node (ref "IC8") (pin "12") (pinfunction "PF2_12") (pintype "bidirectional"))
    )
    (net (code "251") (name "VOLT_SW3") (class "Default")
      (node (ref "IC34") (pin "3") (pinfunction "IN_3") (pintype "input"))
      (node (ref "IC8") (pin "13") (pinfunction "PF3_13") (pintype "bidirectional"))
    )
    (net (code "252") (name "unconnected-(IC8A-PA2-Pad36)") (class "Default")
      (node (ref "IC8") (pin "36") (pinfunction "PA2_36") (pintype "bidirectional"))
    )
    (net (code "253") (name "unconnected-(IC8A-PA3-Pad37)") (class "Default")
      (node (ref "IC8") (pin "37") (pinfunction "PA3_37") (pintype "bidirectional"))
    )
    (net (code "254") (name "unconnected-(IC8A-PA10-Pad102)") (class "Default")
      (node (ref "IC8") (pin "102") (pinfunction "PA10_102") (pintype "bidirectional"))
    )
    (net (code "255") (name "unconnected-(IC8A-PA11-Pad103)") (class "Default")
      (node (ref "IC8") (pin "103") (pinfunction "PA11_103") (pintype "bidirectional"))
    )
    (net (code "256") (name "unconnected-(IC8A-PA12-Pad104)") (class "Default")
      (node (ref "IC8") (pin "104") (pinfunction "PA12_104") (pintype "bidirectional"))
    )
    (net (code "257") (name "unconnected-(IC8A-PC0-Pad26)") (class "Default")
      (node (ref "IC8") (pin "26") (pinfunction "PC0_26") (pintype "bidirectional"))
    )
    (net (code "258") (name "unconnected-(IC8A-PC2-Pad28)") (class "Default")
      (node (ref "IC8") (pin "28") (pinfunction "PC2_28") (pintype "bidirectional"))
    )
    (net (code "259") (name "unconnected-(IC8A-PC3-Pad29)") (class "Default")
      (node (ref "IC8") (pin "29") (pinfunction "PC3_29") (pintype "bidirectional"))
    )
    (net (code "260") (name "unconnected-(IC8A-PD0-Pad114)") (class "Default")
      (node (ref "IC8") (pin "114") (pinfunction "PD0_114") (pintype "bidirectional"))
    )
    (net (code "261") (name "unconnected-(IC8A-PD1-Pad115)") (class "Default")
      (node (ref "IC8") (pin "115") (pinfunction "PD1_115") (pintype "bidirectional"))
    )
    (net (code "262") (name "unconnected-(IC8A-PD9-Pad78)") (class "Default")
      (node (ref "IC8") (pin "78") (pinfunction "PD9_78") (pintype "bidirectional"))
    )
    (net (code "263") (name "unconnected-(IC8A-PD10-Pad79)") (class "Default")
      (node (ref "IC8") (pin "79") (pinfunction "PD10_79") (pintype "bidirectional"))
    )
    (net (code "264") (name "unconnected-(IC8A-PD14-Pad85)") (class "Default")
      (node (ref "IC8") (pin "85") (pinfunction "PD14_85") (pintype "bidirectional"))
    )
    (net (code "265") (name "unconnected-(IC8A-PD15-Pad86)") (class "Default")
      (node (ref "IC8") (pin "86") (pinfunction "PD15_86") (pintype "bidirectional"))
    )
    (net (code "266") (name "unconnected-(IC8B-PE0-Pad141)") (class "Default")
      (node (ref "IC8") (pin "141") (pinfunction "PE0_141") (pintype "bidirectional"))
    )
    (net (code "267") (name "unconnected-(IC8B-PE1-Pad142)") (class "Default")
      (node (ref "IC8") (pin "142") (pinfunction "PE1_142") (pintype "bidirectional"))
    )
    (net (code "268") (name "unconnected-(IC8B-PE2-Pad1)") (class "Default")
      (node (ref "IC8") (pin "1") (pinfunction "PE2_1") (pintype "bidirectional"))
    )
    (net (code "269") (name "unconnected-(IC8B-PE3-Pad2)") (class "Default")
      (node (ref "IC8") (pin "2") (pinfunction "PE3_2") (pintype "bidirectional"))
    )
    (net (code "270") (name "unconnected-(IC8B-PE4-Pad3)") (class "Default")
      (node (ref "IC8") (pin "3") (pinfunction "PE4_3") (pintype "bidirectional"))
    )
    (net (code "271") (name "unconnected-(IC8B-PE5-Pad4)") (class "Default")
      (node (ref "IC8") (pin "4") (pinfunction "PE5_4") (pintype "bidirectional"))
    )
    (net (code "272") (name "unconnected-(IC8B-PE6-Pad5)") (class "Default")
      (node (ref "IC8") (pin "5") (pinfunction "PE6_5") (pintype "bidirectional"))
    )
    (net (code "273") (name "unconnected-(IC8B-PE7-Pad58)") (class "Default")
      (node (ref "IC8") (pin "58") (pinfunction "PE7_58") (pintype "bidirectional"))
    )
    (net (code "274") (name "unconnected-(IC8B-PE8-Pad59)") (class "Default")
      (node (ref "IC8") (pin "59") (pinfunction "PE8_59") (pintype "bidirectional"))
    )
    (net (code "275") (name "unconnected-(IC8B-PE9-Pad60)") (class "Default")
      (node (ref "IC8") (pin "60") (pinfunction "PE9_60") (pintype "bidirectional"))
    )
    (net (code "276") (name "unconnected-(IC8B-PE10-Pad63)") (class "Default")
      (node (ref "IC8") (pin "63") (pinfunction "PE10_63") (pintype "bidirectional"))
    )
    (net (code "277") (name "unconnected-(IC8B-PE15-Pad68)") (class "Default")
      (node (ref "IC8") (pin "68") (pinfunction "PE15_68") (pintype "bidirectional"))
    )
    (net (code "278") (name "unconnected-(IC8B-PF4-Pad14)") (class "Default")
      (node (ref "IC8") (pin "14") (pinfunction "PF4_14") (pintype "bidirectional"))
    )
    (net (code "279") (name "unconnected-(IC8B-PF5-Pad15)") (class "Default")
      (node (ref "IC8") (pin "15") (pinfunction "PF5_15") (pintype "bidirectional"))
    )
    (net (code "280") (name "unconnected-(IC8B-PF11-Pad49)") (class "Default")
      (node (ref "IC8") (pin "49") (pinfunction "PF11_49") (pintype "bidirectional"))
    )
    (net (code "281") (name "unconnected-(IC8B-PF12-Pad50)") (class "Default")
      (node (ref "IC8") (pin "50") (pinfunction "PF12_50") (pintype "bidirectional"))
    )
    (net (code "282") (name "unconnected-(IC8B-PF13-Pad53)") (class "Default")
      (node (ref "IC8") (pin "53") (pinfunction "PF13_53") (pintype "bidirectional"))
    )
    (net (code "283") (name "unconnected-(IC8B-PF14-Pad54)") (class "Default")
      (node (ref "IC8") (pin "54") (pinfunction "PF14_54") (pintype "bidirectional"))
    )
    (net (code "284") (name "unconnected-(IC8B-PF15-Pad55)") (class "Default")
      (node (ref "IC8") (pin "55") (pinfunction "PF15_55") (pintype "bidirectional"))
    )
    (net (code "285") (name "unconnected-(IC8B-PG0-Pad56)") (class "Default")
      (node (ref "IC8") (pin "56") (pinfunction "PG0_56") (pintype "bidirectional"))
    )
    (net (code "286") (name "unconnected-(IC8B-PG1-Pad57)") (class "Default")
      (node (ref "IC8") (pin "57") (pinfunction "PG1_57") (pintype "bidirectional"))
    )
    (net (code "287") (name "unconnected-(IC8B-PG2-Pad87)") (class "Default")
      (node (ref "IC8") (pin "87") (pinfunction "PG2_87") (pintype "bidirectional"))
    )
    (net (code "288") (name "unconnected-(IC8B-PG4-Pad89)") (class "Default")
      (node (ref "IC8") (pin "89") (pinfunction "PG4_89") (pintype "bidirectional"))
    )
    (net (code "289") (name "unconnected-(IC8B-PG5-Pad90)") (class "Default")
      (node (ref "IC8") (pin "90") (pinfunction "PG5_90") (pintype "bidirectional"))
    )
    (net (code "290") (name "unconnected-(IC8B-PG8-Pad93)") (class "Default")
      (node (ref "IC8") (pin "93") (pinfunction "PG8_93") (pintype "bidirectional"))
    )
    (net (code "291") (name "unconnected-(IC8B-PG15-Pad132)") (class "Default")
      (node (ref "IC8") (pin "132") (pinfunction "PG15_132") (pintype "bidirectional"))
    )
    (net (code "292") (name "unconnected-(IC10-BOOST-Pad20)") (class "Default")
      (node (ref "IC10") (pin "20") (pinfunction "BOOST_20") (pintype "output"))
    )
    (net (code "293") (name "unconnected-(IC11-BOOST-Pad20)") (class "Default")
      (node (ref "IC11") (pin "20") (pinfunction "BOOST_20") (pintype "output"))
    )
    (net (code "294") (name "unconnected-(IC36-AUX_IN-Pad10)") (class "Default")
      (node (ref "IC36") (pin "10") (pinfunction "AUX_IN_10") (pintype "input"))
    )
    (net (code "295") (name "~{ADC_CS}") (class "Default")
      (node (ref "IC36") (pin "38") (pinfunction "~{CS}_38") (pintype "input"))
      (node (ref "RN5") (pin "1") (pinfunction "1_1") (pintype "passive"))
    )
    (net (code "296") (name "~{DAC_ALARM}") (class "Default")
      (node (ref "IC10") (pin "3") (pinfunction "~{ALARM}_3") (pintype "output"))
      (node (ref "IC11") (pin "3") (pinfunction "~{ALARM}_3") (pintype "output"))
      (node (ref "IC8") (pin "9") (pinfunction "PC15-OSC32_OUT_9") (pintype "bidirectional"))
      (node (ref "R12") (pin "2") (pinfunction "2_2") (pintype "passive"))
    )
    (net (code "297") (name "~{DAC_CS_DUAL}") (class "Default")
      (node (ref "IC13") (pin "6") (pinfunction "~{SYNC}_6") (pintype "input"))
      (node (ref "RN4") (pin "1") (pinfunction "1_1") (pintype "passive"))
    )
    (net (code "298") (name "~{OUT_FAULT}") (class "Default")
      (node (ref "IC15") (pin "1") (pinfunction "~{FAULT}_1") (pintype "output"))
      (node (ref "IC16") (pin "1") (pinfunction "~{FAULT}_1") (pintype "output"))
      (node (ref "IC17") (pin "1") (pinfunction "~{FAULT}_1") (pintype "output"))
      (node (ref "IC18") (pin "1") (pinfunction "~{FAULT}_1") (pintype "output"))
      (node (ref "IC8") (pin "88") (pinfunction "PG3_88") (pintype "bidirectional"))
      (node (ref "R30") (pin "2") (pinfunction "2_2") (pintype "passive"))
    )
    (net (code "299") (name "~{RESET}") (class "Default")
      (node (ref "C24") (pin "1") (pinfunction "1_1") (pintype "passive"))
      (node (ref "IC13") (pin "5") (pinfunction "~{CLR}_5") (pintype "input"))
      (node (ref "IC3") (pin "12") (pinfunction "B3_12") (pintype "output"))
      (node (ref "IC36") (pin "2") (pinfunction "~{RST/}PD_2") (pintype "input"))
      (node (ref "IC8") (pin "25") (pinfunction "NRST_25") (pintype "bidirectional"))
      (node (ref "R6") (pin "2") (pinfunction "2_2") (pintype "passive"))
    )
  )
)
